# SM2000-A.net
KiCad netlist of a schematic drawn in EAGLE
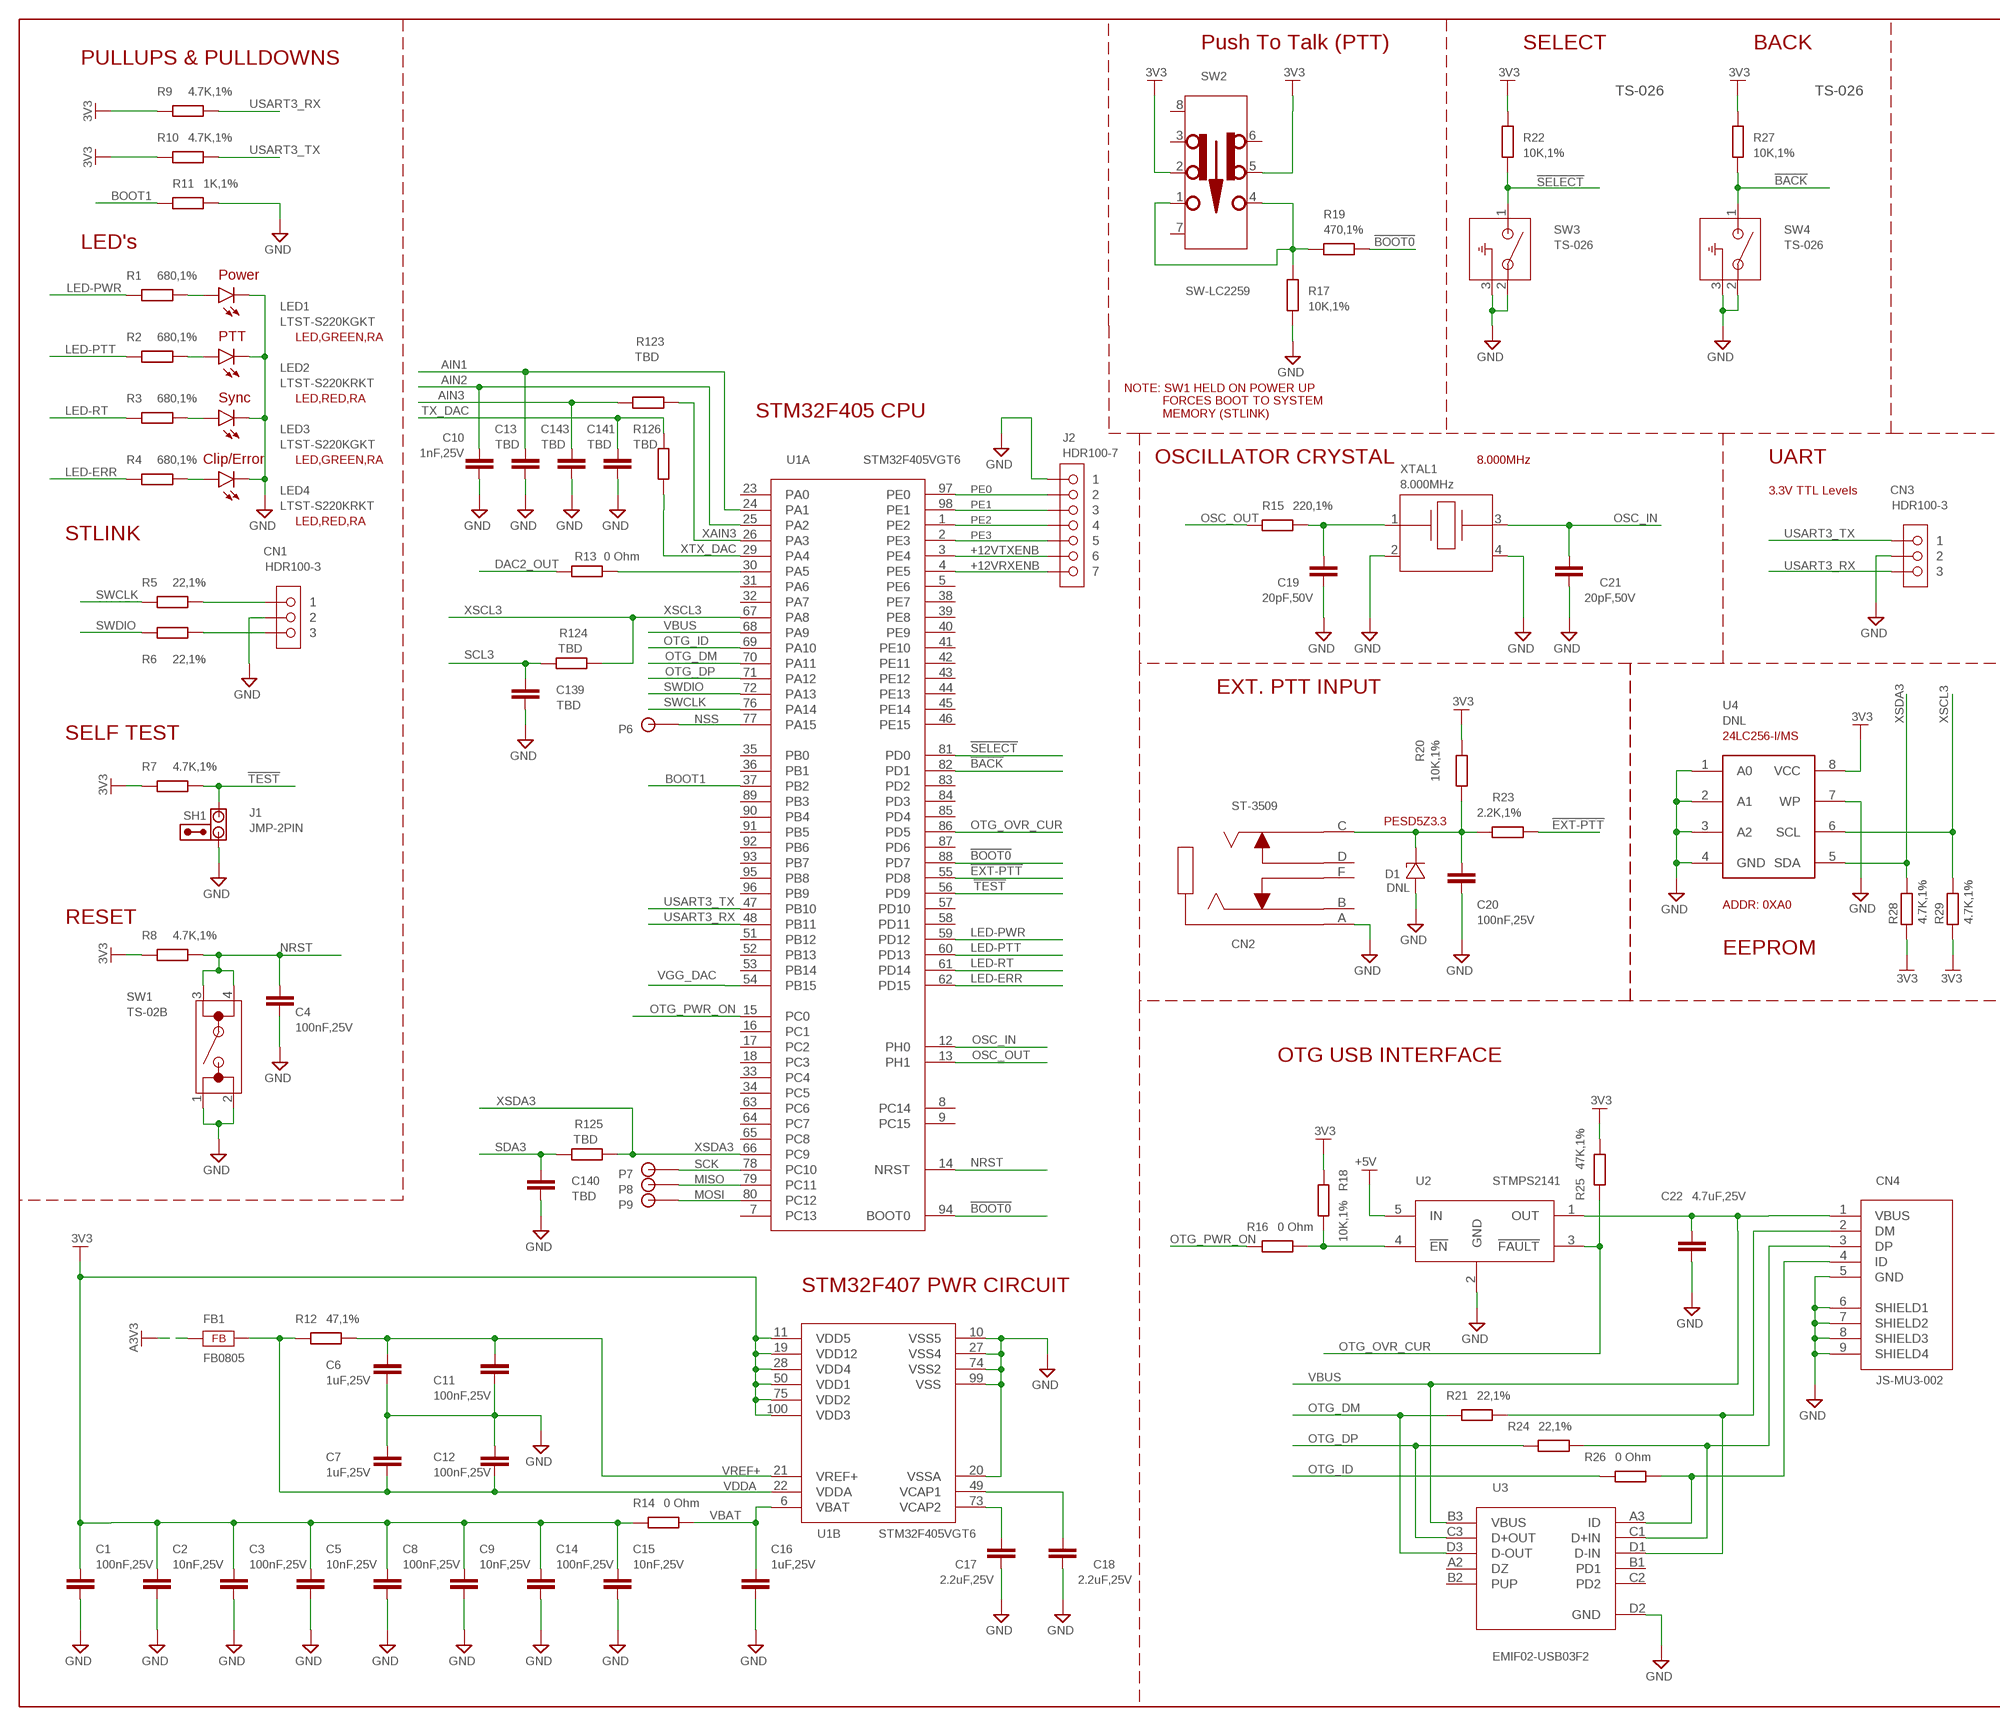
[diagram p0: schematic, sheet 1, part 1 of 2]
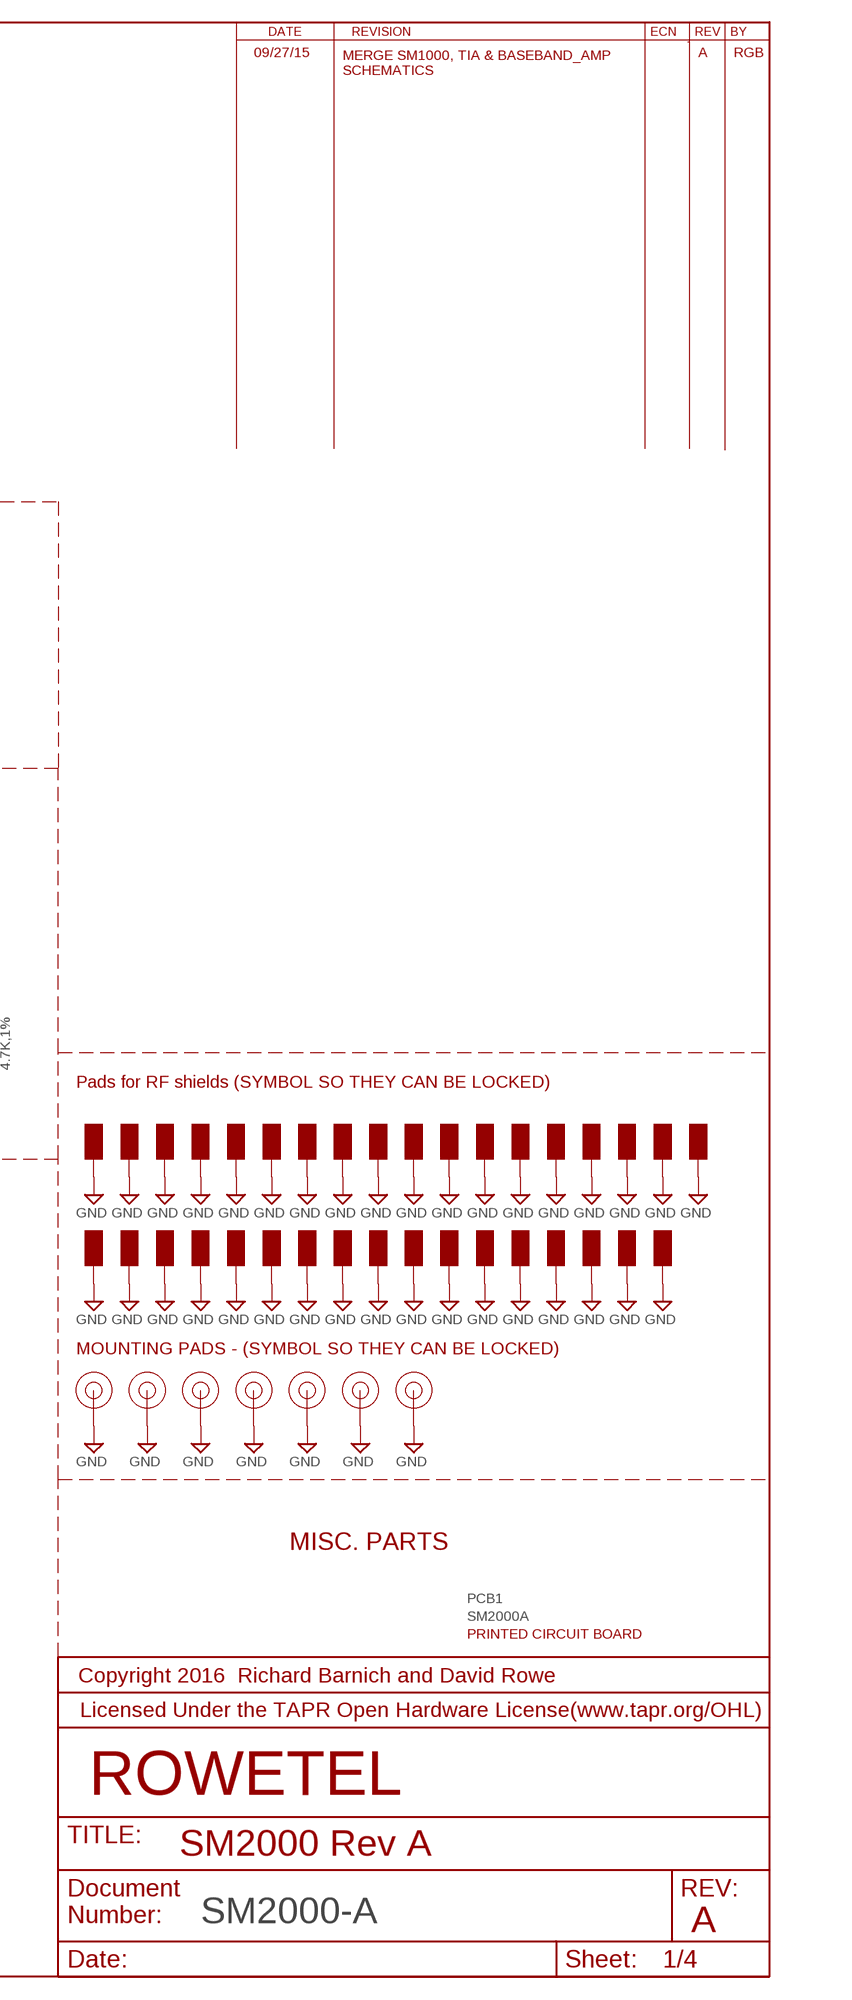
[diagram p1: schematic, sheet 1, part 2 of 2]
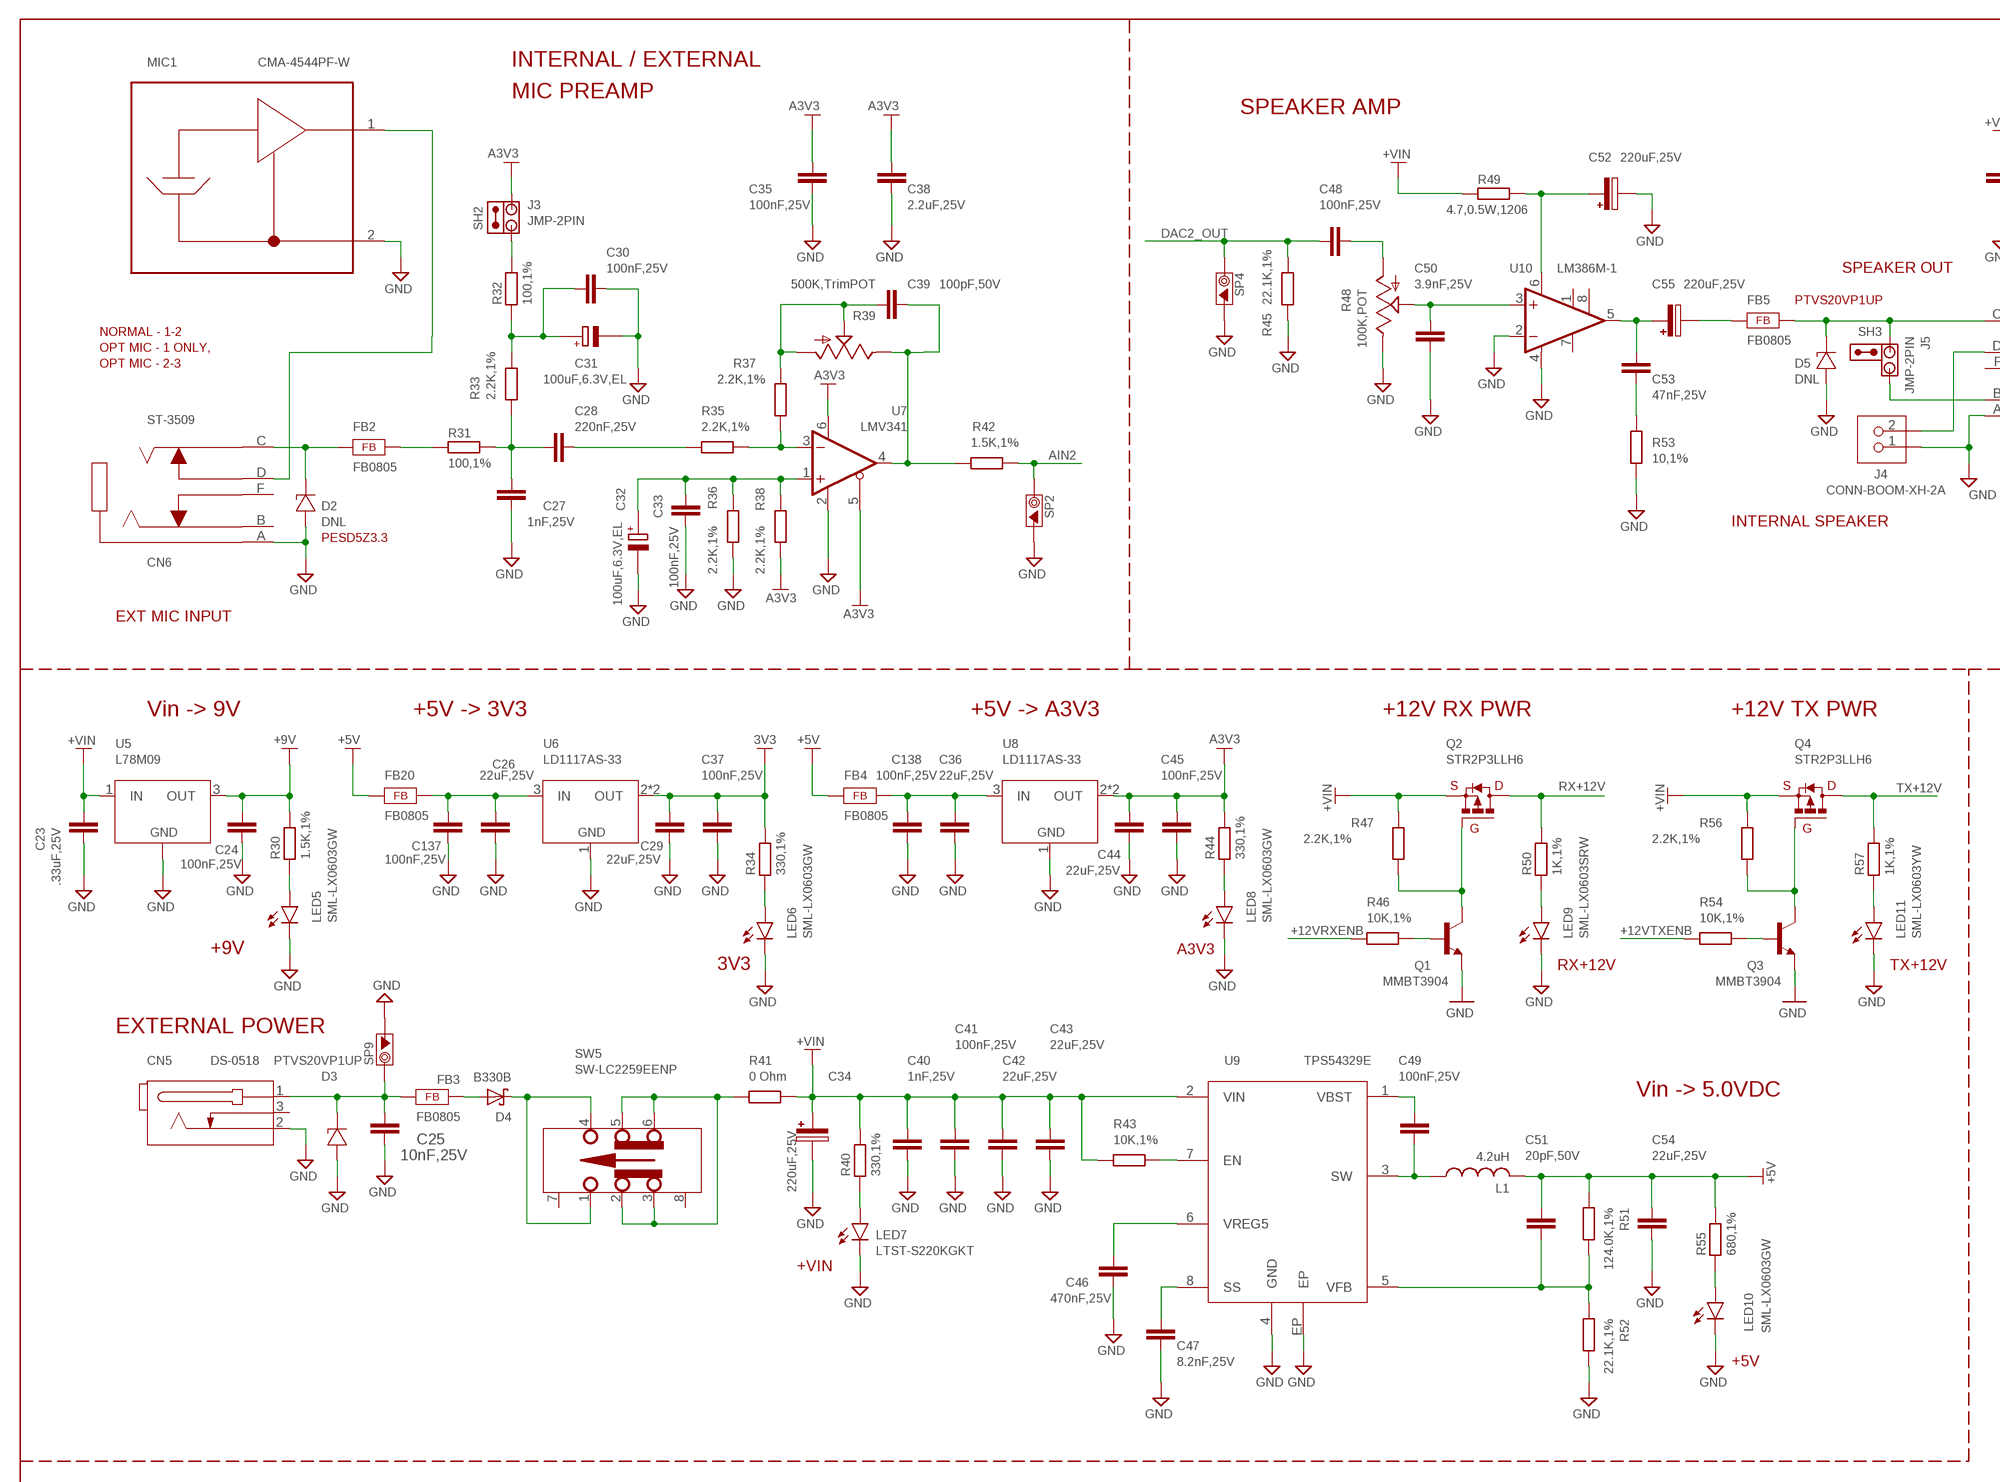
[diagram p2: schematic, sheet 2, part 1 of 2]
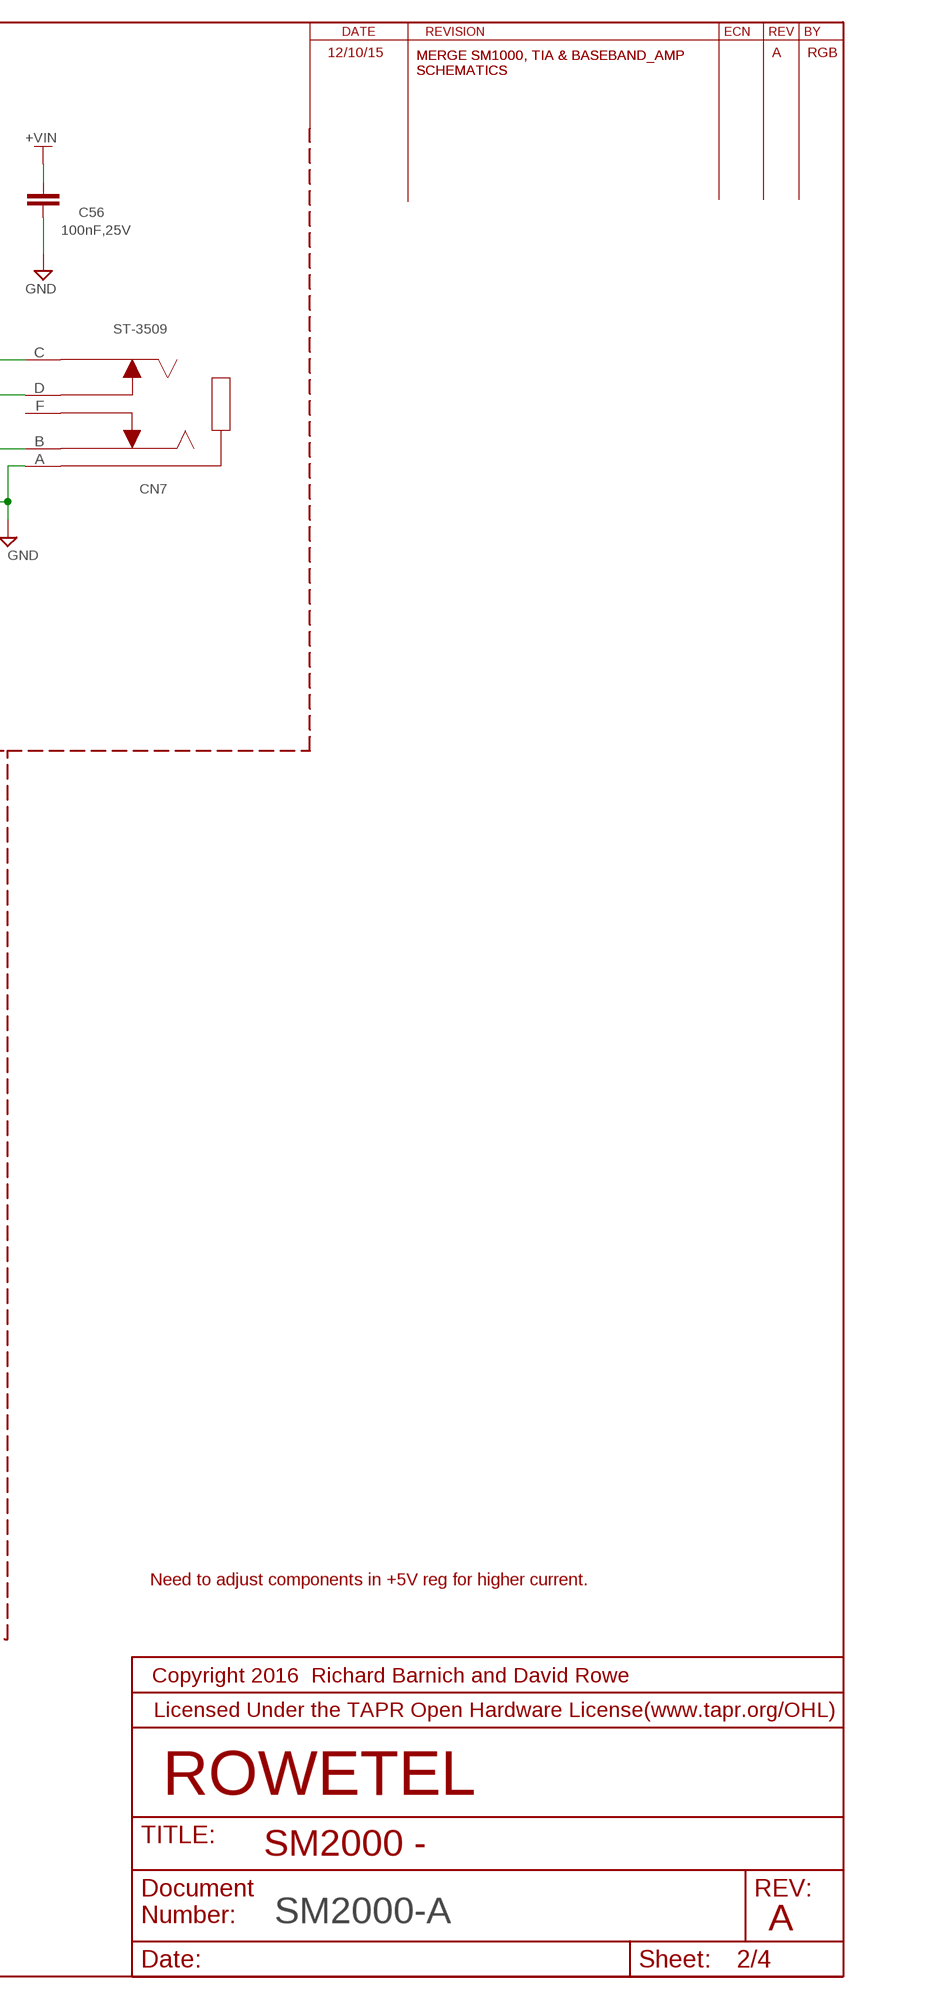
[diagram p3: schematic, sheet 2, part 2 of 2]
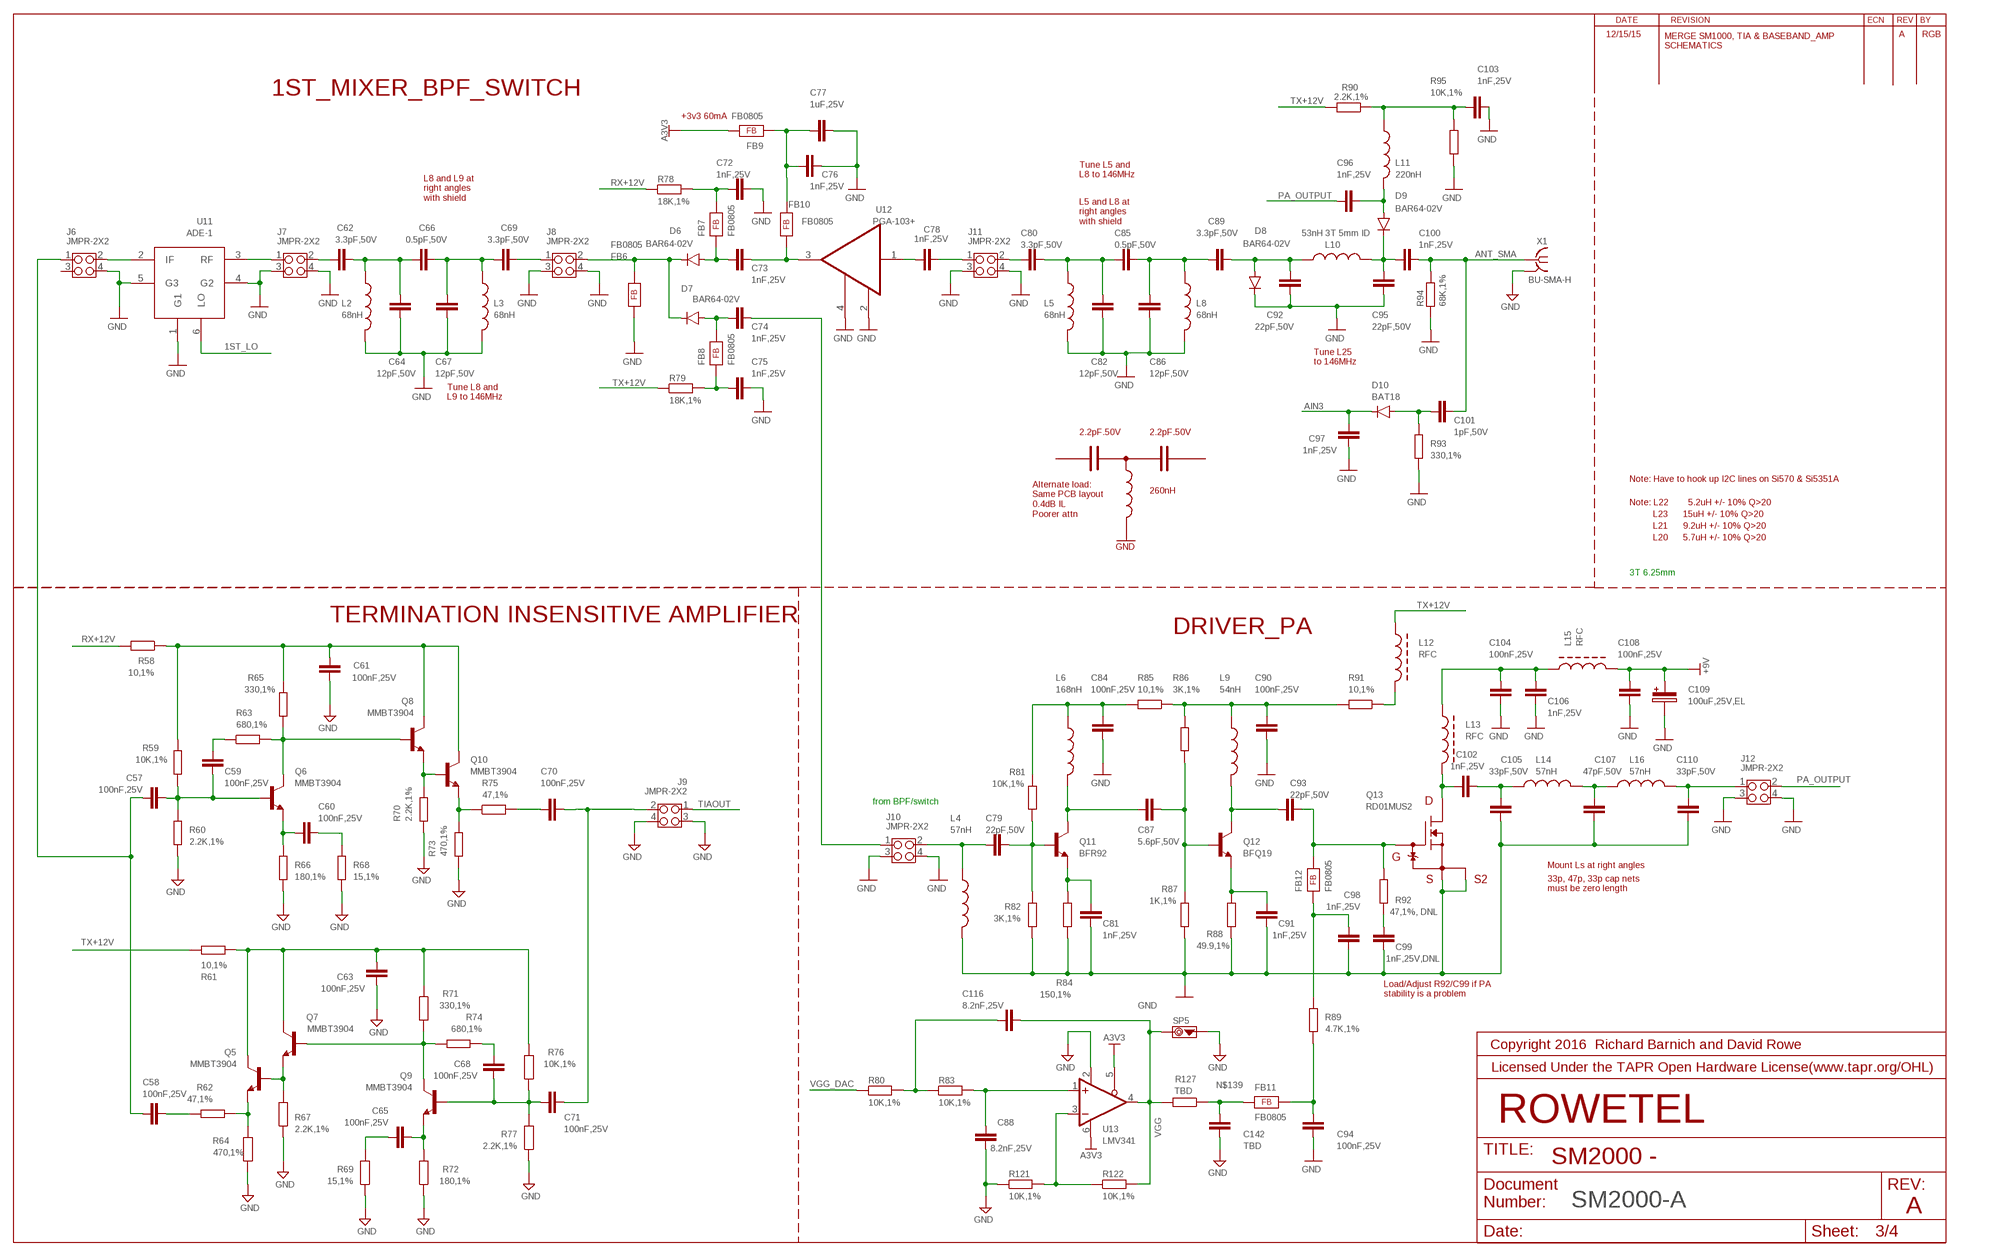
[diagram p4: schematic, sheet 3]
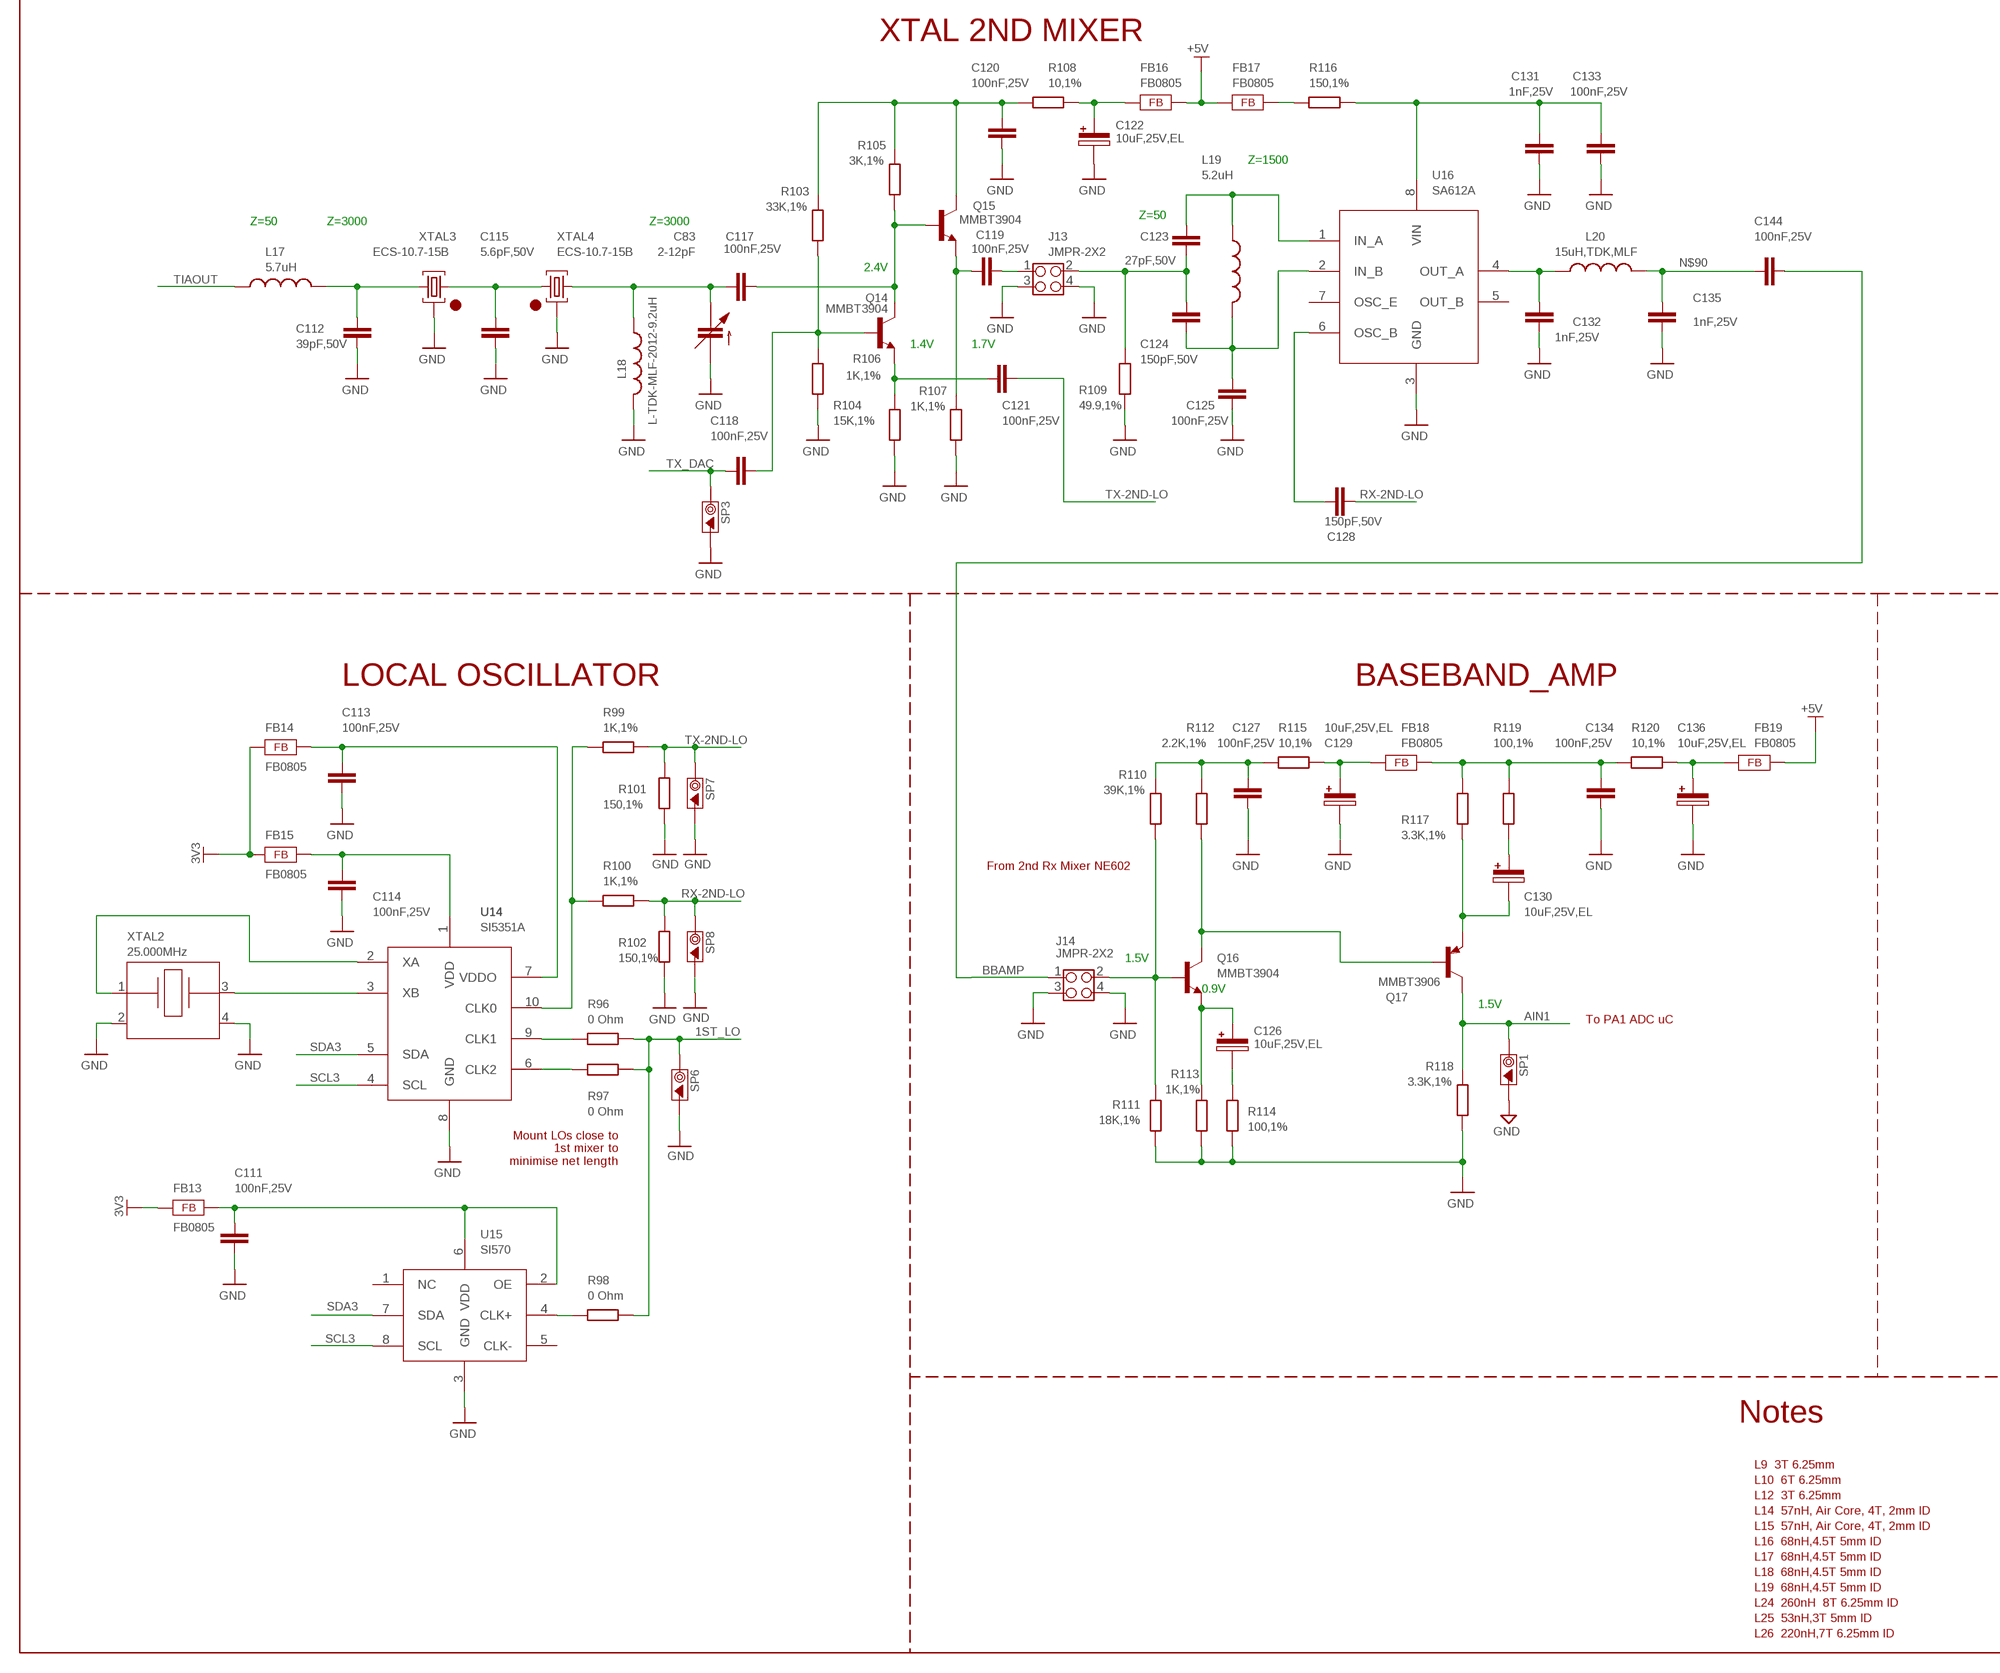
[diagram p5: schematic, sheet 4, part 1 of 2]
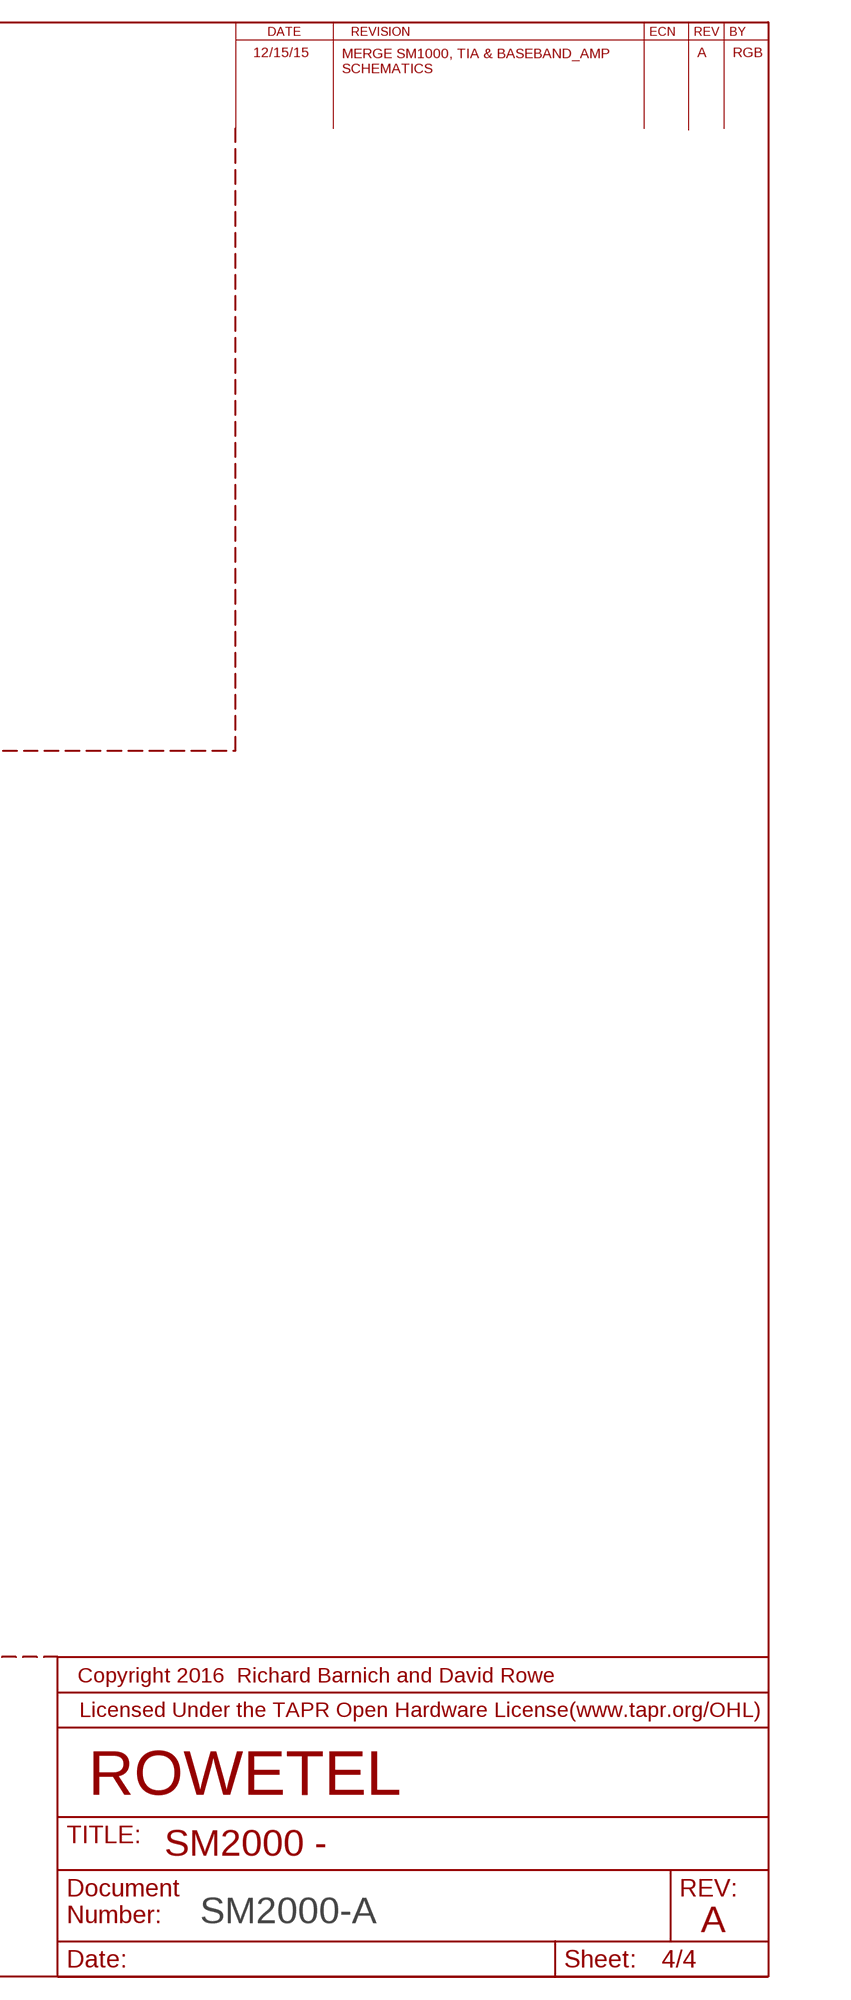
[diagram p6: schematic, sheet 4, part 2 of 2]

(export (version "E")
  (design (tool "Eeschema 10.0.6"))
  (components
    (comp (ref "C57")
      (value "100nF,25V")
      (footprint "eagle-import:C0805")
      (libsource (lib "eagle-import") (part "CAP-0805"))
    )
    (comp (ref "C58")
      (value "100nF,25V")
      (footprint "eagle-import:C0805")
      (libsource (lib "eagle-import") (part "CAP-0805"))
    )
    (comp (ref "C59")
      (value "100nF,25V")
      (footprint "eagle-import:C0805")
      (libsource (lib "eagle-import") (part "CAP-0805"))
    )
    (comp (ref "C60")
      (value "100nF,25V")
      (footprint "eagle-import:C0805")
      (libsource (lib "eagle-import") (part "CAP-0805"))
    )
    (comp (ref "C61")
      (value "100nF,25V")
      (footprint "eagle-import:C0805")
      (libsource (lib "eagle-import") (part "CAP-0805"))
    )
    (comp (ref "C62")
      (value "3.3pF,50V")
      (footprint "eagle-import:C0805")
      (libsource (lib "eagle-import") (part "CAP-0805"))
    )
    (comp (ref "C63")
      (value "100nF,25V")
      (footprint "eagle-import:C0805")
      (libsource (lib "eagle-import") (part "CAP-0805"))
    )
    (comp (ref "C64")
      (value "12pF,50V")
      (footprint "eagle-import:C0805")
      (libsource (lib "eagle-import") (part "CAP-0805"))
    )
    (comp (ref "C65")
      (value "100nF,25V")
      (footprint "eagle-import:C0805")
      (libsource (lib "eagle-import") (part "CAP-0805"))
    )
    (comp (ref "C66")
      (value "0.5pF,50V")
      (footprint "eagle-import:C0805")
      (libsource (lib "eagle-import") (part "CAP-0805"))
    )
    (comp (ref "C67")
      (value "12pF,50V")
      (footprint "eagle-import:C0805")
      (libsource (lib "eagle-import") (part "CAP-0805"))
    )
    (comp (ref "C68")
      (value "100nF,25V")
      (footprint "eagle-import:C0805")
      (libsource (lib "eagle-import") (part "CAP-0805"))
    )
    (comp (ref "C69")
      (value "3.3pF,50V")
      (footprint "eagle-import:C0805")
      (libsource (lib "eagle-import") (part "CAP-0805"))
    )
    (comp (ref "C70")
      (value "100nF,25V")
      (footprint "eagle-import:C0805")
      (libsource (lib "eagle-import") (part "CAP-0805"))
    )
    (comp (ref "C71")
      (value "100nF,25V")
      (footprint "eagle-import:C0805")
      (libsource (lib "eagle-import") (part "CAP-0805"))
    )
    (comp (ref "C72")
      (value "1nF,25V")
      (footprint "eagle-import:C0805")
      (libsource (lib "eagle-import") (part "CAP-0805"))
    )
    (comp (ref "C73")
      (value "1nF,25V")
      (footprint "eagle-import:C0805")
      (libsource (lib "eagle-import") (part "CAP-0805"))
    )
    (comp (ref "C74")
      (value "1nF,25V")
      (footprint "eagle-import:C0805")
      (libsource (lib "eagle-import") (part "CAP-0805"))
    )
    (comp (ref "C75")
      (value "1nF,25V")
      (footprint "eagle-import:C0805")
      (libsource (lib "eagle-import") (part "CAP-0805"))
    )
    (comp (ref "C76")
      (value "1nF,25V")
      (footprint "eagle-import:C0805")
      (libsource (lib "eagle-import") (part "CAP-0805"))
    )
    (comp (ref "C77")
      (value "1uF,25V")
      (footprint "eagle-import:C0805")
      (libsource (lib "eagle-import") (part "CAP-0805"))
    )
    (comp (ref "C78")
      (value "1nF,25V")
      (footprint "eagle-import:C0805")
      (libsource (lib "eagle-import") (part "CAP-0805"))
    )
    (comp (ref "C79")
      (value "22pF,50V")
      (footprint "eagle-import:C0805")
      (libsource (lib "eagle-import") (part "CAP-0805"))
    )
    (comp (ref "C80")
      (value "3.3pF,50V")
      (footprint "eagle-import:C0805")
      (libsource (lib "eagle-import") (part "CAP-0805"))
    )
    (comp (ref "C81")
      (value "1nF,25V")
      (footprint "eagle-import:C0805")
      (libsource (lib "eagle-import") (part "CAP-0805"))
    )
    (comp (ref "C82")
      (value "12pF,50V")
      (footprint "eagle-import:C0805")
      (libsource (lib "eagle-import") (part "CAP-0805"))
    )
    (comp (ref "C84")
      (value "100nF,25V")
      (footprint "eagle-import:C0805")
      (libsource (lib "eagle-import") (part "CAP-0805"))
    )
    (comp (ref "C85")
      (value "0.5pF,50V")
      (footprint "eagle-import:C0805")
      (libsource (lib "eagle-import") (part "CAP-0805"))
    )
    (comp (ref "C86")
      (value "12pF,50V")
      (footprint "eagle-import:C0805")
      (libsource (lib "eagle-import") (part "CAP-0805"))
    )
    (comp (ref "C87")
      (value "5.6pF,50V")
      (footprint "eagle-import:C0805")
      (libsource (lib "eagle-import") (part "CAP-0805"))
    )
    (comp (ref "C88")
      (value "8.2nF,25V")
      (footprint "eagle-import:C0805")
      (libsource (lib "eagle-import") (part "CAP-0805"))
    )
    (comp (ref "C89")
      (value "3.3pF,50V")
      (footprint "eagle-import:C0805")
      (libsource (lib "eagle-import") (part "CAP-0805"))
    )
    (comp (ref "C90")
      (value "100nF,25V")
      (footprint "eagle-import:C0805")
      (libsource (lib "eagle-import") (part "CAP-0805"))
    )
    (comp (ref "C91")
      (value "1nF,25V")
      (footprint "eagle-import:C0805")
      (libsource (lib "eagle-import") (part "CAP-0805"))
    )
    (comp (ref "C92")
      (value "22pF,50V")
      (footprint "eagle-import:C0805")
      (libsource (lib "eagle-import") (part "CAP-0805"))
    )
    (comp (ref "C93")
      (value "22pF,50V")
      (footprint "eagle-import:C0805")
      (libsource (lib "eagle-import") (part "CAP-0805"))
    )
    (comp (ref "C94")
      (value "100nF,25V")
      (footprint "eagle-import:C0805")
      (libsource (lib "eagle-import") (part "CAP-0805"))
    )
    (comp (ref "C95")
      (value "22pF,50V")
      (footprint "eagle-import:C0805")
      (libsource (lib "eagle-import") (part "CAP-0805"))
    )
    (comp (ref "C96")
      (value "1nF,25V")
      (footprint "eagle-import:C0805")
      (libsource (lib "eagle-import") (part "CAP-0805"))
    )
    (comp (ref "C97")
      (value "1nF,25V")
      (footprint "eagle-import:C0805")
      (libsource (lib "eagle-import") (part "CAP-0805"))
    )
    (comp (ref "C98")
      (value "1nF,25V")
      (footprint "eagle-import:C0805")
      (libsource (lib "eagle-import") (part "CAP-0805"))
    )
    (comp (ref "C99")
      (value "1nF,25V,DNL")
      (footprint "eagle-import:C0805")
      (libsource (lib "eagle-import") (part "CAP-0805"))
    )
    (comp (ref "C100")
      (value "1nF,25V")
      (footprint "eagle-import:C0805")
      (libsource (lib "eagle-import") (part "CAP-0805"))
    )
    (comp (ref "C101")
      (value "1pF,50V")
      (footprint "eagle-import:C0805")
      (libsource (lib "eagle-import") (part "CAP-0805"))
    )
    (comp (ref "C102")
      (value "1nF,25V")
      (footprint "eagle-import:C0805")
      (libsource (lib "eagle-import") (part "CAP-0805"))
    )
    (comp (ref "C103")
      (value "1nF,25V")
      (footprint "eagle-import:C0805")
      (libsource (lib "eagle-import") (part "CAP-0805"))
    )
    (comp (ref "C104")
      (value "100nF,25V")
      (footprint "eagle-import:C0805")
      (libsource (lib "eagle-import") (part "CAP-0805"))
    )
    (comp (ref "C105")
      (value "33pF,50V")
      (footprint "eagle-import:C0805")
      (libsource (lib "eagle-import") (part "CAP-0805"))
    )
    (comp (ref "C106")
      (value "1nF,25V")
      (footprint "eagle-import:C0805")
      (libsource (lib "eagle-import") (part "CAP-0805"))
    )
    (comp (ref "C107")
      (value "47pF,50V")
      (footprint "eagle-import:C0805")
      (libsource (lib "eagle-import") (part "CAP-0805"))
    )
    (comp (ref "C108")
      (value "100nF,25V")
      (footprint "eagle-import:C0805")
      (libsource (lib "eagle-import") (part "CAP-0805"))
    )
    (comp (ref "C109")
      (value "100uF,25V,EL")
      (footprint "eagle-import:CAP-CHEMI-F80")
      (libsource (lib "eagle-import") (part "CAP-CHEMI-F80"))
    )
    (comp (ref "C110")
      (value "33pF,50V")
      (footprint "eagle-import:C0805")
      (libsource (lib "eagle-import") (part "CAP-0805"))
    )
    (comp (ref "C116")
      (value "8.2nF,25V")
      (footprint "eagle-import:C0805")
      (libsource (lib "eagle-import") (part "CAP-0805"))
    )
    (comp (ref "C142")
      (value "TBD")
      (footprint "eagle-import:C0805")
      (libsource (lib "eagle-import") (part "CAP-0805"))
    )
    (comp (ref "D6")
      (value "BAR64-02V")
      (footprint "eagle-import:SC79_INFINEON")
      (libsource (lib "eagle-import") (part "BAR64-02V"))
    )
    (comp (ref "D7")
      (value "BAR64-02V")
      (footprint "eagle-import:SC79_INFINEON")
      (libsource (lib "eagle-import") (part "BAR64-02V"))
    )
    (comp (ref "D8")
      (value "BAR64-02V")
      (footprint "eagle-import:SC79_INFINEON")
      (libsource (lib "eagle-import") (part "BAR64-02V"))
    )
    (comp (ref "D9")
      (value "BAR64-02V")
      (footprint "eagle-import:SC79_INFINEON")
      (libsource (lib "eagle-import") (part "BAR64-02V"))
    )
    (comp (ref "D10")
      (value "BAT18")
      (footprint "eagle-import:SOT23")
      (libsource (lib "eagle-import") (part "BAT18"))
    )
    (comp (ref "FB6")
      (value "FB0805")
      (footprint "eagle-import:FE0805")
      (libsource (lib "eagle-import") (part "FB0805"))
    )
    (comp (ref "FB7")
      (value "FB0805")
      (footprint "eagle-import:FE0805")
      (libsource (lib "eagle-import") (part "FB0805"))
    )
    (comp (ref "FB8")
      (value "FB0805")
      (footprint "eagle-import:FE0805")
      (libsource (lib "eagle-import") (part "FB0805"))
    )
    (comp (ref "FB9")
      (value "FB0805")
      (footprint "eagle-import:FE0805")
      (libsource (lib "eagle-import") (part "FB0805"))
    )
    (comp (ref "FB10")
      (value "FB0805")
      (footprint "eagle-import:FE0805")
      (libsource (lib "eagle-import") (part "FB0805"))
    )
    (comp (ref "FB11")
      (value "FB0805")
      (footprint "eagle-import:FE0805")
      (libsource (lib "eagle-import") (part "FB0805"))
    )
    (comp (ref "FB12")
      (value "FB0805")
      (footprint "eagle-import:FE0805")
      (libsource (lib "eagle-import") (part "FB0805"))
    )
    (comp (ref "J6")
      (value "JMPR-2X2")
      (footprint "eagle-import:JMPR-2X2X.1")
      (libsource (lib "eagle-import") (part "JMPR-2X2"))
    )
    (comp (ref "J7")
      (value "JMPR-2X2")
      (footprint "eagle-import:JMPR-2X2X.1")
      (libsource (lib "eagle-import") (part "JMPR-2X2"))
    )
    (comp (ref "J8")
      (value "JMPR-2X2")
      (footprint "eagle-import:JMPR-2X2X.1")
      (libsource (lib "eagle-import") (part "JMPR-2X2"))
    )
    (comp (ref "J9")
      (value "JMPR-2X2")
      (footprint "eagle-import:JMPR-2X2X.1")
      (libsource (lib "eagle-import") (part "JMPR-2X2"))
    )
    (comp (ref "J10")
      (value "JMPR-2X2")
      (footprint "eagle-import:JMPR-2X2X.1")
      (libsource (lib "eagle-import") (part "JMPR-2X2"))
    )
    (comp (ref "J11")
      (value "JMPR-2X2")
      (footprint "eagle-import:JMPR-2X2X.1")
      (libsource (lib "eagle-import") (part "JMPR-2X2"))
    )
    (comp (ref "J12")
      (value "JMPR-2X2")
      (footprint "eagle-import:JMPR-2X2X.1")
      (libsource (lib "eagle-import") (part "JMPR-2X2"))
    )
    (comp (ref "L2")
      (value "68nH")
      (footprint "eagle-import:L10X15")
      (libsource (lib "eagle-import") (part "L-ROWE_15X10"))
    )
    (comp (ref "L3")
      (value "68nH")
      (footprint "eagle-import:L10X15")
      (libsource (lib "eagle-import") (part "L-ROWE_15X10"))
    )
    (comp (ref "L4")
      (value "57nH")
      (footprint "eagle-import:L10X15")
      (libsource (lib "eagle-import") (part "L-ROWE_15X10"))
    )
    (comp (ref "L5")
      (value "68nH")
      (footprint "eagle-import:L10X15")
      (libsource (lib "eagle-import") (part "L-ROWE_15X10"))
    )
    (comp (ref "L6")
      (value "168nH")
      (footprint "eagle-import:L10X15")
      (libsource (lib "eagle-import") (part "L-ROWE_15X10"))
    )
    (comp (ref "L8")
      (value "68nH")
      (footprint "eagle-import:L10X15")
      (libsource (lib "eagle-import") (part "L-ROWE_15X10"))
    )
    (comp (ref "L9")
      (value "54nH")
      (footprint "eagle-import:L10X15")
      (libsource (lib "eagle-import") (part "L-ROWE_15X10"))
    )
    (comp (ref "L10")
      (value "53nH 3T 5mm ID")
      (footprint "eagle-import:L10X15")
      (libsource (lib "eagle-import") (part "L-ROWE_15X10"))
    )
    (comp (ref "L11")
      (value "220nH")
      (footprint "eagle-import:L10X15")
      (libsource (lib "eagle-import") (part "L-ROWE_15X10"))
    )
    (comp (ref "L12")
      (value "RFC")
      (footprint "eagle-import:Z15_4")
      (libsource (lib "eagle-import") (part "RFC"))
    )
    (comp (ref "L13")
      (value "RFC")
      (footprint "eagle-import:Z15_4")
      (libsource (lib "eagle-import") (part "RFC"))
    )
    (comp (ref "L14")
      (value "57nH")
      (footprint "eagle-import:L10X15")
      (libsource (lib "eagle-import") (part "L-ROWE_15X10"))
    )
    (comp (ref "L15")
      (value "RFC")
      (footprint "eagle-import:Z15_4")
      (libsource (lib "eagle-import") (part "RFC"))
    )
    (comp (ref "L16")
      (value "57nH")
      (footprint "eagle-import:L10X15")
      (libsource (lib "eagle-import") (part "L-ROWE_15X10"))
    )
    (comp (ref "Q5")
      (value "MMBT3904")
      (footprint "eagle-import:SOT23")
      (libsource (lib "eagle-import") (part "MMBT3904"))
    )
    (comp (ref "Q6")
      (value "MMBT3904")
      (footprint "eagle-import:SOT23")
      (libsource (lib "eagle-import") (part "MMBT3904"))
    )
    (comp (ref "Q7")
      (value "MMBT3904")
      (footprint "eagle-import:SOT23")
      (libsource (lib "eagle-import") (part "MMBT3904"))
    )
    (comp (ref "Q8")
      (value "MMBT3904")
      (footprint "eagle-import:SOT23")
      (libsource (lib "eagle-import") (part "MMBT3904"))
    )
    (comp (ref "Q9")
      (value "MMBT3904")
      (footprint "eagle-import:SOT23")
      (libsource (lib "eagle-import") (part "MMBT3904"))
    )
    (comp (ref "Q10")
      (value "MMBT3904")
      (footprint "eagle-import:SOT23")
      (libsource (lib "eagle-import") (part "MMBT3904"))
    )
    (comp (ref "Q11")
      (value "BFR92")
      (footprint "eagle-import:SOT23")
      (libsource (lib "eagle-import") (part "BFR92"))
    )
    (comp (ref "Q12")
      (value "BFQ19")
      (footprint "eagle-import:SOT89")
      (libsource (lib "eagle-import") (part "BFQ19"))
    )
    (comp (ref "Q13")
      (value "RD01MUS2")
      (footprint "eagle-import:SOT89")
      (libsource (lib "eagle-import") (part "RD01MUS2"))
    )
    (comp (ref "R58")
      (value "10,1%")
      (footprint "eagle-import:R0805")
      (libsource (lib "eagle-import") (part "RES-0805"))
    )
    (comp (ref "R59")
      (value "10K,1%")
      (footprint "eagle-import:R0805")
      (libsource (lib "eagle-import") (part "RES-0805"))
    )
    (comp (ref "R60")
      (value "2.2K,1%")
      (footprint "eagle-import:R0805")
      (libsource (lib "eagle-import") (part "RES-0805"))
    )
    (comp (ref "R61")
      (value "10,1%")
      (footprint "eagle-import:R0805")
      (libsource (lib "eagle-import") (part "RES-0805"))
    )
    (comp (ref "R62")
      (value "47,1%")
      (footprint "eagle-import:R0805")
      (libsource (lib "eagle-import") (part "RES-0805"))
    )
    (comp (ref "R63")
      (value "680,1%")
      (footprint "eagle-import:R0805")
      (libsource (lib "eagle-import") (part "RES-0805"))
    )
    (comp (ref "R64")
      (value "470,1%")
      (footprint "eagle-import:R0805")
      (libsource (lib "eagle-import") (part "RES-0805"))
    )
    (comp (ref "R65")
      (value "330,1%")
      (footprint "eagle-import:R0805")
      (libsource (lib "eagle-import") (part "RES-0805"))
    )
    (comp (ref "R66")
      (value "180,1%")
      (footprint "eagle-import:R0805")
      (libsource (lib "eagle-import") (part "RES-0805"))
    )
    (comp (ref "R67")
      (value "2.2K,1%")
      (footprint "eagle-import:R0805")
      (libsource (lib "eagle-import") (part "RES-0805"))
    )
    (comp (ref "R68")
      (value "15,1%")
      (footprint "eagle-import:R0805")
      (libsource (lib "eagle-import") (part "RES-0805"))
    )
    (comp (ref "R69")
      (value "15,1%")
      (footprint "eagle-import:R0805")
      (libsource (lib "eagle-import") (part "RES-0805"))
    )
    (comp (ref "R70")
      (value "2.2K,1%")
      (footprint "eagle-import:R0805")
      (libsource (lib "eagle-import") (part "RES-0805"))
    )
    (comp (ref "R71")
      (value "330,1%")
      (footprint "eagle-import:R0805")
      (libsource (lib "eagle-import") (part "RES-0805"))
    )
    (comp (ref "R72")
      (value "180,1%")
      (footprint "eagle-import:R0805")
      (libsource (lib "eagle-import") (part "RES-0805"))
    )
    (comp (ref "R73")
      (value "470,1%")
      (footprint "eagle-import:R0805")
      (libsource (lib "eagle-import") (part "RES-0805"))
    )
    (comp (ref "R74")
      (value "680,1%")
      (footprint "eagle-import:R0805")
      (libsource (lib "eagle-import") (part "RES-0805"))
    )
    (comp (ref "R75")
      (value "47,1%")
      (footprint "eagle-import:R0805")
      (libsource (lib "eagle-import") (part "RES-0805"))
    )
    (comp (ref "R76")
      (value "10K,1%")
      (footprint "eagle-import:R0805")
      (libsource (lib "eagle-import") (part "RES-0805"))
    )
    (comp (ref "R77")
      (value "2.2K,1%")
      (footprint "eagle-import:R0805")
      (libsource (lib "eagle-import") (part "RES-0805"))
    )
    (comp (ref "R78")
      (value "18K,1%")
      (footprint "eagle-import:R0805")
      (libsource (lib "eagle-import") (part "RES-0805"))
    )
    (comp (ref "R79")
      (value "18K,1%")
      (footprint "eagle-import:R0805")
      (libsource (lib "eagle-import") (part "RES-0805"))
    )
    (comp (ref "R80")
      (value "10K,1%")
      (footprint "eagle-import:R0805")
      (libsource (lib "eagle-import") (part "RES-0805"))
    )
    (comp (ref "R81")
      (value "10K,1%")
      (footprint "eagle-import:R0805")
      (libsource (lib "eagle-import") (part "RES-0805"))
    )
    (comp (ref "R82")
      (value "3K,1%")
      (footprint "eagle-import:R0805")
      (libsource (lib "eagle-import") (part "RES-0805"))
    )
    (comp (ref "R83")
      (value "10K,1%")
      (footprint "eagle-import:R0805")
      (libsource (lib "eagle-import") (part "RES-0805"))
    )
    (comp (ref "R84")
      (value "150,1%")
      (footprint "eagle-import:R0805")
      (libsource (lib "eagle-import") (part "RES-0805"))
    )
    (comp (ref "R85")
      (value "10,1%")
      (footprint "eagle-import:R0805")
      (libsource (lib "eagle-import") (part "RES-0805"))
    )
    (comp (ref "R86")
      (value "3K,1%")
      (footprint "eagle-import:R0805")
      (libsource (lib "eagle-import") (part "RES-0805"))
    )
    (comp (ref "R87")
      (value "1K,1%")
      (footprint "eagle-import:R0805")
      (libsource (lib "eagle-import") (part "RES-0805"))
    )
    (comp (ref "R88")
      (value "49.9,1%")
      (footprint "eagle-import:R0805")
      (libsource (lib "eagle-import") (part "RES-0805"))
    )
    (comp (ref "R89")
      (value "4.7K,1%")
      (footprint "eagle-import:R0805")
      (libsource (lib "eagle-import") (part "RES-0805"))
    )
    (comp (ref "R90")
      (value "2.2K,1%")
      (footprint "eagle-import:R0805")
      (libsource (lib "eagle-import") (part "RES-0805"))
    )
    (comp (ref "R91")
      (value "10,1%")
      (footprint "eagle-import:R0805")
      (libsource (lib "eagle-import") (part "RES-0805"))
    )
    (comp (ref "R92")
      (value "47,1%, DNL")
      (footprint "eagle-import:R0805")
      (libsource (lib "eagle-import") (part "RES-0805"))
    )
    (comp (ref "R93")
      (value "330,1%")
      (footprint "eagle-import:R0805")
      (libsource (lib "eagle-import") (part "RES-0805"))
    )
    (comp (ref "R94")
      (value "68K,1%")
      (footprint "eagle-import:R0805")
      (libsource (lib "eagle-import") (part "RES-0805"))
    )
    (comp (ref "R95")
      (value "10K,1%")
      (footprint "eagle-import:R0805")
      (libsource (lib "eagle-import") (part "RES-0805"))
    )
    (comp (ref "R121")
      (value "10K,1%")
      (footprint "eagle-import:R0805")
      (libsource (lib "eagle-import") (part "RES-0805"))
    )
    (comp (ref "R122")
      (value "10K,1%")
      (footprint "eagle-import:R0805")
      (libsource (lib "eagle-import") (part "RES-0805"))
    )
    (comp (ref "R127")
      (value "TBD")
      (footprint "eagle-import:R0805")
      (libsource (lib "eagle-import") (part "RES-0805"))
    )
    (comp (ref "SP5")
      (value "SCOPE_PAD")
      (footprint "eagle-import:SCOPE_PAD")
      (libsource (lib "eagle-import") (part "SCOPE_PAD"))
    )
    (comp (ref "U11")
      (value "ADE-1")
      (footprint "eagle-import:ADE-1")
      (libsource (lib "eagle-import") (part "ADE-1"))
    )
    (comp (ref "U12")
      (value "PGA-103+")
      (footprint "eagle-import:DF782")
      (libsource (lib "eagle-import") (part "PGA-103+"))
    )
    (comp (ref "U13")
      (value "LMV341")
      (footprint "eagle-import:SOT23-6")
      (libsource (lib "eagle-import") (part "LMV341"))
    )
    (comp (ref "X1")
      (value "BU-SMA-H")
      (footprint "eagle-import:BU-SMA-H")
      (libsource (lib "eagle-import") (part "BU-SMA-H"))
    )
    (comp (ref "C1")
      (value "100nF,25V")
      (footprint "eagle-import:C0805")
      (libsource (lib "eagle-import") (part "CAP-0805"))
    )
    (comp (ref "C2")
      (value "10nF,25V")
      (footprint "eagle-import:C0805")
      (libsource (lib "eagle-import") (part "CAP-0805"))
    )
    (comp (ref "C3")
      (value "100nF,25V")
      (footprint "eagle-import:C0805")
      (libsource (lib "eagle-import") (part "CAP-0805"))
    )
    (comp (ref "C4")
      (value "100nF,25V")
      (footprint "eagle-import:C0805")
      (libsource (lib "eagle-import") (part "CAP-0805"))
    )
    (comp (ref "C5")
      (value "10nF,25V")
      (footprint "eagle-import:C0805")
      (libsource (lib "eagle-import") (part "CAP-0805"))
    )
    (comp (ref "C6")
      (value "1uF,25V")
      (footprint "eagle-import:C0805")
      (libsource (lib "eagle-import") (part "CAP-0805"))
    )
    (comp (ref "C7")
      (value "1uF,25V")
      (footprint "eagle-import:C0805")
      (libsource (lib "eagle-import") (part "CAP-0805"))
    )
    (comp (ref "C8")
      (value "100nF,25V")
      (footprint "eagle-import:C0805")
      (libsource (lib "eagle-import") (part "CAP-0805"))
    )
    (comp (ref "C9")
      (value "10nF,25V")
      (footprint "eagle-import:C0805")
      (libsource (lib "eagle-import") (part "CAP-0805"))
    )
    (comp (ref "C10")
      (value "1nF,25V")
      (footprint "eagle-import:C0805")
      (libsource (lib "eagle-import") (part "CAP-0805"))
    )
    (comp (ref "C11")
      (value "100nF,25V")
      (footprint "eagle-import:C0805")
      (libsource (lib "eagle-import") (part "CAP-0805"))
    )
    (comp (ref "C12")
      (value "100nF,25V")
      (footprint "eagle-import:C0805")
      (libsource (lib "eagle-import") (part "CAP-0805"))
    )
    (comp (ref "C13")
      (value "TBD")
      (footprint "eagle-import:C0805")
      (libsource (lib "eagle-import") (part "CAP-0805"))
    )
    (comp (ref "C14")
      (value "100nF,25V")
      (footprint "eagle-import:C0805")
      (libsource (lib "eagle-import") (part "CAP-0805"))
    )
    (comp (ref "C15")
      (value "10nF,25V")
      (footprint "eagle-import:C0805")
      (libsource (lib "eagle-import") (part "CAP-0805"))
    )
    (comp (ref "C16")
      (value "1uF,25V")
      (footprint "eagle-import:C0805")
      (libsource (lib "eagle-import") (part "CAP-0805"))
    )
    (comp (ref "C17")
      (value "2.2uF,25V")
      (footprint "eagle-import:C0805")
      (libsource (lib "eagle-import") (part "CAP-0805"))
    )
    (comp (ref "C18")
      (value "2.2uF,25V")
      (footprint "eagle-import:C0805")
      (libsource (lib "eagle-import") (part "CAP-0805"))
    )
    (comp (ref "C19")
      (value "20pF,50V")
      (footprint "eagle-import:C0805")
      (libsource (lib "eagle-import") (part "CAP-0805"))
    )
    (comp (ref "C20")
      (value "100nF,25V")
      (footprint "eagle-import:C0805")
      (libsource (lib "eagle-import") (part "CAP-0805"))
    )
    (comp (ref "C21")
      (value "20pF,50V")
      (footprint "eagle-import:C0805")
      (libsource (lib "eagle-import") (part "CAP-0805"))
    )
    (comp (ref "C22")
      (value "4.7uF,25V")
      (footprint "eagle-import:C0805")
      (libsource (lib "eagle-import") (part "CAP-0805"))
    )
    (comp (ref "C139")
      (value "TBD")
      (footprint "eagle-import:C0805")
      (libsource (lib "eagle-import") (part "CAP-0805"))
    )
    (comp (ref "C140")
      (value "TBD")
      (footprint "eagle-import:C0805")
      (libsource (lib "eagle-import") (part "CAP-0805"))
    )
    (comp (ref "C141")
      (value "TBD")
      (footprint "eagle-import:C0805")
      (libsource (lib "eagle-import") (part "CAP-0805"))
    )
    (comp (ref "C143")
      (value "TBD")
      (footprint "eagle-import:C0805")
      (libsource (lib "eagle-import") (part "CAP-0805"))
    )
    (comp (ref "CN1")
      (value "HDR100-3")
      (footprint "eagle-import:HDR100-3")
      (libsource (lib "eagle-import") (part "HDR100-3"))
    )
    (comp (ref "CN2")
      (value "ST-3509")
      (footprint "eagle-import:ST-3509")
      (libsource (lib "eagle-import") (part "ST-3509"))
    )
    (comp (ref "CN3")
      (value "HDR100-3")
      (footprint "eagle-import:HDR100-3")
      (libsource (lib "eagle-import") (part "HDR100-3"))
    )
    (comp (ref "CN4")
      (value "JS-MU3-002")
      (footprint "eagle-import:JI-MU3-002")
      (libsource (lib "eagle-import") (part "JS-MU3-002"))
    )
    (comp (ref "D1")
      (value "DNL")
      (footprint "eagle-import:SOD523")
      (libsource (lib "eagle-import") (part "PESD5ZX"))
    )
    (comp (ref "FB1")
      (value "FB0805")
      (footprint "eagle-import:FE0805")
      (libsource (lib "eagle-import") (part "FB0805"))
    )
    (comp (ref "J1")
      (value "JMP-2PIN")
      (footprint "eagle-import:JMPR-2PIN")
      (libsource (lib "eagle-import") (part "JMP-2PIN"))
    )
    (comp (ref "J2")
      (value "HDR100-7")
      (footprint "eagle-import:HDR100-7")
      (libsource (lib "eagle-import") (part "HDR100-7"))
    )
    (comp (ref "LED1")
      (value "LTST-S220KGKT")
      (footprint "eagle-import:LTST-S2200K")
      (libsource (lib "eagle-import") (part "LTST-S220K"))
    )
    (comp (ref "LED2")
      (value "LTST-S220KRKT")
      (footprint "eagle-import:LTST-S2200K")
      (libsource (lib "eagle-import") (part "LTST-S220K"))
    )
    (comp (ref "LED3")
      (value "LTST-S220KGKT")
      (footprint "eagle-import:LTST-S2200K")
      (libsource (lib "eagle-import") (part "LTST-S220K"))
    )
    (comp (ref "LED4")
      (value "LTST-S220KRKT")
      (footprint "eagle-import:LTST-S2200K")
      (libsource (lib "eagle-import") (part "LTST-S220K"))
    )
    (comp (ref "P6")
      (value "TPAD50")
      (footprint "eagle-import:TPAD50")
      (libsource (lib "eagle-import") (part "TPAD50"))
    )
    (comp (ref "P7")
      (value "TPAD50")
      (footprint "eagle-import:TPAD50")
      (libsource (lib "eagle-import") (part "TPAD50"))
    )
    (comp (ref "P8")
      (value "TPAD50")
      (footprint "eagle-import:TPAD50")
      (libsource (lib "eagle-import") (part "TPAD50"))
    )
    (comp (ref "P9")
      (value "TPAD50")
      (footprint "eagle-import:TPAD50")
      (libsource (lib "eagle-import") (part "TPAD50"))
    )
    (comp (ref "PAD1")
      (value "MTG-PAD-3.2")
      (footprint "eagle-import:MTG-PAD-3.2")
      (libsource (lib "eagle-import") (part "MTG-PAD-3.2"))
    )
    (comp (ref "PAD2")
      (value "MTG-PAD-3.2")
      (footprint "eagle-import:MTG-PAD-3.2")
      (libsource (lib "eagle-import") (part "MTG-PAD-3.2"))
    )
    (comp (ref "PAD3")
      (value "MTG-PAD-3.2")
      (footprint "eagle-import:MTG-PAD-3.2")
      (libsource (lib "eagle-import") (part "MTG-PAD-3.2"))
    )
    (comp (ref "PAD4")
      (value "MTG-PAD-3.2")
      (footprint "eagle-import:MTG-PAD-3.2")
      (libsource (lib "eagle-import") (part "MTG-PAD-3.2"))
    )
    (comp (ref "PAD5")
      (value "MTG-PAD-3.2")
      (footprint "eagle-import:MTG-PAD-3.2")
      (libsource (lib "eagle-import") (part "MTG-PAD-3.2"))
    )
    (comp (ref "PAD6")
      (value "MTG-PAD-3.2")
      (footprint "eagle-import:MTG-PAD-3.2")
      (libsource (lib "eagle-import") (part "MTG-PAD-3.2"))
    )
    (comp (ref "PAD7")
      (value "MTG-PAD-3.2")
      (footprint "eagle-import:MTG-PAD-3.2")
      (libsource (lib "eagle-import") (part "MTG-PAD-3.2"))
    )
    (comp (ref "PCB1")
      (value "SM2000A")
      (footprint "eagle-import:NOPACKAGE")
      (libsource (lib "eagle-import") (part "PCB"))
    )
    (comp (ref "R1")
      (value "680,1%")
      (footprint "eagle-import:R0805")
      (libsource (lib "eagle-import") (part "RES-0805"))
    )
    (comp (ref "R2")
      (value "680,1%")
      (footprint "eagle-import:R0805")
      (libsource (lib "eagle-import") (part "RES-0805"))
    )
    (comp (ref "R3")
      (value "680,1%")
      (footprint "eagle-import:R0805")
      (libsource (lib "eagle-import") (part "RES-0805"))
    )
    (comp (ref "R4")
      (value "680,1%")
      (footprint "eagle-import:R0805")
      (libsource (lib "eagle-import") (part "RES-0805"))
    )
    (comp (ref "R5")
      (value "22,1%")
      (footprint "eagle-import:R0805")
      (libsource (lib "eagle-import") (part "RES-0805"))
    )
    (comp (ref "R6")
      (value "22,1%")
      (footprint "eagle-import:R0805")
      (libsource (lib "eagle-import") (part "RES-0805"))
    )
    (comp (ref "R7")
      (value "4.7K,1%")
      (footprint "eagle-import:R0805")
      (libsource (lib "eagle-import") (part "RES-0805"))
    )
    (comp (ref "R8")
      (value "4.7K,1%")
      (footprint "eagle-import:R0805")
      (libsource (lib "eagle-import") (part "RES-0805"))
    )
    (comp (ref "R9")
      (value "4.7K,1%")
      (footprint "eagle-import:R0805")
      (libsource (lib "eagle-import") (part "RES-0805"))
    )
    (comp (ref "R10")
      (value "4.7K,1%")
      (footprint "eagle-import:R0805")
      (libsource (lib "eagle-import") (part "RES-0805"))
    )
    (comp (ref "R11")
      (value "1K,1%")
      (footprint "eagle-import:R0805")
      (libsource (lib "eagle-import") (part "RES-0805"))
    )
    (comp (ref "R12")
      (value "47,1%")
      (footprint "eagle-import:R0805")
      (libsource (lib "eagle-import") (part "RES-0805"))
    )
    (comp (ref "R13")
      (value "0 Ohm")
      (footprint "eagle-import:R0805")
      (libsource (lib "eagle-import") (part "RES-0805"))
    )
    (comp (ref "R14")
      (value "0 Ohm")
      (footprint "eagle-import:R0805")
      (libsource (lib "eagle-import") (part "RES-0805"))
    )
    (comp (ref "R15")
      (value "220,1%")
      (footprint "eagle-import:R0805")
      (libsource (lib "eagle-import") (part "RES-0805"))
    )
    (comp (ref "R16")
      (value "0 Ohm")
      (footprint "eagle-import:R0805")
      (libsource (lib "eagle-import") (part "RES-0805"))
    )
    (comp (ref "R17")
      (value "10K,1%")
      (footprint "eagle-import:R0805")
      (libsource (lib "eagle-import") (part "RES-0805"))
    )
    (comp (ref "R18")
      (value "10K,1%")
      (footprint "eagle-import:R0805")
      (libsource (lib "eagle-import") (part "RES-0805"))
    )
    (comp (ref "R19")
      (value "470,1%")
      (footprint "eagle-import:R0805")
      (libsource (lib "eagle-import") (part "RES-0805"))
    )
    (comp (ref "R20")
      (value "10K,1%")
      (footprint "eagle-import:R0805")
      (libsource (lib "eagle-import") (part "RES-0805"))
    )
    (comp (ref "R21")
      (value "22,1%")
      (footprint "eagle-import:R0805")
      (libsource (lib "eagle-import") (part "RES-0805"))
    )
    (comp (ref "R22")
      (value "10K,1%")
      (footprint "eagle-import:R0805")
      (libsource (lib "eagle-import") (part "RES-0805"))
    )
    (comp (ref "R23")
      (value "2.2K,1%")
      (footprint "eagle-import:R0805")
      (libsource (lib "eagle-import") (part "RES-0805"))
    )
    (comp (ref "R24")
      (value "22,1%")
      (footprint "eagle-import:R0805")
      (libsource (lib "eagle-import") (part "RES-0805"))
    )
    (comp (ref "R25")
      (value "47K,1%")
      (footprint "eagle-import:R0805")
      (libsource (lib "eagle-import") (part "RES-0805"))
    )
    (comp (ref "R26")
      (value "0 Ohm")
      (footprint "eagle-import:R0805")
      (libsource (lib "eagle-import") (part "RES-0805"))
    )
    (comp (ref "R27")
      (value "10K,1%")
      (footprint "eagle-import:R0805")
      (libsource (lib "eagle-import") (part "RES-0805"))
    )
    (comp (ref "R28")
      (value "4.7K,1%")
      (footprint "eagle-import:R0805")
      (libsource (lib "eagle-import") (part "RES-0805"))
    )
    (comp (ref "R29")
      (value "4.7K,1%")
      (footprint "eagle-import:R0805")
      (libsource (lib "eagle-import") (part "RES-0805"))
    )
    (comp (ref "R123")
      (value "TBD")
      (footprint "eagle-import:R0805")
      (libsource (lib "eagle-import") (part "RES-0805"))
    )
    (comp (ref "R124")
      (value "TBD")
      (footprint "eagle-import:R0805")
      (libsource (lib "eagle-import") (part "RES-0805"))
    )
    (comp (ref "R125")
      (value "TBD")
      (footprint "eagle-import:R0805")
      (libsource (lib "eagle-import") (part "RES-0805"))
    )
    (comp (ref "R126")
      (value "TBD")
      (footprint "eagle-import:R0805")
      (libsource (lib "eagle-import") (part "RES-0805"))
    )
    (comp (ref "S1")
      (value "SGND")
      (footprint "eagle-import:SGND")
      (libsource (lib "eagle-import") (part "SGND"))
    )
    (comp (ref "S2")
      (value "SGND")
      (footprint "eagle-import:SGND")
      (libsource (lib "eagle-import") (part "SGND"))
    )
    (comp (ref "S3")
      (value "SGND")
      (footprint "eagle-import:SGND")
      (libsource (lib "eagle-import") (part "SGND"))
    )
    (comp (ref "S4")
      (value "SGND")
      (footprint "eagle-import:SGND")
      (libsource (lib "eagle-import") (part "SGND"))
    )
    (comp (ref "S5")
      (value "SGND")
      (footprint "eagle-import:SGND")
      (libsource (lib "eagle-import") (part "SGND"))
    )
    (comp (ref "S6")
      (value "SGND")
      (footprint "eagle-import:SGND")
      (libsource (lib "eagle-import") (part "SGND"))
    )
    (comp (ref "S8")
      (value "SGND")
      (footprint "eagle-import:SGND")
      (libsource (lib "eagle-import") (part "SGND"))
    )
    (comp (ref "S9")
      (value "SGND")
      (footprint "eagle-import:SGND")
      (libsource (lib "eagle-import") (part "SGND"))
    )
    (comp (ref "S10")
      (value "SGND")
      (footprint "eagle-import:SGND")
      (libsource (lib "eagle-import") (part "SGND"))
    )
    (comp (ref "S11")
      (value "SGND")
      (footprint "eagle-import:SGND")
      (libsource (lib "eagle-import") (part "SGND"))
    )
    (comp (ref "S12")
      (value "SGND")
      (footprint "eagle-import:SGND")
      (libsource (lib "eagle-import") (part "SGND"))
    )
    (comp (ref "S14")
      (value "SGND")
      (footprint "eagle-import:SGND")
      (libsource (lib "eagle-import") (part "SGND"))
    )
    (comp (ref "S15")
      (value "SGND")
      (footprint "eagle-import:SGND")
      (libsource (lib "eagle-import") (part "SGND"))
    )
    (comp (ref "S16")
      (value "SGND")
      (footprint "eagle-import:SGND")
      (libsource (lib "eagle-import") (part "SGND"))
    )
    (comp (ref "S17")
      (value "SGND")
      (footprint "eagle-import:SGND")
      (libsource (lib "eagle-import") (part "SGND"))
    )
    (comp (ref "S18")
      (value "SGND")
      (footprint "eagle-import:SGND")
      (libsource (lib "eagle-import") (part "SGND"))
    )
    (comp (ref "S20")
      (value "SGND")
      (footprint "eagle-import:SGND")
      (libsource (lib "eagle-import") (part "SGND"))
    )
    (comp (ref "S21")
      (value "SGND")
      (footprint "eagle-import:SGND")
      (libsource (lib "eagle-import") (part "SGND"))
    )
    (comp (ref "S22")
      (value "SGND")
      (footprint "eagle-import:SGND")
      (libsource (lib "eagle-import") (part "SGND"))
    )
    (comp (ref "S23")
      (value "SGND")
      (footprint "eagle-import:SGND")
      (libsource (lib "eagle-import") (part "SGND"))
    )
    (comp (ref "S24")
      (value "SGND")
      (footprint "eagle-import:SGND")
      (libsource (lib "eagle-import") (part "SGND"))
    )
    (comp (ref "S25")
      (value "SGND")
      (footprint "eagle-import:SGND")
      (libsource (lib "eagle-import") (part "SGND"))
    )
    (comp (ref "S26")
      (value "SGND")
      (footprint "eagle-import:SGND")
      (libsource (lib "eagle-import") (part "SGND"))
    )
    (comp (ref "S27")
      (value "SGND")
      (footprint "eagle-import:SGND")
      (libsource (lib "eagle-import") (part "SGND"))
    )
    (comp (ref "S28")
      (value "SGND")
      (footprint "eagle-import:SGND")
      (libsource (lib "eagle-import") (part "SGND"))
    )
    (comp (ref "S29")
      (value "SGND")
      (footprint "eagle-import:SGND")
      (libsource (lib "eagle-import") (part "SGND"))
    )
    (comp (ref "S30")
      (value "SGND")
      (footprint "eagle-import:SGND")
      (libsource (lib "eagle-import") (part "SGND"))
    )
    (comp (ref "S31")
      (value "SGND")
      (footprint "eagle-import:SGND")
      (libsource (lib "eagle-import") (part "SGND"))
    )
    (comp (ref "S35")
      (value "SGND")
      (footprint "eagle-import:SGND")
      (libsource (lib "eagle-import") (part "SGND"))
    )
    (comp (ref "S36")
      (value "SGND")
      (footprint "eagle-import:SGND")
      (libsource (lib "eagle-import") (part "SGND"))
    )
    (comp (ref "S37")
      (value "SGND")
      (footprint "eagle-import:SGND")
      (libsource (lib "eagle-import") (part "SGND"))
    )
    (comp (ref "S38")
      (value "SGND")
      (footprint "eagle-import:SGND")
      (libsource (lib "eagle-import") (part "SGND"))
    )
    (comp (ref "S39")
      (value "SGND")
      (footprint "eagle-import:SGND")
      (libsource (lib "eagle-import") (part "SGND"))
    )
    (comp (ref "S40")
      (value "SGND")
      (footprint "eagle-import:SGND")
      (libsource (lib "eagle-import") (part "SGND"))
    )
    (comp (ref "S43")
      (value "SGND")
      (footprint "eagle-import:SGND")
      (libsource (lib "eagle-import") (part "SGND"))
    )
    (comp (ref "SH1")
      (value "SHUNT,0.1IN")
      (footprint "eagle-import:NOPACKAGE")
      (libsource (lib "eagle-import") (part "SHUNT,0.1IN"))
    )
    (comp (ref "SW1")
      (value "TS-02B")
      (footprint "eagle-import:TS-02B")
      (libsource (lib "eagle-import") (part "TS-02B"))
    )
    (comp (ref "SW2")
      (value "SW-LC2259")
      (footprint "eagle-import:SW-LC2259")
      (libsource (lib "eagle-import") (part "SW-LC2259"))
    )
    (comp (ref "SW3")
      (value "TS-026")
      (footprint "eagle-import:TS-026")
      (libsource (lib "eagle-import") (part "TS-026"))
    )
    (comp (ref "SW4")
      (value "TS-026")
      (footprint "eagle-import:TS-026")
      (libsource (lib "eagle-import") (part "TS-026"))
    )
    (comp (ref "U1")
      (value "STM32F405VGT6")
      (footprint "eagle-import:LQFP100-14")
      (libsource (lib "eagle-import") (part "STM32F407"))
    )
    (comp (ref "U2")
      (value "STMPS2141")
      (footprint "eagle-import:SOT23-5L")
      (libsource (lib "eagle-import") (part "STMPS2141"))
    )
    (comp (ref "U3")
      (value "EMIF02-USB03F2")
      (footprint "eagle-import:ECOPACK-11")
      (libsource (lib "eagle-import") (part "EMIF02-USB03F2"))
    )
    (comp (ref "U4")
      (value "DNL")
      (footprint "eagle-import:SOIC8")
      (libsource (lib "eagle-import") (part "I2C-EEPROM-256K"))
    )
    (comp (ref "XTAL1")
      (value "8.000MHz")
      (footprint "eagle-import:CTS-405")
      (libsource (lib "eagle-import") (part "CTS-405"))
    )
    (comp (ref "C83")
      (value "2-12pF")
      (footprint "eagle-import:TRIMCAP_VAR_2222_V")
      (libsource (lib "eagle-import") (part "TRIMCAP_VAR_2222_V"))
    )
    (comp (ref "C111")
      (value "100nF,25V")
      (footprint "eagle-import:C0805")
      (libsource (lib "eagle-import") (part "CAP-0805"))
    )
    (comp (ref "C112")
      (value "39pF,50V")
      (footprint "eagle-import:C0805")
      (libsource (lib "eagle-import") (part "CAP-0805"))
    )
    (comp (ref "C113")
      (value "100nF,25V")
      (footprint "eagle-import:C0805")
      (libsource (lib "eagle-import") (part "CAP-0805"))
    )
    (comp (ref "C114")
      (value "100nF,25V")
      (footprint "eagle-import:C0805")
      (libsource (lib "eagle-import") (part "CAP-0805"))
    )
    (comp (ref "C115")
      (value "5.6pF,50V")
      (footprint "eagle-import:C0805")
      (libsource (lib "eagle-import") (part "CAP-0805"))
    )
    (comp (ref "C117")
      (value "100nF,25V")
      (footprint "eagle-import:C0805")
      (libsource (lib "eagle-import") (part "CAP-0805"))
    )
    (comp (ref "C118")
      (value "100nF,25V")
      (footprint "eagle-import:C0805")
      (libsource (lib "eagle-import") (part "CAP-0805"))
    )
    (comp (ref "C119")
      (value "100nF,25V")
      (footprint "eagle-import:C0805")
      (libsource (lib "eagle-import") (part "CAP-0805"))
    )
    (comp (ref "C120")
      (value "100nF,25V")
      (footprint "eagle-import:C0805")
      (libsource (lib "eagle-import") (part "CAP-0805"))
    )
    (comp (ref "C121")
      (value "100nF,25V")
      (footprint "eagle-import:C0805")
      (libsource (lib "eagle-import") (part "CAP-0805"))
    )
    (comp (ref "C122")
      (value "10uF,25V,EL")
      (footprint "eagle-import:NICHICON-WJ-5")
      (libsource (lib "eagle-import") (part "CAP-10UF-WJ5"))
    )
    (comp (ref "C123")
      (value "27pF,50V")
      (footprint "eagle-import:C0805")
      (libsource (lib "eagle-import") (part "CAP-0805"))
    )
    (comp (ref "C124")
      (value "150pF,50V")
      (footprint "eagle-import:C0805")
      (libsource (lib "eagle-import") (part "CAP-0805"))
    )
    (comp (ref "C125")
      (value "100nF,25V")
      (footprint "eagle-import:C0805")
      (libsource (lib "eagle-import") (part "CAP-0805"))
    )
    (comp (ref "C126")
      (value "10uF,25V,EL")
      (footprint "eagle-import:NICHICON-WJ-5")
      (libsource (lib "eagle-import") (part "CAP-10UF-WJ5"))
    )
    (comp (ref "C127")
      (value "100nF,25V")
      (footprint "eagle-import:C0805")
      (libsource (lib "eagle-import") (part "CAP-0805"))
    )
    (comp (ref "C128")
      (value "150pF,50V")
      (footprint "eagle-import:C0805")
      (libsource (lib "eagle-import") (part "CAP-0805"))
    )
    (comp (ref "C129")
      (value "10uF,25V,EL")
      (footprint "eagle-import:NICHICON-WJ-5")
      (libsource (lib "eagle-import") (part "CAP-10UF-WJ5"))
    )
    (comp (ref "C130")
      (value "10uF,25V,EL")
      (footprint "eagle-import:NICHICON-WJ-5")
      (libsource (lib "eagle-import") (part "CAP-10UF-WJ5"))
    )
    (comp (ref "C131")
      (value "1nF,25V")
      (footprint "eagle-import:C0805")
      (libsource (lib "eagle-import") (part "CAP-0805"))
    )
    (comp (ref "C132")
      (value "1nF,25V")
      (footprint "eagle-import:C0805")
      (libsource (lib "eagle-import") (part "CAP-0805"))
    )
    (comp (ref "C133")
      (value "100nF,25V")
      (footprint "eagle-import:C0805")
      (libsource (lib "eagle-import") (part "CAP-0805"))
    )
    (comp (ref "C134")
      (value "100nF,25V")
      (footprint "eagle-import:C0805")
      (libsource (lib "eagle-import") (part "CAP-0805"))
    )
    (comp (ref "C135")
      (value "1nF,25V")
      (footprint "eagle-import:C0805")
      (libsource (lib "eagle-import") (part "CAP-0805"))
    )
    (comp (ref "C136")
      (value "10uF,25V,EL")
      (footprint "eagle-import:NICHICON-WJ-5")
      (libsource (lib "eagle-import") (part "CAP-10UF-WJ5"))
    )
    (comp (ref "C144")
      (value "100nF,25V")
      (footprint "eagle-import:C0805")
      (libsource (lib "eagle-import") (part "CAP-0805"))
    )
    (comp (ref "FB13")
      (value "FB0805")
      (footprint "eagle-import:FE0805")
      (libsource (lib "eagle-import") (part "FB0805"))
    )
    (comp (ref "FB14")
      (value "FB0805")
      (footprint "eagle-import:FE0805")
      (libsource (lib "eagle-import") (part "FB0805"))
    )
    (comp (ref "FB15")
      (value "FB0805")
      (footprint "eagle-import:FE0805")
      (libsource (lib "eagle-import") (part "FB0805"))
    )
    (comp (ref "FB16")
      (value "FB0805")
      (footprint "eagle-import:FE0805")
      (libsource (lib "eagle-import") (part "FB0805"))
    )
    (comp (ref "FB17")
      (value "FB0805")
      (footprint "eagle-import:FE0805")
      (libsource (lib "eagle-import") (part "FB0805"))
    )
    (comp (ref "FB18")
      (value "FB0805")
      (footprint "eagle-import:FE0805")
      (libsource (lib "eagle-import") (part "FB0805"))
    )
    (comp (ref "FB19")
      (value "FB0805")
      (footprint "eagle-import:FE0805")
      (libsource (lib "eagle-import") (part "FB0805"))
    )
    (comp (ref "J13")
      (value "JMPR-2X2")
      (footprint "eagle-import:JMPR-2X2X.1")
      (libsource (lib "eagle-import") (part "JMPR-2X2"))
    )
    (comp (ref "J14")
      (value "JMPR-2X2")
      (footprint "eagle-import:JMPR-2X2X.1")
      (libsource (lib "eagle-import") (part "JMPR-2X2"))
    )
    (comp (ref "L17")
      (value "5.7uH")
      (footprint "eagle-import:L-TDK-MLF2012")
      (libsource (lib "eagle-import") (part "L-TDK-MLF-2012"))
    )
    (comp (ref "L18")
      (value "L-TDK-MLF-2012-9.2uH")
      (footprint "eagle-import:L-TDK-MLF2012")
      (libsource (lib "eagle-import") (part "L-TDK-MLF-2012"))
    )
    (comp (ref "L19")
      (value "5.2uH")
      (footprint "eagle-import:L-TDK-MLF2012")
      (libsource (lib "eagle-import") (part "L-TDK-MLF-2012"))
    )
    (comp (ref "L20")
      (value "15uH,TDK,MLF")
      (footprint "eagle-import:L-TDK-MLF2012")
      (libsource (lib "eagle-import") (part "L-TDK-MLF-2012"))
    )
    (comp (ref "Q14")
      (value "MMBT3904")
      (footprint "eagle-import:SOT23")
      (libsource (lib "eagle-import") (part "MMBT3904"))
    )
    (comp (ref "Q15")
      (value "MMBT3904")
      (footprint "eagle-import:SOT23")
      (libsource (lib "eagle-import") (part "MMBT3904"))
    )
    (comp (ref "Q16")
      (value "MMBT3904")
      (footprint "eagle-import:SOT23")
      (libsource (lib "eagle-import") (part "MMBT3904"))
    )
    (comp (ref "Q17")
      (value "MMBT3906")
      (footprint "eagle-import:SOT23")
      (libsource (lib "eagle-import") (part "MMBT3906"))
    )
    (comp (ref "R96")
      (value "0 Ohm")
      (footprint "eagle-import:R0805")
      (libsource (lib "eagle-import") (part "RES-0805"))
    )
    (comp (ref "R97")
      (value "0 Ohm")
      (footprint "eagle-import:R0805")
      (libsource (lib "eagle-import") (part "RES-0805"))
    )
    (comp (ref "R98")
      (value "0 Ohm")
      (footprint "eagle-import:R0805")
      (libsource (lib "eagle-import") (part "RES-0805"))
    )
    (comp (ref "R99")
      (value "1K,1%")
      (footprint "eagle-import:R0805")
      (libsource (lib "eagle-import") (part "RES-0805"))
    )
    (comp (ref "R100")
      (value "1K,1%")
      (footprint "eagle-import:R0805")
      (libsource (lib "eagle-import") (part "RES-0805"))
    )
    (comp (ref "R101")
      (value "150,1%")
      (footprint "eagle-import:R0805")
      (libsource (lib "eagle-import") (part "RES-0805"))
    )
    (comp (ref "R102")
      (value "150,1%")
      (footprint "eagle-import:R0805")
      (libsource (lib "eagle-import") (part "RES-0805"))
    )
    (comp (ref "R103")
      (value "33K,1%")
      (footprint "eagle-import:R0805")
      (libsource (lib "eagle-import") (part "RES-0805"))
    )
    (comp (ref "R104")
      (value "15K,1%")
      (footprint "eagle-import:R0805")
      (libsource (lib "eagle-import") (part "RES-0805"))
    )
    (comp (ref "R105")
      (value "3K,1%")
      (footprint "eagle-import:R0805")
      (libsource (lib "eagle-import") (part "RES-0805"))
    )
    (comp (ref "R106")
      (value "1K,1%")
      (footprint "eagle-import:R0805")
      (libsource (lib "eagle-import") (part "RES-0805"))
    )
    (comp (ref "R107")
      (value "1K,1%")
      (footprint "eagle-import:R0805")
      (libsource (lib "eagle-import") (part "RES-0805"))
    )
    (comp (ref "R108")
      (value "10,1%")
      (footprint "eagle-import:R0805")
      (libsource (lib "eagle-import") (part "RES-0805"))
    )
    (comp (ref "R109")
      (value "49.9,1%")
      (footprint "eagle-import:R0805")
      (libsource (lib "eagle-import") (part "RES-0805"))
    )
    (comp (ref "R110")
      (value "39K,1%")
      (footprint "eagle-import:R0805")
      (libsource (lib "eagle-import") (part "RES-0805"))
    )
    (comp (ref "R111")
      (value "18K,1%")
      (footprint "eagle-import:R0805")
      (libsource (lib "eagle-import") (part "RES-0805"))
    )
    (comp (ref "R112")
      (value "2.2K,1%")
      (footprint "eagle-import:R0805")
      (libsource (lib "eagle-import") (part "RES-0805"))
    )
    (comp (ref "R113")
      (value "1K,1%")
      (footprint "eagle-import:R0805")
      (libsource (lib "eagle-import") (part "RES-0805"))
    )
    (comp (ref "R114")
      (value "100,1%")
      (footprint "eagle-import:R0805")
      (libsource (lib "eagle-import") (part "RES-0805"))
    )
    (comp (ref "R115")
      (value "10,1%")
      (footprint "eagle-import:R0805")
      (libsource (lib "eagle-import") (part "RES-0805"))
    )
    (comp (ref "R116")
      (value "150,1%")
      (footprint "eagle-import:R0805")
      (libsource (lib "eagle-import") (part "RES-0805"))
    )
    (comp (ref "R117")
      (value "3.3K,1%")
      (footprint "eagle-import:R0805")
      (libsource (lib "eagle-import") (part "RES-0805"))
    )
    (comp (ref "R118")
      (value "3.3K,1%")
      (footprint "eagle-import:R0805")
      (libsource (lib "eagle-import") (part "RES-0805"))
    )
    (comp (ref "R119")
      (value "100,1%")
      (footprint "eagle-import:R0805")
      (libsource (lib "eagle-import") (part "RES-0805"))
    )
    (comp (ref "R120")
      (value "10,1%")
      (footprint "eagle-import:R0805")
      (libsource (lib "eagle-import") (part "RES-0805"))
    )
    (comp (ref "SP1")
      (value "SCOPE_PAD")
      (footprint "eagle-import:SCOPE_PAD")
      (libsource (lib "eagle-import") (part "SCOPE_PAD"))
    )
    (comp (ref "SP3")
      (value "SCOPE_PAD")
      (footprint "eagle-import:SCOPE_PAD")
      (libsource (lib "eagle-import") (part "SCOPE_PAD"))
    )
    (comp (ref "SP6")
      (value "SCOPE_PAD")
      (footprint "eagle-import:SCOPE_PAD")
      (libsource (lib "eagle-import") (part "SCOPE_PAD"))
    )
    (comp (ref "SP7")
      (value "SCOPE_PAD")
      (footprint "eagle-import:SCOPE_PAD")
      (libsource (lib "eagle-import") (part "SCOPE_PAD"))
    )
    (comp (ref "SP8")
      (value "SCOPE_PAD")
      (footprint "eagle-import:SCOPE_PAD")
      (libsource (lib "eagle-import") (part "SCOPE_PAD"))
    )
    (comp (ref "U14")
      (value "SI5351A")
      (footprint "eagle-import:MSOP10")
      (libsource (lib "eagle-import") (part "SI5351A"))
    )
    (comp (ref "U15")
      (value "SI570")
      (footprint "eagle-import:SI570")
      (libsource (lib "eagle-import") (part "SI570"))
    )
    (comp (ref "U16")
      (value "SA612A")
      (footprint "eagle-import:SO-08")
      (libsource (lib "eagle-import") (part "SA612A"))
    )
    (comp (ref "XTAL2")
      (value "25.000MHz")
      (footprint "eagle-import:CTS-405")
      (libsource (lib "eagle-import") (part "CTS-405"))
    )
    (comp (ref "XTAL3")
      (value "ECS-10.7-15B")
      (footprint "eagle-import:HC49U")
      (libsource (lib "eagle-import") (part "ECS-10.7-15BECS-10.7-12A"))
    )
    (comp (ref "XTAL4")
      (value "ECS-10.7-15B")
      (footprint "eagle-import:HC49U")
      (libsource (lib "eagle-import") (part "ECS-10.7-15BECS-10.7-12A"))
    )
    (comp (ref "C23")
      (value ".33uF,25V")
      (footprint "eagle-import:C0805")
      (libsource (lib "eagle-import") (part "CAP-0805"))
    )
    (comp (ref "C24")
      (value "100nF,25V")
      (footprint "eagle-import:C0805")
      (libsource (lib "eagle-import") (part "CAP-0805"))
    )
    (comp (ref "C25")
      (value "10nF,25V")
      (footprint "eagle-import:C0805")
      (libsource (lib "eagle-import") (part "CAP-0805"))
    )
    (comp (ref "C26")
      (value "22uF,25V")
      (footprint "eagle-import:C1210")
      (libsource (lib "eagle-import") (part "CAP-1210"))
    )
    (comp (ref "C27")
      (value "1nF,25V")
      (footprint "eagle-import:C0805")
      (libsource (lib "eagle-import") (part "CAP-0805"))
    )
    (comp (ref "C28")
      (value "220nF,25V")
      (footprint "eagle-import:C0805")
      (libsource (lib "eagle-import") (part "CAP-0805"))
    )
    (comp (ref "C29")
      (value "22uF,25V")
      (footprint "eagle-import:C1210")
      (libsource (lib "eagle-import") (part "CAP-1210"))
    )
    (comp (ref "C30")
      (value "100nF,25V")
      (footprint "eagle-import:C0805")
      (libsource (lib "eagle-import") (part "CAP-0805"))
    )
    (comp (ref "C31")
      (value "100uF,6.3V,EL")
      (footprint "eagle-import:NICHICON-WX-6.3")
      (libsource (lib "eagle-import") (part "NICHICON-WX-6.3"))
    )
    (comp (ref "C32")
      (value "100uF,6.3V,EL")
      (footprint "eagle-import:NICHICON-WX-6.3")
      (libsource (lib "eagle-import") (part "NICHICON-WX-6.3"))
    )
    (comp (ref "C33")
      (value "100nF,25V")
      (footprint "eagle-import:C0805")
      (libsource (lib "eagle-import") (part "CAP-0805"))
    )
    (comp (ref "C34")
      (value "220uF,25V")
      (footprint "eagle-import:CAP-CHEMI-HA0")
      (libsource (lib "eagle-import") (part "CAP-CHEMI-MVE-HA0"))
    )
    (comp (ref "C35")
      (value "100nF,25V")
      (footprint "eagle-import:C0805")
      (libsource (lib "eagle-import") (part "CAP-0805"))
    )
    (comp (ref "C36")
      (value "22uF,25V")
      (footprint "eagle-import:C1210")
      (libsource (lib "eagle-import") (part "CAP-1210"))
    )
    (comp (ref "C37")
      (value "100nF,25V")
      (footprint "eagle-import:C0805")
      (libsource (lib "eagle-import") (part "CAP-0805"))
    )
    (comp (ref "C38")
      (value "2.2uF,25V")
      (footprint "eagle-import:C0805")
      (libsource (lib "eagle-import") (part "CAP-0805"))
    )
    (comp (ref "C39")
      (value "100pF,50V")
      (footprint "eagle-import:C0805")
      (libsource (lib "eagle-import") (part "CAP-0805"))
    )
    (comp (ref "C40")
      (value "1nF,25V")
      (footprint "eagle-import:C0805")
      (libsource (lib "eagle-import") (part "CAP-0805"))
    )
    (comp (ref "C41")
      (value "100nF,25V")
      (footprint "eagle-import:C0805")
      (libsource (lib "eagle-import") (part "CAP-0805"))
    )
    (comp (ref "C42")
      (value "22uF,25V")
      (footprint "eagle-import:C1210")
      (libsource (lib "eagle-import") (part "CAP-1210"))
    )
    (comp (ref "C43")
      (value "22uF,25V")
      (footprint "eagle-import:C1210")
      (libsource (lib "eagle-import") (part "CAP-1210"))
    )
    (comp (ref "C44")
      (value "22uF,25V")
      (footprint "eagle-import:C1210")
      (libsource (lib "eagle-import") (part "CAP-1210"))
    )
    (comp (ref "C45")
      (value "100nF,25V")
      (footprint "eagle-import:C0805")
      (libsource (lib "eagle-import") (part "CAP-0805"))
    )
    (comp (ref "C46")
      (value "470nF,25V")
      (footprint "eagle-import:C0805")
      (libsource (lib "eagle-import") (part "CAP-0805"))
    )
    (comp (ref "C47")
      (value "8.2nF,25V")
      (footprint "eagle-import:C0805")
      (libsource (lib "eagle-import") (part "CAP-0805"))
    )
    (comp (ref "C48")
      (value "100nF,25V")
      (footprint "eagle-import:C0805")
      (libsource (lib "eagle-import") (part "CAP-0805"))
    )
    (comp (ref "C49")
      (value "100nF,25V")
      (footprint "eagle-import:C0805")
      (libsource (lib "eagle-import") (part "CAP-0805"))
    )
    (comp (ref "C50")
      (value "3.9nF,25V")
      (footprint "eagle-import:C0805")
      (libsource (lib "eagle-import") (part "CAP-0805"))
    )
    (comp (ref "C51")
      (value "20pF,50V")
      (footprint "eagle-import:C0805")
      (libsource (lib "eagle-import") (part "CAP-0805"))
    )
    (comp (ref "C52")
      (value "220uF,25V")
      (footprint "eagle-import:CAP-CHEMI-HA0")
      (libsource (lib "eagle-import") (part "CAP-CHEMI-MVE-HA0"))
    )
    (comp (ref "C53")
      (value "47nF,25V")
      (footprint "eagle-import:C0805")
      (libsource (lib "eagle-import") (part "CAP-0805"))
    )
    (comp (ref "C54")
      (value "22uF,25V")
      (footprint "eagle-import:C1210")
      (libsource (lib "eagle-import") (part "CAP-1210"))
    )
    (comp (ref "C55")
      (value "220uF,25V")
      (footprint "eagle-import:CAP-CHEMI-HA0")
      (libsource (lib "eagle-import") (part "CAP-CHEMI-MVE-HA0"))
    )
    (comp (ref "C56")
      (value "100nF,25V")
      (footprint "eagle-import:C0805")
      (libsource (lib "eagle-import") (part "CAP-0805"))
    )
    (comp (ref "C137")
      (value "100nF,25V")
      (footprint "eagle-import:C0805")
      (libsource (lib "eagle-import") (part "CAP-0805"))
    )
    (comp (ref "C138")
      (value "100nF,25V")
      (footprint "eagle-import:C0805")
      (libsource (lib "eagle-import") (part "CAP-0805"))
    )
    (comp (ref "CN5")
      (value "DS-0518")
      (footprint "eagle-import:DS-0518")
      (libsource (lib "eagle-import") (part "DS-0518"))
    )
    (comp (ref "CN6")
      (value "ST-3509")
      (footprint "eagle-import:ST-3509")
      (libsource (lib "eagle-import") (part "ST-3509"))
    )
    (comp (ref "CN7")
      (value "ST-3509")
      (footprint "eagle-import:ST-3509")
      (libsource (lib "eagle-import") (part "ST-3509"))
    )
    (comp (ref "D2")
      (value "DNL")
      (footprint "eagle-import:SOD523")
      (libsource (lib "eagle-import") (part "PESD5ZX"))
    )
    (comp (ref "D3")
      (value "PTVS20VP1UP")
      (footprint "eagle-import:SOD128")
      (libsource (lib "eagle-import") (part "PTVS20VP1UP"))
    )
    (comp (ref "D4")
      (value "B330B")
      (footprint "eagle-import:SMB")
      (libsource (lib "eagle-import") (part "B330B"))
    )
    (comp (ref "D5")
      (value "DNL")
      (footprint "eagle-import:SOD128")
      (libsource (lib "eagle-import") (part "PTVS20VP1UP"))
    )
    (comp (ref "FB2")
      (value "FB0805")
      (footprint "eagle-import:FE0805")
      (libsource (lib "eagle-import") (part "FB0805"))
    )
    (comp (ref "FB3")
      (value "FB0805")
      (footprint "eagle-import:FE0805")
      (libsource (lib "eagle-import") (part "FB0805"))
    )
    (comp (ref "FB4")
      (value "FB0805")
      (footprint "eagle-import:FE0805")
      (libsource (lib "eagle-import") (part "FB0805"))
    )
    (comp (ref "FB5")
      (value "FB0805")
      (footprint "eagle-import:FE0805")
      (libsource (lib "eagle-import") (part "FB0805"))
    )
    (comp (ref "FB20")
      (value "FB0805")
      (footprint "eagle-import:FE0805")
      (libsource (lib "eagle-import") (part "FB0805"))
    )
    (comp (ref "J3")
      (value "JMP-2PIN")
      (footprint "eagle-import:JMPR-2PIN")
      (libsource (lib "eagle-import") (part "JMP-2PIN"))
    )
    (comp (ref "J4")
      (value "CONN-BOOM-XH-2A")
      (footprint "eagle-import:CONN-BOOM-XH-2A")
      (libsource (lib "eagle-import") (part "CONN-BOOM-XH-2A"))
    )
    (comp (ref "J5")
      (value "JMP-2PIN")
      (footprint "eagle-import:JMPR-2PIN")
      (libsource (lib "eagle-import") (part "JMP-2PIN"))
    )
    (comp (ref "L1")
      (value "4.2uH")
      (footprint "eagle-import:SRR5028")
      (libsource (lib "eagle-import") (part "SRR5028"))
    )
    (comp (ref "LED5")
      (value "SML-LX0603GW")
      (footprint "eagle-import:SML-LX0603SRW")
      (libsource (lib "eagle-import") (part "SML-LX0603SRW"))
    )
    (comp (ref "LED6")
      (value "SML-LX0603GW")
      (footprint "eagle-import:SML-LX0603SRW")
      (libsource (lib "eagle-import") (part "SML-LX0603SRW"))
    )
    (comp (ref "LED7")
      (value "LTST-S220KGKT")
      (footprint "eagle-import:LTST-S2200K")
      (libsource (lib "eagle-import") (part "LTST-S220K"))
    )
    (comp (ref "LED8")
      (value "SML-LX0603GW")
      (footprint "eagle-import:SML-LX0603SRW")
      (libsource (lib "eagle-import") (part "SML-LX0603SRW"))
    )
    (comp (ref "LED9")
      (value "SML-LX0603SRW")
      (footprint "eagle-import:SML-LX0603SRW")
      (libsource (lib "eagle-import") (part "SML-LX0603SRW"))
    )
    (comp (ref "LED10")
      (value "SML-LX0603GW")
      (footprint "eagle-import:SML-LX0603SRW")
      (libsource (lib "eagle-import") (part "SML-LX0603SRW"))
    )
    (comp (ref "LED11")
      (value "SML-LX0603YW")
      (footprint "eagle-import:SML-LX0603SRW")
      (libsource (lib "eagle-import") (part "SML-LX0603SRW"))
    )
    (comp (ref "MIC1")
      (value "CMA-4544PF-W")
      (footprint "eagle-import:CMA-4544PF-W")
      (libsource (lib "eagle-import") (part "CMA-4544PF-W"))
    )
    (comp (ref "Q1")
      (value "MMBT3904")
      (footprint "eagle-import:SOT23")
      (libsource (lib "eagle-import") (part "MMBT3904"))
    )
    (comp (ref "Q2")
      (value "STR2P3LLH6")
      (footprint "eagle-import:SOT23")
      (libsource (lib "eagle-import") (part "STR2P3LLH6"))
    )
    (comp (ref "Q3")
      (value "MMBT3904")
      (footprint "eagle-import:SOT23")
      (libsource (lib "eagle-import") (part "MMBT3904"))
    )
    (comp (ref "Q4")
      (value "STR2P3LLH6")
      (footprint "eagle-import:SOT23")
      (libsource (lib "eagle-import") (part "STR2P3LLH6"))
    )
    (comp (ref "R30")
      (value "1.5K,1%")
      (footprint "eagle-import:R0805")
      (libsource (lib "eagle-import") (part "RES-0805"))
    )
    (comp (ref "R31")
      (value "100,1%")
      (footprint "eagle-import:R0805")
      (libsource (lib "eagle-import") (part "RES-0805"))
    )
    (comp (ref "R32")
      (value "100,1%")
      (footprint "eagle-import:R0805")
      (libsource (lib "eagle-import") (part "RES-0805"))
    )
    (comp (ref "R33")
      (value "2.2K,1%")
      (footprint "eagle-import:R0805")
      (libsource (lib "eagle-import") (part "RES-0805"))
    )
    (comp (ref "R34")
      (value "330,1%")
      (footprint "eagle-import:R0805")
      (libsource (lib "eagle-import") (part "RES-0805"))
    )
    (comp (ref "R35")
      (value "2.2K,1%")
      (footprint "eagle-import:R0805")
      (libsource (lib "eagle-import") (part "RES-0805"))
    )
    (comp (ref "R36")
      (value "2.2K,1%")
      (footprint "eagle-import:R0805")
      (libsource (lib "eagle-import") (part "RES-0805"))
    )
    (comp (ref "R37")
      (value "2.2K,1%")
      (footprint "eagle-import:R0805")
      (libsource (lib "eagle-import") (part "RES-0805"))
    )
    (comp (ref "R38")
      (value "2.2K,1%")
      (footprint "eagle-import:R0805")
      (libsource (lib "eagle-import") (part "RES-0805"))
    )
    (comp (ref "R39")
      (value "500K,TrimPOT")
      (footprint "eagle-import:POT3361")
      (libsource (lib "eagle-import") (part "POT3361"))
    )
    (comp (ref "R40")
      (value "330,1%")
      (footprint "eagle-import:R0805")
      (libsource (lib "eagle-import") (part "RES-0805"))
    )
    (comp (ref "R41")
      (value "0 Ohm")
      (footprint "eagle-import:R0805")
      (libsource (lib "eagle-import") (part "RES-0805"))
    )
    (comp (ref "R42")
      (value "1.5K,1%")
      (footprint "eagle-import:R0805")
      (libsource (lib "eagle-import") (part "RES-0805"))
    )
    (comp (ref "R43")
      (value "10K,1%")
      (footprint "eagle-import:R0805")
      (libsource (lib "eagle-import") (part "RES-0805"))
    )
    (comp (ref "R44")
      (value "330,1%")
      (footprint "eagle-import:R0805")
      (libsource (lib "eagle-import") (part "RES-0805"))
    )
    (comp (ref "R45")
      (value "22.1K,1%")
      (footprint "eagle-import:R0805")
      (libsource (lib "eagle-import") (part "RES-0805"))
    )
    (comp (ref "R46")
      (value "10K,1%")
      (footprint "eagle-import:R0805")
      (libsource (lib "eagle-import") (part "RES-0805"))
    )
    (comp (ref "R47")
      (value "2.2K,1%")
      (footprint "eagle-import:R0805")
      (libsource (lib "eagle-import") (part "RES-0805"))
    )
    (comp (ref "R48")
      (value "100K,POT")
      (footprint "eagle-import:POT-3310C")
      (libsource (lib "eagle-import") (part "POT-3310C"))
    )
    (comp (ref "R49")
      (value "4.7,0.5W,1206")
      (footprint "eagle-import:R1206")
      (libsource (lib "eagle-import") (part "RES-1206"))
    )
    (comp (ref "R50")
      (value "1K,1%")
      (footprint "eagle-import:R0805")
      (libsource (lib "eagle-import") (part "RES-0805"))
    )
    (comp (ref "R51")
      (value "124.0K,1%")
      (footprint "eagle-import:R0805")
      (libsource (lib "eagle-import") (part "RES-0805"))
    )
    (comp (ref "R52")
      (value "22.1K,1%")
      (footprint "eagle-import:R0805")
      (libsource (lib "eagle-import") (part "RES-0805"))
    )
    (comp (ref "R53")
      (value "10,1%")
      (footprint "eagle-import:R0805")
      (libsource (lib "eagle-import") (part "RES-0805"))
    )
    (comp (ref "R54")
      (value "10K,1%")
      (footprint "eagle-import:R0805")
      (libsource (lib "eagle-import") (part "RES-0805"))
    )
    (comp (ref "R55")
      (value "680,1%")
      (footprint "eagle-import:R0805")
      (libsource (lib "eagle-import") (part "RES-0805"))
    )
    (comp (ref "R56")
      (value "2.2K,1%")
      (footprint "eagle-import:R0805")
      (libsource (lib "eagle-import") (part "RES-0805"))
    )
    (comp (ref "R57")
      (value "1K,1%")
      (footprint "eagle-import:R0805")
      (libsource (lib "eagle-import") (part "RES-0805"))
    )
    (comp (ref "SH2")
      (value "SHUNT,0.1IN")
      (footprint "eagle-import:NOPACKAGE")
      (libsource (lib "eagle-import") (part "SHUNT,0.1IN"))
    )
    (comp (ref "SH3")
      (value "SHUNT,0.1IN")
      (footprint "eagle-import:NOPACKAGE")
      (libsource (lib "eagle-import") (part "SHUNT,0.1IN"))
    )
    (comp (ref "SP2")
      (value "SCOPE_PAD")
      (footprint "eagle-import:SCOPE_PAD")
      (libsource (lib "eagle-import") (part "SCOPE_PAD"))
    )
    (comp (ref "SP4")
      (value "SCOPE_PAD")
      (footprint "eagle-import:SCOPE_PAD")
      (libsource (lib "eagle-import") (part "SCOPE_PAD"))
    )
    (comp (ref "SP9")
      (value "SCOPE_PAD")
      (footprint "eagle-import:SCOPE_PAD")
      (libsource (lib "eagle-import") (part "SCOPE_PAD"))
    )
    (comp (ref "SW5")
      (value "SW-LC2259EENP")
      (footprint "eagle-import:SW-LC2259")
      (libsource (lib "eagle-import") (part "SW-LC2259"))
    )
    (comp (ref "U5")
      (value "L78M09")
      (footprint "eagle-import:DPAK")
      (libsource (lib "eagle-import") (part "L78MXX"))
    )
    (comp (ref "U6")
      (value "LD1117AS-33")
      (footprint "eagle-import:SOT223")
      (libsource (lib "eagle-import") (part "LD1117AS33"))
    )
    (comp (ref "U7")
      (value "LMV341")
      (footprint "eagle-import:SOT23-6")
      (libsource (lib "eagle-import") (part "LMV341"))
    )
    (comp (ref "U8")
      (value "LD1117AS-33")
      (footprint "eagle-import:SOT223")
      (libsource (lib "eagle-import") (part "LD1117AS33"))
    )
    (comp (ref "U9")
      (value "TPS54329E")
      (footprint "eagle-import:PSO-DDA")
      (libsource (lib "eagle-import") (part "TPS54329E"))
    )
    (comp (ref "U10")
      (value "LM386M-1")
      (footprint "eagle-import:SO08")
      (libsource (lib "eagle-import") (part "LM386?-M1"))
    )
  )
  (nets
    (net (code "1") (name "+5V") (class "Default")
      (node (ref "C51") (pin "1") (pinfunction "1_1") (pintype "passive"))
      (node (ref "C54") (pin "1") (pinfunction "1_1") (pintype "passive"))
      (node (ref "FB16") (pin "2") (pinfunction "2_2") (pintype "passive"))
      (node (ref "FB17") (pin "1") (pinfunction "1_1") (pintype "passive"))
      (node (ref "FB19") (pin "2") (pinfunction "2_2") (pintype "passive"))
      (node (ref "FB20") (pin "1") (pinfunction "1_1") (pintype "passive"))
      (node (ref "FB4") (pin "1") (pinfunction "1_1") (pintype "passive"))
      (node (ref "L1") (pin "2") (pinfunction "2_2") (pintype "passive"))
      (node (ref "R51") (pin "1") (pinfunction "1_1") (pintype "passive"))
      (node (ref "R55") (pin "2") (pinfunction "2_2") (pintype "passive"))
      (node (ref "U2") (pin "5") (pinfunction "IN_5") (pintype "bidirectional"))
    )
    (net (code "2") (name "+9V") (class "Default")
      (node (ref "C108") (pin "1") (pinfunction "1_1") (pintype "passive"))
      (node (ref "C109") (pin "1") (pinfunction "1_1") (pintype "passive"))
      (node (ref "C24") (pin "1") (pinfunction "1_1") (pintype "passive"))
      (node (ref "L15") (pin "2") (pinfunction "2_2") (pintype "passive"))
      (node (ref "R30") (pin "2") (pinfunction "2_2") (pintype "passive"))
      (node (ref "U5") (pin "3") (pinfunction "OUT_3") (pintype "bidirectional"))
    )
    (net (code "3") (name "+12VRXENB") (class "Default")
      (node (ref "J2") (pin "7") (pinfunction "7_7") (pintype "bidirectional"))
      (node (ref "R46") (pin "1") (pinfunction "1_1") (pintype "passive"))
      (node (ref "U1") (pin "4") (pinfunction "PE5_4") (pintype "bidirectional"))
    )
    (net (code "4") (name "+12VTXENB") (class "Default")
      (node (ref "J2") (pin "6") (pinfunction "6_6") (pintype "bidirectional"))
      (node (ref "R54") (pin "1") (pinfunction "1_1") (pintype "passive"))
      (node (ref "U1") (pin "3") (pinfunction "PE4_3") (pintype "bidirectional"))
    )
    (net (code "5") (name "+VIN") (class "Default")
      (node (ref "C23") (pin "1") (pinfunction "1_1") (pintype "passive"))
      (node (ref "C34") (pin "1") (pinfunction "1_1") (pintype "passive"))
      (node (ref "C40") (pin "1") (pinfunction "1_1") (pintype "passive"))
      (node (ref "C41") (pin "1") (pinfunction "1_1") (pintype "passive"))
      (node (ref "C42") (pin "1") (pinfunction "1_1") (pintype "passive"))
      (node (ref "C43") (pin "1") (pinfunction "1_1") (pintype "passive"))
      (node (ref "C56") (pin "1") (pinfunction "1_1") (pintype "passive"))
      (node (ref "Q2") (pin "2") (pinfunction "S_2") (pintype "bidirectional"))
      (node (ref "Q4") (pin "2") (pinfunction "S_2") (pintype "bidirectional"))
      (node (ref "R40") (pin "2") (pinfunction "2_2") (pintype "passive"))
      (node (ref "R41") (pin "2") (pinfunction "2_2") (pintype "passive"))
      (node (ref "R43") (pin "1") (pinfunction "1_1") (pintype "passive"))
      (node (ref "R47") (pin "2") (pinfunction "2_2") (pintype "passive"))
      (node (ref "R49") (pin "1") (pinfunction "1_1") (pintype "passive"))
      (node (ref "R56") (pin "2") (pinfunction "2_2") (pintype "passive"))
      (node (ref "U5") (pin "1") (pinfunction "IN_1") (pintype "bidirectional"))
      (node (ref "U9") (pin "2") (pinfunction "VIN_2") (pintype "bidirectional"))
    )
    (net (code "6") (name "1ST_LO") (class "Default")
      (node (ref "R96") (pin "1") (pinfunction "1_1") (pintype "passive"))
      (node (ref "R97") (pin "1") (pinfunction "1_1") (pintype "passive"))
      (node (ref "R98") (pin "1") (pinfunction "1_1") (pintype "passive"))
      (node (ref "SP6") (pin "1") (pinfunction "1_1") (pintype "bidirectional"))
      (node (ref "U11") (pin "6") (pinfunction "LO_6") (pintype "bidirectional"))
    )
    (net (code "7") (name "3V3") (class "Default")
      (node (ref "C1") (pin "1") (pinfunction "1_1") (pintype "passive"))
      (node (ref "C14") (pin "1") (pinfunction "1_1") (pintype "passive"))
      (node (ref "C15") (pin "1") (pinfunction "1_1") (pintype "passive"))
      (node (ref "C2") (pin "1") (pinfunction "1_1") (pintype "passive"))
      (node (ref "C29") (pin "1") (pinfunction "1_1") (pintype "passive"))
      (node (ref "C3") (pin "1") (pinfunction "1_1") (pintype "passive"))
      (node (ref "C37") (pin "1") (pinfunction "1_1") (pintype "passive"))
      (node (ref "C5") (pin "1") (pinfunction "1_1") (pintype "passive"))
      (node (ref "C8") (pin "1") (pinfunction "1_1") (pintype "passive"))
      (node (ref "C9") (pin "1") (pinfunction "1_1") (pintype "passive"))
      (node (ref "FB13") (pin "1") (pinfunction "1_1") (pintype "passive"))
      (node (ref "FB14") (pin "1") (pinfunction "1_1") (pintype "passive"))
      (node (ref "FB15") (pin "1") (pinfunction "1_1") (pintype "passive"))
      (node (ref "R10") (pin "1") (pinfunction "1_1") (pintype "passive"))
      (node (ref "R14") (pin "1") (pinfunction "1_1") (pintype "passive"))
      (node (ref "R18") (pin "2") (pinfunction "2_2") (pintype "passive"))
      (node (ref "R20") (pin "1") (pinfunction "1_1") (pintype "passive"))
      (node (ref "R22") (pin "2") (pinfunction "2_2") (pintype "passive"))
      (node (ref "R25") (pin "1") (pinfunction "1_1") (pintype "passive"))
      (node (ref "R27") (pin "2") (pinfunction "2_2") (pintype "passive"))
      (node (ref "R28") (pin "1") (pinfunction "1_1") (pintype "passive"))
      (node (ref "R29") (pin "1") (pinfunction "1_1") (pintype "passive"))
      (node (ref "R34") (pin "2") (pinfunction "2_2") (pintype "passive"))
      (node (ref "R7") (pin "1") (pinfunction "1_1") (pintype "passive"))
      (node (ref "R8") (pin "1") (pinfunction "1_1") (pintype "passive"))
      (node (ref "R9") (pin "1") (pinfunction "1_1") (pintype "passive"))
      (node (ref "SW2") (pin "2") (pinfunction "2_2") (pintype "passive"))
      (node (ref "SW2") (pin "5") (pinfunction "5_5") (pintype "passive"))
      (node (ref "U1") (pin "100") (pinfunction "VDD3_100") (pintype "bidirectional"))
      (node (ref "U1") (pin "11") (pinfunction "VDD5_11") (pintype "bidirectional"))
      (node (ref "U1") (pin "19") (pinfunction "VDD12_19") (pintype "bidirectional"))
      (node (ref "U1") (pin "28") (pinfunction "VDD4_28") (pintype "bidirectional"))
      (node (ref "U1") (pin "50") (pinfunction "VDD1_50") (pintype "bidirectional"))
      (node (ref "U1") (pin "75") (pinfunction "VDD2_75") (pintype "bidirectional"))
      (node (ref "U4") (pin "8") (pinfunction "VCC_8") (pintype "bidirectional"))
      (node (ref "U6") (pin "2") (pinfunction "OUT_2") (pintype "bidirectional"))
      (node (ref "U6") (pin "4") (pinfunction "OUT_4") (pintype "bidirectional"))
    )
    (net (code "8") (name "A3V3") (class "Default")
      (node (ref "C35") (pin "1") (pinfunction "1_1") (pintype "passive"))
      (node (ref "C38") (pin "1") (pinfunction "1_1") (pintype "passive"))
      (node (ref "C44") (pin "1") (pinfunction "1_1") (pintype "passive"))
      (node (ref "C45") (pin "1") (pinfunction "1_1") (pintype "passive"))
      (node (ref "FB1") (pin "1") (pinfunction "1_1") (pintype "passive"))
      (node (ref "FB9") (pin "2") (pinfunction "2_2") (pintype "passive"))
      (node (ref "J3") (pin "2") (pinfunction "2_2") (pintype "bidirectional"))
      (node (ref "R38") (pin "2") (pinfunction "2_2") (pintype "passive"))
      (node (ref "R44") (pin "2") (pinfunction "2_2") (pintype "passive"))
      (node (ref "U13") (pin "5") (pinfunction "~{SHDN}_5") (pintype "bidirectional"))
      (node (ref "U13") (pin "6") (pinfunction "V+_6") (pintype "bidirectional"))
      (node (ref "U7") (pin "5") (pinfunction "~{SHDN}_5") (pintype "bidirectional"))
      (node (ref "U7") (pin "6") (pinfunction "V+_6") (pintype "bidirectional"))
      (node (ref "U8") (pin "2") (pinfunction "OUT_2") (pintype "bidirectional"))
      (node (ref "U8") (pin "4") (pinfunction "OUT_4") (pintype "bidirectional"))
    )
    (net (code "9") (name "AIN1") (class "Default")
      (node (ref "C13") (pin "1") (pinfunction "1_1") (pintype "passive"))
      (node (ref "Q17") (pin "3") (pinfunction "C_3") (pintype "passive"))
      (node (ref "R118") (pin "2") (pinfunction "2_2") (pintype "passive"))
      (node (ref "SP1") (pin "1") (pinfunction "1_1") (pintype "bidirectional"))
      (node (ref "U1") (pin "24") (pinfunction "PA1_24") (pintype "bidirectional"))
    )
    (net (code "10") (name "AIN2") (class "Default")
      (node (ref "C10") (pin "1") (pinfunction "1_1") (pintype "passive"))
      (node (ref "R42") (pin "1") (pinfunction "1_1") (pintype "passive"))
      (node (ref "SP2") (pin "1") (pinfunction "1_1") (pintype "bidirectional"))
      (node (ref "U1") (pin "25") (pinfunction "PA2_25") (pintype "bidirectional"))
    )
    (net (code "11") (name "AIN3") (class "Default")
      (node (ref "C143") (pin "1") (pinfunction "1_1") (pintype "passive"))
      (node (ref "C97") (pin "2") (pinfunction "2_2") (pintype "passive"))
      (node (ref "D10") (pin "1") (pinfunction "K_1") (pintype "passive"))
      (node (ref "R123") (pin "2") (pinfunction "2_2") (pintype "passive"))
    )
    (net (code "12") (name "ANT_SMA") (class "Default")
      (node (ref "C100") (pin "1") (pinfunction "1_1") (pintype "passive"))
      (node (ref "C101") (pin "2") (pinfunction "2_2") (pintype "passive"))
      (node (ref "R94") (pin "2") (pinfunction "2_2") (pintype "passive"))
      (node (ref "X1") (pin "1") (pinfunction "1_1") (pintype "passive"))
    )
    (net (code "13") (name "BBAMP") (class "Default")
      (node (ref "C144") (pin "1") (pinfunction "1_1") (pintype "passive"))
      (node (ref "J14") (pin "1") (pinfunction "1_1") (pintype "bidirectional"))
    )
    (net (code "14") (name "BOOT1") (class "Default")
      (node (ref "R11") (pin "2") (pinfunction "2_2") (pintype "passive"))
      (node (ref "U1") (pin "37") (pinfunction "PB2_37") (pintype "bidirectional"))
    )
    (net (code "15") (name "DAC2_OUT") (class "Default")
      (node (ref "C48") (pin "1") (pinfunction "1_1") (pintype "passive"))
      (node (ref "R13") (pin "2") (pinfunction "2_2") (pintype "passive"))
      (node (ref "R45") (pin "1") (pinfunction "1_1") (pintype "passive"))
      (node (ref "SP4") (pin "1") (pinfunction "1_1") (pintype "bidirectional"))
    )
    (net (code "16") (name "GND") (class "Default")
      (node (ref "C1") (pin "2") (pinfunction "2_2") (pintype "passive"))
      (node (ref "C10") (pin "2") (pinfunction "2_2") (pintype "passive"))
      (node (ref "C103") (pin "2") (pinfunction "2_2") (pintype "passive"))
      (node (ref "C104") (pin "2") (pinfunction "2_2") (pintype "passive"))
      (node (ref "C105") (pin "2") (pinfunction "2_2") (pintype "passive"))
      (node (ref "C106") (pin "2") (pinfunction "2_2") (pintype "passive"))
      (node (ref "C107") (pin "2") (pinfunction "2_2") (pintype "passive"))
      (node (ref "C108") (pin "2") (pinfunction "2_2") (pintype "passive"))
      (node (ref "C109") (pin "2") (pinfunction "2_2") (pintype "passive"))
      (node (ref "C11") (pin "2") (pinfunction "2_2") (pintype "passive"))
      (node (ref "C110") (pin "2") (pinfunction "2_2") (pintype "passive"))
      (node (ref "C111") (pin "2") (pinfunction "2_2") (pintype "passive"))
      (node (ref "C112") (pin "2") (pinfunction "2_2") (pintype "passive"))
      (node (ref "C113") (pin "2") (pinfunction "2_2") (pintype "passive"))
      (node (ref "C114") (pin "2") (pinfunction "2_2") (pintype "passive"))
      (node (ref "C115") (pin "2") (pinfunction "2_2") (pintype "passive"))
      (node (ref "C12") (pin "2") (pinfunction "2_2") (pintype "passive"))
      (node (ref "C120") (pin "2") (pinfunction "2_2") (pintype "passive"))
      (node (ref "C122") (pin "2") (pinfunction "2_2") (pintype "passive"))
      (node (ref "C125") (pin "1") (pinfunction "1_1") (pintype "passive"))
      (node (ref "C127") (pin "2") (pinfunction "2_2") (pintype "passive"))
      (node (ref "C129") (pin "2") (pinfunction "2_2") (pintype "passive"))
      (node (ref "C13") (pin "2") (pinfunction "2_2") (pintype "passive"))
      (node (ref "C131") (pin "1") (pinfunction "1_1") (pintype "passive"))
      (node (ref "C132") (pin "1") (pinfunction "1_1") (pintype "passive"))
      (node (ref "C133") (pin "1") (pinfunction "1_1") (pintype "passive"))
      (node (ref "C134") (pin "2") (pinfunction "2_2") (pintype "passive"))
      (node (ref "C135") (pin "1") (pinfunction "1_1") (pintype "passive"))
      (node (ref "C136") (pin "2") (pinfunction "2_2") (pintype "passive"))
      (node (ref "C137") (pin "2") (pinfunction "2_2") (pintype "passive"))
      (node (ref "C138") (pin "2") (pinfunction "2_2") (pintype "passive"))
      (node (ref "C139") (pin "2") (pinfunction "2_2") (pintype "passive"))
      (node (ref "C14") (pin "2") (pinfunction "2_2") (pintype "passive"))
      (node (ref "C140") (pin "2") (pinfunction "2_2") (pintype "passive"))
      (node (ref "C141") (pin "2") (pinfunction "2_2") (pintype "passive"))
      (node (ref "C142") (pin "2") (pinfunction "2_2") (pintype "passive"))
      (node (ref "C143") (pin "2") (pinfunction "2_2") (pintype "passive"))
      (node (ref "C15") (pin "2") (pinfunction "2_2") (pintype "passive"))
      (node (ref "C16") (pin "2") (pinfunction "2_2") (pintype "passive"))
      (node (ref "C17") (pin "2") (pinfunction "2_2") (pintype "passive"))
      (node (ref "C18") (pin "2") (pinfunction "2_2") (pintype "passive"))
      (node (ref "C19") (pin "2") (pinfunction "2_2") (pintype "passive"))
      (node (ref "C2") (pin "2") (pinfunction "2_2") (pintype "passive"))
      (node (ref "C20") (pin "2") (pinfunction "2_2") (pintype "passive"))
      (node (ref "C21") (pin "2") (pinfunction "2_2") (pintype "passive"))
      (node (ref "C22") (pin "2") (pinfunction "2_2") (pintype "passive"))
      (node (ref "C23") (pin "2") (pinfunction "2_2") (pintype "passive"))
      (node (ref "C24") (pin "2") (pinfunction "2_2") (pintype "passive"))
      (node (ref "C25") (pin "2") (pinfunction "2_2") (pintype "passive"))
      (node (ref "C26") (pin "2") (pinfunction "2_2") (pintype "passive"))
      (node (ref "C27") (pin "2") (pinfunction "2_2") (pintype "passive"))
      (node (ref "C29") (pin "2") (pinfunction "2_2") (pintype "passive"))
      (node (ref "C3") (pin "2") (pinfunction "2_2") (pintype "passive"))
      (node (ref "C30") (pin "2") (pinfunction "2_2") (pintype "passive"))
      (node (ref "C31") (pin "2") (pinfunction "-_2") (pintype "passive"))
      (node (ref "C32") (pin "2") (pinfunction "-_2") (pintype "passive"))
      (node (ref "C33") (pin "1") (pinfunction "1_1") (pintype "passive"))
      (node (ref "C34") (pin "2") (pinfunction "2_2") (pintype "passive"))
      (node (ref "C35") (pin "2") (pinfunction "2_2") (pintype "passive"))
      (node (ref "C36") (pin "2") (pinfunction "2_2") (pintype "passive"))
      (node (ref "C37") (pin "2") (pinfunction "2_2") (pintype "passive"))
      (node (ref "C38") (pin "2") (pinfunction "2_2") (pintype "passive"))
      (node (ref "C4") (pin "2") (pinfunction "2_2") (pintype "passive"))
      (node (ref "C40") (pin "2") (pinfunction "2_2") (pintype "passive"))
      (node (ref "C41") (pin "2") (pinfunction "2_2") (pintype "passive"))
      (node (ref "C42") (pin "2") (pinfunction "2_2") (pintype "passive"))
      (node (ref "C43") (pin "2") (pinfunction "2_2") (pintype "passive"))
      (node (ref "C44") (pin "2") (pinfunction "2_2") (pintype "passive"))
      (node (ref "C45") (pin "2") (pinfunction "2_2") (pintype "passive"))
      (node (ref "C46") (pin "2") (pinfunction "2_2") (pintype "passive"))
      (node (ref "C47") (pin "2") (pinfunction "2_2") (pintype "passive"))
      (node (ref "C5") (pin "2") (pinfunction "2_2") (pintype "passive"))
      (node (ref "C50") (pin "2") (pinfunction "2_2") (pintype "passive"))
      (node (ref "C52") (pin "2") (pinfunction "2_2") (pintype "passive"))
      (node (ref "C54") (pin "2") (pinfunction "2_2") (pintype "passive"))
      (node (ref "C56") (pin "2") (pinfunction "2_2") (pintype "passive"))
      (node (ref "C6") (pin "2") (pinfunction "2_2") (pintype "passive"))
      (node (ref "C61") (pin "2") (pinfunction "2_2") (pintype "passive"))
      (node (ref "C63") (pin "2") (pinfunction "2_2") (pintype "passive"))
      (node (ref "C64") (pin "2") (pinfunction "2_2") (pintype "passive"))
      (node (ref "C67") (pin "1") (pinfunction "1_1") (pintype "passive"))
      (node (ref "C7") (pin "2") (pinfunction "2_2") (pintype "passive"))
      (node (ref "C72") (pin "2") (pinfunction "2_2") (pintype "passive"))
      (node (ref "C75") (pin "2") (pinfunction "2_2") (pintype "passive"))
      (node (ref "C76") (pin "2") (pinfunction "2_2") (pintype "passive"))
      (node (ref "C77") (pin "2") (pinfunction "2_2") (pintype "passive"))
      (node (ref "C8") (pin "2") (pinfunction "2_2") (pintype "passive"))
      (node (ref "C81") (pin "2") (pinfunction "2_2") (pintype "passive"))
      (node (ref "C82") (pin "2") (pinfunction "2_2") (pintype "passive"))
      (node (ref "C83") (pin "R1") (pinfunction "R_R1") (pintype "passive"))
      (node (ref "C83") (pin "R2") (pinfunction "R_R2") (pintype "passive"))
      (node (ref "C84") (pin "2") (pinfunction "2_2") (pintype "passive"))
      (node (ref "C86") (pin "1") (pinfunction "1_1") (pintype "passive"))
      (node (ref "C88") (pin "2") (pinfunction "2_2") (pintype "passive"))
      (node (ref "C9") (pin "2") (pinfunction "2_2") (pintype "passive"))
      (node (ref "C90") (pin "2") (pinfunction "2_2") (pintype "passive"))
      (node (ref "C91") (pin "2") (pinfunction "2_2") (pintype "passive"))
      (node (ref "C92") (pin "2") (pinfunction "2_2") (pintype "passive"))
      (node (ref "C94") (pin "2") (pinfunction "2_2") (pintype "passive"))
      (node (ref "C95") (pin "2") (pinfunction "2_2") (pintype "passive"))
      (node (ref "C97") (pin "1") (pinfunction "1_1") (pintype "passive"))
      (node (ref "C98") (pin "2") (pinfunction "2_2") (pintype "passive"))
      (node (ref "C99") (pin "2") (pinfunction "2_2") (pintype "passive"))
      (node (ref "CN1") (pin "2") (pinfunction "2_2") (pintype "bidirectional"))
      (node (ref "CN2") (pin "A") (pinfunction "A_A") (pintype "bidirectional"))
      (node (ref "CN3") (pin "2") (pinfunction "2_2") (pintype "bidirectional"))
      (node (ref "CN4") (pin "5") (pinfunction "GND_5") (pintype "bidirectional"))
      (node (ref "CN4") (pin "6") (pinfunction "SHIELD1_6") (pintype "bidirectional"))
      (node (ref "CN4") (pin "7") (pinfunction "SHIELD2_7") (pintype "bidirectional"))
      (node (ref "CN4") (pin "8") (pinfunction "SHIELD3_8") (pintype "bidirectional"))
      (node (ref "CN4") (pin "9") (pinfunction "SHIELD4_9") (pintype "bidirectional"))
      (node (ref "CN5") (pin "2") (pinfunction "2_2") (pintype "bidirectional"))
      (node (ref "CN6") (pin "A") (pinfunction "A_A") (pintype "bidirectional"))
      (node (ref "CN7") (pin "A") (pinfunction "A_A") (pintype "bidirectional"))
      (node (ref "D1") (pin "A") (pinfunction "A_A") (pintype "passive"))
      (node (ref "D2") (pin "A") (pinfunction "A_A") (pintype "passive"))
      (node (ref "D3") (pin "A") (pinfunction "A_A") (pintype "passive"))
      (node (ref "D5") (pin "A") (pinfunction "A_A") (pintype "passive"))
      (node (ref "D8") (pin "C") (pinfunction "C_C") (pintype "passive"))
      (node (ref "FB6") (pin "1") (pinfunction "1_1") (pintype "passive"))
      (node (ref "J1") (pin "2") (pinfunction "2_2") (pintype "bidirectional"))
      (node (ref "J10") (pin "3") (pinfunction "3_3") (pintype "bidirectional"))
      (node (ref "J10") (pin "4") (pinfunction "4_4") (pintype "bidirectional"))
      (node (ref "J11") (pin "3") (pinfunction "3_3") (pintype "bidirectional"))
      (node (ref "J11") (pin "4") (pinfunction "4_4") (pintype "bidirectional"))
      (node (ref "J12") (pin "3") (pinfunction "3_3") (pintype "bidirectional"))
      (node (ref "J12") (pin "4") (pinfunction "4_4") (pintype "bidirectional"))
      (node (ref "J13") (pin "3") (pinfunction "3_3") (pintype "bidirectional"))
      (node (ref "J13") (pin "4") (pinfunction "4_4") (pintype "bidirectional"))
      (node (ref "J14") (pin "3") (pinfunction "3_3") (pintype "bidirectional"))
      (node (ref "J14") (pin "4") (pinfunction "4_4") (pintype "bidirectional"))
      (node (ref "J2") (pin "1") (pinfunction "1_1") (pintype "bidirectional"))
      (node (ref "J4") (pin "1") (pinfunction "1_1") (pintype "passive"))
      (node (ref "J6") (pin "4") (pinfunction "4_4") (pintype "bidirectional"))
      (node (ref "J7") (pin "3") (pinfunction "3_3") (pintype "bidirectional"))
      (node (ref "J7") (pin "4") (pinfunction "4_4") (pintype "bidirectional"))
      (node (ref "J8") (pin "3") (pinfunction "3_3") (pintype "bidirectional"))
      (node (ref "J8") (pin "4") (pinfunction "4_4") (pintype "bidirectional"))
      (node (ref "J9") (pin "3") (pinfunction "3_3") (pintype "bidirectional"))
      (node (ref "J9") (pin "4") (pinfunction "4_4") (pintype "bidirectional"))
      (node (ref "L18") (pin "P$2") (pinfunction "2_P$2") (pintype "passive"))
      (node (ref "L2") (pin "2") (pinfunction "2_2") (pintype "passive"))
      (node (ref "L3") (pin "2") (pinfunction "2_2") (pintype "passive"))
      (node (ref "L4") (pin "2") (pinfunction "2_2") (pintype "passive"))
      (node (ref "L5") (pin "2") (pinfunction "2_2") (pintype "passive"))
      (node (ref "L8") (pin "2") (pinfunction "2_2") (pintype "passive"))
      (node (ref "LED1") (pin "C") (pinfunction "C_C") (pintype "passive"))
      (node (ref "LED10") (pin "C") (pinfunction "C_C") (pintype "passive"))
      (node (ref "LED11") (pin "C") (pinfunction "C_C") (pintype "passive"))
      (node (ref "LED2") (pin "C") (pinfunction "C_C") (pintype "passive"))
      (node (ref "LED3") (pin "C") (pinfunction "C_C") (pintype "passive"))
      (node (ref "LED4") (pin "C") (pinfunction "C_C") (pintype "passive"))
      (node (ref "LED5") (pin "C") (pinfunction "C_C") (pintype "passive"))
      (node (ref "LED6") (pin "C") (pinfunction "C_C") (pintype "passive"))
      (node (ref "LED7") (pin "C") (pinfunction "C_C") (pintype "passive"))
      (node (ref "LED8") (pin "C") (pinfunction "C_C") (pintype "passive"))
      (node (ref "LED9") (pin "C") (pinfunction "C_C") (pintype "passive"))
      (node (ref "MIC1") (pin "2") (pinfunction "2_2") (pintype "bidirectional"))
      (node (ref "PAD1") (pin "P$1") (pinfunction "P$1_P$1") (pintype "bidirectional"))
      (node (ref "PAD2") (pin "P$1") (pinfunction "P$1_P$1") (pintype "bidirectional"))
      (node (ref "PAD3") (pin "P$1") (pinfunction "P$1_P$1") (pintype "bidirectional"))
      (node (ref "PAD4") (pin "P$1") (pinfunction "P$1_P$1") (pintype "bidirectional"))
      (node (ref "PAD5") (pin "P$1") (pinfunction "P$1_P$1") (pintype "bidirectional"))
      (node (ref "PAD6") (pin "P$1") (pinfunction "P$1_P$1") (pintype "bidirectional"))
      (node (ref "PAD7") (pin "P$1") (pinfunction "P$1_P$1") (pintype "bidirectional"))
      (node (ref "Q1") (pin "2") (pinfunction "E_2") (pintype "passive"))
      (node (ref "Q13") (pin "2") (pinfunction "S_2") (pintype "passive"))
      (node (ref "Q13") (pin "4") (pinfunction "S2_4") (pintype "bidirectional"))
      (node (ref "Q3") (pin "2") (pinfunction "E_2") (pintype "passive"))
      (node (ref "R101") (pin "2") (pinfunction "2_2") (pintype "passive"))
      (node (ref "R102") (pin "2") (pinfunction "2_2") (pintype "passive"))
      (node (ref "R104") (pin "1") (pinfunction "1_1") (pintype "passive"))
      (node (ref "R106") (pin "1") (pinfunction "1_1") (pintype "passive"))
      (node (ref "R107") (pin "1") (pinfunction "1_1") (pintype "passive"))
      (node (ref "R109") (pin "1") (pinfunction "1_1") (pintype "passive"))
      (node (ref "R11") (pin "1") (pinfunction "1_1") (pintype "passive"))
      (node (ref "R111") (pin "1") (pinfunction "1_1") (pintype "passive"))
      (node (ref "R113") (pin "1") (pinfunction "1_1") (pintype "passive"))
      (node (ref "R114") (pin "1") (pinfunction "1_1") (pintype "passive"))
      (node (ref "R118") (pin "1") (pinfunction "1_1") (pintype "passive"))
      (node (ref "R121") (pin "1") (pinfunction "1_1") (pintype "passive"))
      (node (ref "R17") (pin "1") (pinfunction "1_1") (pintype "passive"))
      (node (ref "R36") (pin "2") (pinfunction "2_2") (pintype "passive"))
      (node (ref "R45") (pin "2") (pinfunction "2_2") (pintype "passive"))
      (node (ref "R48") (pin "1") (pinfunction "1_1") (pintype "passive"))
      (node (ref "R52") (pin "2") (pinfunction "2_2") (pintype "passive"))
      (node (ref "R53") (pin "2") (pinfunction "2_2") (pintype "passive"))
      (node (ref "R60") (pin "1") (pinfunction "1_1") (pintype "passive"))
      (node (ref "R64") (pin "1") (pinfunction "1_1") (pintype "passive"))
      (node (ref "R66") (pin "1") (pinfunction "1_1") (pintype "passive"))
      (node (ref "R67") (pin "1") (pinfunction "1_1") (pintype "passive"))
      (node (ref "R68") (pin "1") (pinfunction "1_1") (pintype "passive"))
      (node (ref "R69") (pin "1") (pinfunction "1_1") (pintype "passive"))
      (node (ref "R70") (pin "1") (pinfunction "1_1") (pintype "passive"))
      (node (ref "R72") (pin "1") (pinfunction "1_1") (pintype "passive"))
      (node (ref "R73") (pin "1") (pinfunction "1_1") (pintype "passive"))
      (node (ref "R77") (pin "1") (pinfunction "1_1") (pintype "passive"))
      (node (ref "R82") (pin "1") (pinfunction "1_1") (pintype "passive"))
      (node (ref "R84") (pin "1") (pinfunction "1_1") (pintype "passive"))
      (node (ref "R87") (pin "1") (pinfunction "1_1") (pintype "passive"))
      (node (ref "R88") (pin "1") (pinfunction "1_1") (pintype "passive"))
      (node (ref "R93") (pin "1") (pinfunction "1_1") (pintype "passive"))
      (node (ref "R94") (pin "1") (pinfunction "1_1") (pintype "passive"))
      (node (ref "R95") (pin "1") (pinfunction "1_1") (pintype "passive"))
      (node (ref "S1") (pin "1") (pinfunction "1_1") (pintype "bidirectional"))
      (node (ref "S10") (pin "1") (pinfunction "1_1") (pintype "bidirectional"))
      (node (ref "S11") (pin "1") (pinfunction "1_1") (pintype "bidirectional"))
      (node (ref "S12") (pin "1") (pinfunction "1_1") (pintype "bidirectional"))
      (node (ref "S14") (pin "1") (pinfunction "1_1") (pintype "bidirectional"))
      (node (ref "S15") (pin "1") (pinfunction "1_1") (pintype "bidirectional"))
      (node (ref "S16") (pin "1") (pinfunction "1_1") (pintype "bidirectional"))
      (node (ref "S17") (pin "1") (pinfunction "1_1") (pintype "bidirectional"))
      (node (ref "S18") (pin "1") (pinfunction "1_1") (pintype "bidirectional"))
      (node (ref "S2") (pin "1") (pinfunction "1_1") (pintype "bidirectional"))
      (node (ref "S20") (pin "1") (pinfunction "1_1") (pintype "bidirectional"))
      (node (ref "S21") (pin "1") (pinfunction "1_1") (pintype "bidirectional"))
      (node (ref "S22") (pin "1") (pinfunction "1_1") (pintype "bidirectional"))
      (node (ref "S23") (pin "1") (pinfunction "1_1") (pintype "bidirectional"))
      (node (ref "S24") (pin "1") (pinfunction "1_1") (pintype "bidirectional"))
      (node (ref "S25") (pin "1") (pinfunction "1_1") (pintype "bidirectional"))
      (node (ref "S26") (pin "1") (pinfunction "1_1") (pintype "bidirectional"))
      (node (ref "S27") (pin "1") (pinfunction "1_1") (pintype "bidirectional"))
      (node (ref "S28") (pin "1") (pinfunction "1_1") (pintype "bidirectional"))
      (node (ref "S29") (pin "1") (pinfunction "1_1") (pintype "bidirectional"))
      (node (ref "S3") (pin "1") (pinfunction "1_1") (pintype "bidirectional"))
      (node (ref "S30") (pin "1") (pinfunction "1_1") (pintype "bidirectional"))
      (node (ref "S31") (pin "1") (pinfunction "1_1") (pintype "bidirectional"))
      (node (ref "S35") (pin "1") (pinfunction "1_1") (pintype "bidirectional"))
      (node (ref "S36") (pin "1") (pinfunction "1_1") (pintype "bidirectional"))
      (node (ref "S37") (pin "1") (pinfunction "1_1") (pintype "bidirectional"))
      (node (ref "S38") (pin "1") (pinfunction "1_1") (pintype "bidirectional"))
      (node (ref "S39") (pin "1") (pinfunction "1_1") (pintype "bidirectional"))
      (node (ref "S4") (pin "1") (pinfunction "1_1") (pintype "bidirectional"))
      (node (ref "S40") (pin "1") (pinfunction "1_1") (pintype "bidirectional"))
      (node (ref "S43") (pin "1") (pinfunction "1_1") (pintype "bidirectional"))
      (node (ref "S5") (pin "1") (pinfunction "1_1") (pintype "bidirectional"))
      (node (ref "S6") (pin "1") (pinfunction "1_1") (pintype "bidirectional"))
      (node (ref "S8") (pin "1") (pinfunction "1_1") (pintype "bidirectional"))
      (node (ref "S9") (pin "1") (pinfunction "1_1") (pintype "bidirectional"))
      (node (ref "SP1") (pin "2") (pinfunction "2_2") (pintype "bidirectional"))
      (node (ref "SP2") (pin "2") (pinfunction "2_2") (pintype "bidirectional"))
      (node (ref "SP3") (pin "2") (pinfunction "2_2") (pintype "bidirectional"))
      (node (ref "SP4") (pin "2") (pinfunction "2_2") (pintype "bidirectional"))
      (node (ref "SP5") (pin "2") (pinfunction "2_2") (pintype "bidirectional"))
      (node (ref "SP6") (pin "2") (pinfunction "2_2") (pintype "bidirectional"))
      (node (ref "SP7") (pin "2") (pinfunction "2_2") (pintype "bidirectional"))
      (node (ref "SP8") (pin "2") (pinfunction "2_2") (pintype "bidirectional"))
      (node (ref "SP9") (pin "2") (pinfunction "2_2") (pintype "bidirectional"))
      (node (ref "SW1") (pin "1") (pinfunction "1_1") (pintype "bidirectional"))
      (node (ref "SW1") (pin "2") (pinfunction "2_2") (pintype "bidirectional"))
      (node (ref "SW3") (pin "2") (pinfunction "2_2") (pintype "bidirectional"))
      (node (ref "SW3") (pin "3") (pinfunction "3_3") (pintype "bidirectional"))
      (node (ref "SW4") (pin "2") (pinfunction "2_2") (pintype "bidirectional"))
      (node (ref "SW4") (pin "3") (pinfunction "3_3") (pintype "bidirectional"))
      (node (ref "U1") (pin "10") (pinfunction "VSS5_10") (pintype "bidirectional"))
      (node (ref "U1") (pin "20") (pinfunction "VSSA_20") (pintype "bidirectional"))
      (node (ref "U1") (pin "27") (pinfunction "VSS4_27") (pintype "bidirectional"))
      (node (ref "U1") (pin "74") (pinfunction "VSS2_74") (pintype "bidirectional"))
      (node (ref "U1") (pin "99") (pinfunction "VSS_99") (pintype "bidirectional"))
      (node (ref "U10") (pin "2") (pinfunction "-IN_2") (pintype "input"))
      (node (ref "U10") (pin "4") (pinfunction "GND_4") (pintype "power_in"))
      (node (ref "U11") (pin "1") (pinfunction "G1_1") (pintype "bidirectional"))
      (node (ref "U11") (pin "4") (pinfunction "G2_4") (pintype "bidirectional"))
      (node (ref "U11") (pin "5") (pinfunction "G3_5") (pintype "bidirectional"))
      (node (ref "U12") (pin "2") (pinfunction "GND_2") (pintype "bidirectional"))
      (node (ref "U12") (pin "4") (pinfunction "GND1_4") (pintype "bidirectional"))
      (node (ref "U13") (pin "2") (pinfunction "GND_2") (pintype "bidirectional"))
      (node (ref "U14") (pin "8") (pinfunction "GND_8") (pintype "power_in"))
      (node (ref "U15") (pin "3") (pinfunction "GND_3") (pintype "power_in"))
      (node (ref "U16") (pin "3") (pinfunction "GND_3") (pintype "bidirectional"))
      (node (ref "U2") (pin "2") (pinfunction "GND_2") (pintype "bidirectional"))
      (node (ref "U3") (pin "D2") (pinfunction "GND_D2") (pintype "bidirectional"))
      (node (ref "U4") (pin "1") (pinfunction "A0_1") (pintype "bidirectional"))
      (node (ref "U4") (pin "2") (pinfunction "A1_2") (pintype "bidirectional"))
      (node (ref "U4") (pin "3") (pinfunction "A2_3") (pintype "bidirectional"))
      (node (ref "U4") (pin "4") (pinfunction "GND_4") (pintype "bidirectional"))
      (node (ref "U4") (pin "7") (pinfunction "WP_7") (pintype "bidirectional"))
      (node (ref "U5") (pin "4") (pinfunction "GND_4") (pintype "bidirectional"))
      (node (ref "U6") (pin "1") (pinfunction "GND_1") (pintype "bidirectional"))
      (node (ref "U7") (pin "2") (pinfunction "GND_2") (pintype "bidirectional"))
      (node (ref "U8") (pin "1") (pinfunction "GND_1") (pintype "bidirectional"))
      (node (ref "U9") (pin "4") (pinfunction "GND_4") (pintype "bidirectional"))
      (node (ref "U9") (pin "EP") (pinfunction "EP_EP") (pintype "bidirectional"))
      (node (ref "X1") (pin "2") (pinfunction "2_2") (pintype "passive"))
      (node (ref "X1") (pin "3") (pinfunction "2_3") (pintype "passive"))
      (node (ref "X1") (pin "4") (pinfunction "2_4") (pintype "passive"))
      (node (ref "X1") (pin "5") (pinfunction "2_5") (pintype "passive"))
      (node (ref "XTAL1") (pin "2") (pinfunction "2_2") (pintype "passive"))
      (node (ref "XTAL1") (pin "4") (pinfunction "4_4") (pintype "passive"))
      (node (ref "XTAL2") (pin "2") (pinfunction "2_2") (pintype "passive"))
      (node (ref "XTAL2") (pin "4") (pinfunction "4_4") (pintype "passive"))
      (node (ref "XTAL3") (pin "2") (pinfunction "2_2") (pintype "passive"))
      (node (ref "XTAL4") (pin "2") (pinfunction "2_2") (pintype "passive"))
    )
    (net (code "17") (name "LED-ERR") (class "Default")
      (node (ref "R4") (pin "1") (pinfunction "1_1") (pintype "passive"))
      (node (ref "U1") (pin "62") (pinfunction "PD15_62") (pintype "bidirectional"))
    )
    (net (code "18") (name "LED-PTT") (class "Default")
      (node (ref "R2") (pin "1") (pinfunction "1_1") (pintype "passive"))
      (node (ref "U1") (pin "60") (pinfunction "PD13_60") (pintype "bidirectional"))
    )
    (net (code "19") (name "LED-PWR") (class "Default")
      (node (ref "R1") (pin "1") (pinfunction "1_1") (pintype "passive"))
      (node (ref "U1") (pin "59") (pinfunction "PD12_59") (pintype "bidirectional"))
    )
    (net (code "20") (name "LED-RT") (class "Default")
      (node (ref "R3") (pin "1") (pinfunction "1_1") (pintype "passive"))
      (node (ref "U1") (pin "61") (pinfunction "PD14_61") (pintype "bidirectional"))
    )
    (net (code "21") (name "MISO") (class "Default")
      (node (ref "P8") (pin "1") (pinfunction "1_1") (pintype "bidirectional"))
      (node (ref "U1") (pin "79") (pinfunction "PC11_79") (pintype "bidirectional"))
    )
    (net (code "22") (name "MOSI") (class "Default")
      (node (ref "P9") (pin "1") (pinfunction "1_1") (pintype "bidirectional"))
      (node (ref "U1") (pin "80") (pinfunction "PC12_80") (pintype "bidirectional"))
    )
    (net (code "23") (name "N$90") (class "Default")
      (node (ref "C135") (pin "2") (pinfunction "2_2") (pintype "passive"))
      (node (ref "C144") (pin "2") (pinfunction "2_2") (pintype "passive"))
      (node (ref "L20") (pin "P$2") (pinfunction "2_P$2") (pintype "passive"))
    )
    (net (code "24") (name "N$139") (class "Default")
      (node (ref "C142") (pin "1") (pinfunction "1_1") (pintype "passive"))
      (node (ref "FB11") (pin "1") (pinfunction "1_1") (pintype "passive"))
      (node (ref "R127") (pin "1") (pinfunction "1_1") (pintype "passive"))
    )
    (net (code "25") (name "NRST") (class "Default")
      (node (ref "C4") (pin "1") (pinfunction "1_1") (pintype "passive"))
      (node (ref "R8") (pin "2") (pinfunction "2_2") (pintype "passive"))
      (node (ref "SW1") (pin "3") (pinfunction "3_3") (pintype "bidirectional"))
      (node (ref "SW1") (pin "4") (pinfunction "4_4") (pintype "bidirectional"))
      (node (ref "U1") (pin "14") (pinfunction "NRST_14") (pintype "bidirectional"))
    )
    (net (code "26") (name "NSS") (class "Default")
      (node (ref "P6") (pin "1") (pinfunction "1_1") (pintype "bidirectional"))
      (node (ref "U1") (pin "77") (pinfunction "PA15_77") (pintype "bidirectional"))
    )
    (net (code "27") (name "Net-(C19-Pad1)") (class "Default")
      (node (ref "C19") (pin "1") (pinfunction "1_1") (pintype "passive"))
      (node (ref "R15") (pin "2") (pinfunction "2_2") (pintype "passive"))
      (node (ref "XTAL1") (pin "1") (pinfunction "1_1") (pintype "passive"))
    )
    (net (code "28") (name "Net-(C20-Pad1)") (class "Default")
      (node (ref "C20") (pin "1") (pinfunction "1_1") (pintype "passive"))
      (node (ref "CN2") (pin "C") (pinfunction "C_C") (pintype "bidirectional"))
      (node (ref "D1") (pin "C") (pinfunction "C_C") (pintype "passive"))
      (node (ref "R20") (pin "2") (pinfunction "2_2") (pintype "passive"))
      (node (ref "R23") (pin "1") (pinfunction "1_1") (pintype "passive"))
    )
    (net (code "29") (name "Net-(C25-Pad1)") (class "Default")
      (node (ref "C25") (pin "1") (pinfunction "1_1") (pintype "passive"))
      (node (ref "CN5") (pin "1") (pinfunction "1_1") (pintype "bidirectional"))
      (node (ref "D3") (pin "C") (pinfunction "C_C") (pintype "passive"))
      (node (ref "FB3") (pin "1") (pinfunction "1_1") (pintype "passive"))
      (node (ref "SP9") (pin "1") (pinfunction "1_1") (pintype "bidirectional"))
    )
    (net (code "30") (name "Net-(C27-Pad1)") (class "Default")
      (node (ref "C27") (pin "1") (pinfunction "1_1") (pintype "passive"))
      (node (ref "C28") (pin "1") (pinfunction "1_1") (pintype "passive"))
      (node (ref "R31") (pin "2") (pinfunction "2_2") (pintype "passive"))
      (node (ref "R33") (pin "1") (pinfunction "1_1") (pintype "passive"))
    )
    (net (code "31") (name "Net-(C28-Pad2)") (class "Default")
      (node (ref "C28") (pin "2") (pinfunction "2_2") (pintype "passive"))
      (node (ref "R35") (pin "1") (pinfunction "1_1") (pintype "passive"))
    )
    (net (code "32") (name "Net-(C31-+)") (class "Default")
      (node (ref "C30") (pin "1") (pinfunction "1_1") (pintype "passive"))
      (node (ref "C31") (pin "1") (pinfunction "+_1") (pintype "passive"))
      (node (ref "R32") (pin "1") (pinfunction "1_1") (pintype "passive"))
      (node (ref "R33") (pin "2") (pinfunction "2_2") (pintype "passive"))
    )
    (net (code "33") (name "Net-(C32-+)") (class "Default")
      (node (ref "C32") (pin "1") (pinfunction "+_1") (pintype "passive"))
      (node (ref "C33") (pin "2") (pinfunction "2_2") (pintype "passive"))
      (node (ref "R36") (pin "1") (pinfunction "1_1") (pintype "passive"))
      (node (ref "R38") (pin "1") (pinfunction "1_1") (pintype "passive"))
      (node (ref "U7") (pin "1") (pinfunction "+IN_1") (pintype "input"))
    )
    (net (code "34") (name "Net-(C39-Pad1)") (class "Default")
      (node (ref "C39") (pin "1") (pinfunction "1_1") (pintype "passive"))
      (node (ref "R37") (pin "2") (pinfunction "2_2") (pintype "passive"))
      (node (ref "R39") (pin "2") (pinfunction "2_2") (pintype "passive"))
      (node (ref "R39") (pin "3") (pinfunction "3_3") (pintype "passive"))
    )
    (net (code "35") (name "Net-(C48-Pad2)") (class "Default")
      (node (ref "C48") (pin "2") (pinfunction "2_2") (pintype "passive"))
      (node (ref "R48") (pin "3") (pinfunction "3_3") (pintype "passive"))
    )
    (net (code "36") (name "Net-(C53-Pad2)") (class "Default")
      (node (ref "C53") (pin "2") (pinfunction "2_2") (pintype "passive"))
      (node (ref "R53") (pin "1") (pinfunction "1_1") (pintype "passive"))
    )
    (net (code "37") (name "Net-(C55-Pad2)") (class "Default")
      (node (ref "C55") (pin "2") (pinfunction "2_2") (pintype "passive"))
      (node (ref "FB5") (pin "1") (pinfunction "1_1") (pintype "passive"))
    )
    (net (code "38") (name "Net-(C57-Pad2)") (class "Default")
      (node (ref "C57") (pin "2") (pinfunction "2_2") (pintype "passive"))
      (node (ref "C58") (pin "1") (pinfunction "1_1") (pintype "passive"))
      (node (ref "J6") (pin "1") (pinfunction "1_1") (pintype "bidirectional"))
    )
    (net (code "39") (name "Net-(C58-Pad2)") (class "Default")
      (node (ref "C58") (pin "2") (pinfunction "2_2") (pintype "passive"))
      (node (ref "R62") (pin "2") (pinfunction "2_2") (pintype "passive"))
    )
    (net (code "40") (name "Net-(C59-Pad1)") (class "Default")
      (node (ref "C59") (pin "1") (pinfunction "1_1") (pintype "passive"))
      (node (ref "R63") (pin "1") (pinfunction "1_1") (pintype "passive"))
    )
    (net (code "41") (name "Net-(C60-Pad2)") (class "Default")
      (node (ref "C60") (pin "2") (pinfunction "2_2") (pintype "passive"))
      (node (ref "R68") (pin "2") (pinfunction "2_2") (pintype "passive"))
    )
    (net (code "42") (name "Net-(C62-Pad1)") (class "Default")
      (node (ref "C62") (pin "1") (pinfunction "1_1") (pintype "passive"))
      (node (ref "C64") (pin "1") (pinfunction "1_1") (pintype "passive"))
      (node (ref "C66") (pin "2") (pinfunction "2_2") (pintype "passive"))
      (node (ref "L2") (pin "1") (pinfunction "1_1") (pintype "passive"))
    )
    (net (code "43") (name "Net-(C62-Pad2)") (class "Default")
      (node (ref "C62") (pin "2") (pinfunction "2_2") (pintype "passive"))
      (node (ref "J7") (pin "2") (pinfunction "2_2") (pintype "bidirectional"))
    )
    (net (code "44") (name "Net-(C65-Pad2)") (class "Default")
      (node (ref "C65") (pin "2") (pinfunction "2_2") (pintype "passive"))
      (node (ref "R69") (pin "2") (pinfunction "2_2") (pintype "passive"))
    )
    (net (code "45") (name "Net-(C66-Pad1)") (class "Default")
      (node (ref "C66") (pin "1") (pinfunction "1_1") (pintype "passive"))
      (node (ref "C67") (pin "2") (pinfunction "2_2") (pintype "passive"))
      (node (ref "C69") (pin "2") (pinfunction "2_2") (pintype "passive"))
      (node (ref "L3") (pin "1") (pinfunction "1_1") (pintype "passive"))
    )
    (net (code "46") (name "Net-(C68-Pad1)") (class "Default")
      (node (ref "C68") (pin "1") (pinfunction "1_1") (pintype "passive"))
      (node (ref "R74") (pin "1") (pinfunction "1_1") (pintype "passive"))
    )
    (net (code "47") (name "Net-(C69-Pad1)") (class "Default")
      (node (ref "C69") (pin "1") (pinfunction "1_1") (pintype "passive"))
      (node (ref "J8") (pin "1") (pinfunction "1_1") (pintype "bidirectional"))
    )
    (net (code "48") (name "Net-(C70-Pad1)") (class "Default")
      (node (ref "C70") (pin "1") (pinfunction "1_1") (pintype "passive"))
      (node (ref "C71") (pin "2") (pinfunction "2_2") (pintype "passive"))
      (node (ref "J9") (pin "2") (pinfunction "2_2") (pintype "bidirectional"))
    )
    (net (code "49") (name "Net-(C70-Pad2)") (class "Default")
      (node (ref "C70") (pin "2") (pinfunction "2_2") (pintype "passive"))
      (node (ref "R75") (pin "2") (pinfunction "2_2") (pintype "passive"))
    )
    (net (code "50") (name "Net-(C72-Pad1)") (class "Default")
      (node (ref "C72") (pin "1") (pinfunction "1_1") (pintype "passive"))
      (node (ref "FB7") (pin "2") (pinfunction "2_2") (pintype "passive"))
      (node (ref "R78") (pin "2") (pinfunction "2_2") (pintype "passive"))
    )
    (net (code "51") (name "Net-(C73-Pad1)") (class "Default")
      (node (ref "C73") (pin "1") (pinfunction "1_1") (pintype "passive"))
      (node (ref "D6") (pin "A") (pinfunction "A_A") (pintype "passive"))
      (node (ref "FB7") (pin "1") (pinfunction "1_1") (pintype "passive"))
    )
    (net (code "52") (name "Net-(C74-Pad1)") (class "Default")
      (node (ref "C74") (pin "1") (pinfunction "1_1") (pintype "passive"))
      (node (ref "D7") (pin "A") (pinfunction "A_A") (pintype "passive"))
      (node (ref "FB8") (pin "2") (pinfunction "2_2") (pintype "passive"))
    )
    (net (code "53") (name "Net-(C74-Pad2)") (class "Default")
      (node (ref "C74") (pin "2") (pinfunction "2_2") (pintype "passive"))
      (node (ref "J10") (pin "1") (pinfunction "1_1") (pintype "bidirectional"))
    )
    (net (code "54") (name "Net-(C75-Pad1)") (class "Default")
      (node (ref "C75") (pin "1") (pinfunction "1_1") (pintype "passive"))
      (node (ref "FB8") (pin "1") (pinfunction "1_1") (pintype "passive"))
      (node (ref "R79") (pin "2") (pinfunction "2_2") (pintype "passive"))
    )
    (net (code "55") (name "Net-(C76-Pad1)") (class "Default")
      (node (ref "C76") (pin "1") (pinfunction "1_1") (pintype "passive"))
      (node (ref "C77") (pin "1") (pinfunction "1_1") (pintype "passive"))
      (node (ref "FB10") (pin "2") (pinfunction "2_2") (pintype "passive"))
      (node (ref "FB9") (pin "1") (pinfunction "1_1") (pintype "passive"))
    )
    (net (code "56") (name "Net-(C78-Pad2)") (class "Default")
      (node (ref "C78") (pin "2") (pinfunction "2_2") (pintype "passive"))
      (node (ref "J11") (pin "1") (pinfunction "1_1") (pintype "bidirectional"))
    )
    (net (code "57") (name "Net-(C79-Pad2)") (class "Default")
      (node (ref "C79") (pin "2") (pinfunction "2_2") (pintype "passive"))
      (node (ref "J10") (pin "2") (pinfunction "2_2") (pintype "bidirectional"))
      (node (ref "L4") (pin "1") (pinfunction "1_1") (pintype "passive"))
    )
    (net (code "58") (name "Net-(C80-Pad1)") (class "Default")
      (node (ref "C80") (pin "1") (pinfunction "1_1") (pintype "passive"))
      (node (ref "C82") (pin "1") (pinfunction "1_1") (pintype "passive"))
      (node (ref "C85") (pin "2") (pinfunction "2_2") (pintype "passive"))
      (node (ref "L5") (pin "1") (pinfunction "1_1") (pintype "passive"))
    )
    (net (code "59") (name "Net-(C80-Pad2)") (class "Default")
      (node (ref "C80") (pin "2") (pinfunction "2_2") (pintype "passive"))
      (node (ref "J11") (pin "2") (pinfunction "2_2") (pintype "bidirectional"))
    )
    (net (code "60") (name "Net-(C84-Pad1)") (class "Default")
      (node (ref "C84") (pin "1") (pinfunction "1_1") (pintype "passive"))
      (node (ref "L6") (pin "1") (pinfunction "1_1") (pintype "passive"))
      (node (ref "R81") (pin "2") (pinfunction "2_2") (pintype "passive"))
      (node (ref "R85") (pin "2") (pinfunction "2_2") (pintype "passive"))
    )
    (net (code "61") (name "Net-(C85-Pad1)") (class "Default")
      (node (ref "C85") (pin "1") (pinfunction "1_1") (pintype "passive"))
      (node (ref "C86") (pin "2") (pinfunction "2_2") (pintype "passive"))
      (node (ref "C89") (pin "2") (pinfunction "2_2") (pintype "passive"))
      (node (ref "L8") (pin "1") (pinfunction "1_1") (pintype "passive"))
    )
    (net (code "62") (name "Net-(C89-Pad1)") (class "Default")
      (node (ref "C89") (pin "1") (pinfunction "1_1") (pintype "passive"))
      (node (ref "C92") (pin "1") (pinfunction "1_1") (pintype "passive"))
      (node (ref "D8") (pin "A") (pinfunction "A_A") (pintype "passive"))
      (node (ref "L10") (pin "1") (pinfunction "1_1") (pintype "passive"))
    )
    (net (code "63") (name "Net-(C90-Pad1)") (class "Default")
      (node (ref "C90") (pin "1") (pinfunction "1_1") (pintype "passive"))
      (node (ref "L9") (pin "1") (pinfunction "1_1") (pintype "passive"))
      (node (ref "R85") (pin "1") (pinfunction "1_1") (pintype "passive"))
      (node (ref "R86") (pin "2") (pinfunction "2_2") (pintype "passive"))
      (node (ref "R91") (pin "2") (pinfunction "2_2") (pintype "passive"))
    )
    (net (code "64") (name "Net-(C93-Pad2)") (class "Default")
      (node (ref "C93") (pin "2") (pinfunction "2_2") (pintype "passive"))
      (node (ref "L9") (pin "2") (pinfunction "2_2") (pintype "passive"))
      (node (ref "Q12") (pin "2") (pinfunction "C_2") (pintype "passive"))
      (node (ref "Q12") (pin "4") (pinfunction "C_4") (pintype "passive"))
    )
    (net (code "65") (name "Net-(C94-Pad1)") (class "Default")
      (node (ref "C94") (pin "1") (pinfunction "1_1") (pintype "passive"))
      (node (ref "FB11") (pin "2") (pinfunction "2_2") (pintype "passive"))
      (node (ref "R89") (pin "1") (pinfunction "1_1") (pintype "passive"))
    )
    (net (code "66") (name "Net-(C96-Pad1)") (class "Default")
      (node (ref "C96") (pin "1") (pinfunction "1_1") (pintype "passive"))
      (node (ref "D9") (pin "A") (pinfunction "A_A") (pintype "passive"))
      (node (ref "L11") (pin "2") (pinfunction "2_2") (pintype "passive"))
    )
    (net (code "67") (name "Net-(C98-Pad1)") (class "Default")
      (node (ref "C98") (pin "1") (pinfunction "1_1") (pintype "passive"))
      (node (ref "FB12") (pin "1") (pinfunction "1_1") (pintype "passive"))
      (node (ref "R89") (pin "2") (pinfunction "2_2") (pintype "passive"))
    )
    (net (code "68") (name "Net-(C99-Pad1)") (class "Default")
      (node (ref "C99") (pin "1") (pinfunction "1_1") (pintype "passive"))
      (node (ref "R92") (pin "1") (pinfunction "1_1") (pintype "passive"))
    )
    (net (code "69") (name "Net-(C100-Pad2)") (class "Default")
      (node (ref "C100") (pin "2") (pinfunction "2_2") (pintype "passive"))
      (node (ref "C95") (pin "1") (pinfunction "1_1") (pintype "passive"))
      (node (ref "D9") (pin "C") (pinfunction "C_C") (pintype "passive"))
      (node (ref "L10") (pin "2") (pinfunction "2_2") (pintype "passive"))
    )
    (net (code "70") (name "Net-(C102-Pad2)") (class "Default")
      (node (ref "C102") (pin "2") (pinfunction "2_2") (pintype "passive"))
      (node (ref "C105") (pin "1") (pinfunction "1_1") (pintype "passive"))
      (node (ref "L14") (pin "1") (pinfunction "1_1") (pintype "passive"))
    )
    (net (code "71") (name "Net-(C103-Pad1)") (class "Default")
      (node (ref "C103") (pin "1") (pinfunction "1_1") (pintype "passive"))
      (node (ref "L11") (pin "1") (pinfunction "1_1") (pintype "passive"))
      (node (ref "R90") (pin "1") (pinfunction "1_1") (pintype "passive"))
      (node (ref "R95") (pin "2") (pinfunction "2_2") (pintype "passive"))
    )
    (net (code "72") (name "Net-(C104-Pad1)") (class "Default")
      (node (ref "C104") (pin "1") (pinfunction "1_1") (pintype "passive"))
      (node (ref "C106") (pin "1") (pinfunction "1_1") (pintype "passive"))
      (node (ref "L13") (pin "1") (pinfunction "1_1") (pintype "passive"))
      (node (ref "L15") (pin "1") (pinfunction "1_1") (pintype "passive"))
    )
    (net (code "73") (name "Net-(C107-Pad1)") (class "Default")
      (node (ref "C107") (pin "1") (pinfunction "1_1") (pintype "passive"))
      (node (ref "L14") (pin "2") (pinfunction "2_2") (pintype "passive"))
      (node (ref "L16") (pin "1") (pinfunction "1_1") (pintype "passive"))
    )
    (net (code "74") (name "Net-(C110-Pad1)") (class "Default")
      (node (ref "C110") (pin "1") (pinfunction "1_1") (pintype "passive"))
      (node (ref "J12") (pin "1") (pinfunction "1_1") (pintype "bidirectional"))
      (node (ref "L16") (pin "2") (pinfunction "2_2") (pintype "passive"))
    )
    (net (code "75") (name "Net-(C115-Pad1)") (class "Default")
      (node (ref "C115") (pin "1") (pinfunction "1_1") (pintype "passive"))
      (node (ref "XTAL3") (pin "1") (pinfunction "1_1") (pintype "passive"))
      (node (ref "XTAL4") (pin "1") (pinfunction "1_1") (pintype "passive"))
    )
    (net (code "76") (name "Net-(C116-Pad1)") (class "Default")
      (node (ref "C116") (pin "1") (pinfunction "1_1") (pintype "passive"))
      (node (ref "R80") (pin "2") (pinfunction "2_2") (pintype "passive"))
      (node (ref "R83") (pin "1") (pinfunction "1_1") (pintype "passive"))
    )
    (net (code "77") (name "Net-(C119-Pad2)") (class "Default")
      (node (ref "C119") (pin "2") (pinfunction "2_2") (pintype "passive"))
      (node (ref "J13") (pin "1") (pinfunction "1_1") (pintype "bidirectional"))
    )
    (net (code "78") (name "Net-(C122-Pad1)") (class "Default")
      (node (ref "C122") (pin "1") (pinfunction "1_1") (pintype "passive"))
      (node (ref "FB16") (pin "1") (pinfunction "1_1") (pintype "passive"))
      (node (ref "R108") (pin "1") (pinfunction "1_1") (pintype "passive"))
    )
    (net (code "79") (name "Net-(C123-Pad1)") (class "Default")
      (node (ref "C123") (pin "1") (pinfunction "1_1") (pintype "passive"))
      (node (ref "C124") (pin "2") (pinfunction "2_2") (pintype "passive"))
      (node (ref "J13") (pin "2") (pinfunction "2_2") (pintype "bidirectional"))
      (node (ref "R109") (pin "2") (pinfunction "2_2") (pintype "passive"))
    )
    (net (code "80") (name "Net-(C126-Pad2)") (class "Default")
      (node (ref "C126") (pin "2") (pinfunction "2_2") (pintype "passive"))
      (node (ref "R114") (pin "2") (pinfunction "2_2") (pintype "passive"))
    )
    (net (code "81") (name "Net-(C127-Pad1)") (class "Default")
      (node (ref "C127") (pin "1") (pinfunction "1_1") (pintype "passive"))
      (node (ref "R110") (pin "2") (pinfunction "2_2") (pintype "passive"))
      (node (ref "R112") (pin "2") (pinfunction "2_2") (pintype "passive"))
      (node (ref "R115") (pin "2") (pinfunction "2_2") (pintype "passive"))
    )
    (net (code "82") (name "Net-(C129-Pad1)") (class "Default")
      (node (ref "C129") (pin "1") (pinfunction "1_1") (pintype "passive"))
      (node (ref "FB18") (pin "1") (pinfunction "1_1") (pintype "passive"))
      (node (ref "R115") (pin "1") (pinfunction "1_1") (pintype "passive"))
    )
    (net (code "83") (name "Net-(C130-Pad1)") (class "Default")
      (node (ref "C130") (pin "1") (pinfunction "1_1") (pintype "passive"))
      (node (ref "R119") (pin "1") (pinfunction "1_1") (pintype "passive"))
    )
    (net (code "84") (name "Net-(C134-Pad1)") (class "Default")
      (node (ref "C134") (pin "1") (pinfunction "1_1") (pintype "passive"))
      (node (ref "FB18") (pin "2") (pinfunction "2_2") (pintype "passive"))
      (node (ref "R117") (pin "2") (pinfunction "2_2") (pintype "passive"))
      (node (ref "R119") (pin "2") (pinfunction "2_2") (pintype "passive"))
      (node (ref "R120") (pin "2") (pinfunction "2_2") (pintype "passive"))
    )
    (net (code "85") (name "Net-(C136-Pad1)") (class "Default")
      (node (ref "C136") (pin "1") (pinfunction "1_1") (pintype "passive"))
      (node (ref "FB19") (pin "1") (pinfunction "1_1") (pintype "passive"))
      (node (ref "R120") (pin "1") (pinfunction "1_1") (pintype "passive"))
    )
    (net (code "86") (name "Net-(CN1-Pad1)") (class "Default")
      (node (ref "CN1") (pin "1") (pinfunction "1_1") (pintype "bidirectional"))
      (node (ref "R5") (pin "2") (pinfunction "2_2") (pintype "passive"))
    )
    (net (code "87") (name "Net-(CN1-Pad3)") (class "Default")
      (node (ref "CN1") (pin "3") (pinfunction "3_3") (pintype "bidirectional"))
      (node (ref "R6") (pin "2") (pinfunction "2_2") (pintype "passive"))
    )
    (net (code "88") (name "Net-(CN4-DM)") (class "Default")
      (node (ref "CN4") (pin "2") (pinfunction "DM_2") (pintype "bidirectional"))
      (node (ref "R21") (pin "1") (pinfunction "1_1") (pintype "passive"))
      (node (ref "U3") (pin "D1") (pinfunction "D-IN_D1") (pintype "bidirectional"))
    )
    (net (code "89") (name "Net-(CN4-DP)") (class "Default")
      (node (ref "CN4") (pin "3") (pinfunction "DP_3") (pintype "bidirectional"))
      (node (ref "R24") (pin "1") (pinfunction "1_1") (pintype "passive"))
      (node (ref "U3") (pin "C1") (pinfunction "D+IN_C1") (pintype "bidirectional"))
    )
    (net (code "90") (name "Net-(CN4-ID)") (class "Default")
      (node (ref "CN4") (pin "4") (pinfunction "ID_4") (pintype "bidirectional"))
      (node (ref "R26") (pin "1") (pinfunction "1_1") (pintype "passive"))
      (node (ref "U3") (pin "A3") (pinfunction "ID_A3") (pintype "bidirectional"))
    )
    (net (code "91") (name "Net-(CN6-PadC)") (class "Default")
      (node (ref "CN6") (pin "C") (pinfunction "C_C") (pintype "bidirectional"))
      (node (ref "D2") (pin "C") (pinfunction "C_C") (pintype "passive"))
      (node (ref "FB2") (pin "1") (pinfunction "1_1") (pintype "passive"))
    )
    (net (code "92") (name "Net-(CN6-PadD)") (class "Default")
      (node (ref "CN6") (pin "D") (pinfunction "D_D") (pintype "bidirectional"))
      (node (ref "MIC1") (pin "1") (pinfunction "1_1") (pintype "bidirectional"))
    )
    (net (code "93") (name "Net-(CN7-PadB)") (class "Default")
      (node (ref "CN7") (pin "B") (pinfunction "B_B") (pintype "bidirectional"))
      (node (ref "J5") (pin "1") (pinfunction "1_1") (pintype "bidirectional"))
    )
    (net (code "94") (name "Net-(CN7-PadC)") (class "Default")
      (node (ref "CN7") (pin "C") (pinfunction "C_C") (pintype "bidirectional"))
      (node (ref "D5") (pin "C") (pinfunction "C_C") (pintype "passive"))
      (node (ref "FB5") (pin "2") (pinfunction "2_2") (pintype "passive"))
      (node (ref "J5") (pin "2") (pinfunction "2_2") (pintype "bidirectional"))
    )
    (net (code "95") (name "Net-(CN7-PadD)") (class "Default")
      (node (ref "CN7") (pin "D") (pinfunction "D_D") (pintype "bidirectional"))
      (node (ref "J4") (pin "2") (pinfunction "2_2") (pintype "passive"))
    )
    (net (code "96") (name "Net-(D4-K)") (class "Default")
      (node (ref "D4") (pin "C") (pinfunction "K_C") (pintype "passive"))
      (node (ref "SW5") (pin "1") (pinfunction "1_1") (pintype "passive"))
      (node (ref "SW5") (pin "4") (pinfunction "4_4") (pintype "passive"))
    )
    (net (code "97") (name "Net-(D4-PadA)") (class "Default")
      (node (ref "D4") (pin "A") (pinfunction "A_A") (pintype "passive"))
      (node (ref "FB3") (pin "2") (pinfunction "2_2") (pintype "passive"))
    )
    (net (code "98") (name "Net-(D6-PadC)") (class "Default")
      (node (ref "D6") (pin "C") (pinfunction "C_C") (pintype "passive"))
      (node (ref "D7") (pin "C") (pinfunction "C_C") (pintype "passive"))
      (node (ref "FB6") (pin "2") (pinfunction "2_2") (pintype "passive"))
      (node (ref "J8") (pin "2") (pinfunction "2_2") (pintype "bidirectional"))
    )
    (net (code "99") (name "Net-(D10-A)") (class "Default")
      (node (ref "C101") (pin "1") (pinfunction "1_1") (pintype "passive"))
      (node (ref "D10") (pin "3") (pinfunction "A_3") (pintype "passive"))
      (node (ref "R93") (pin "2") (pinfunction "2_2") (pintype "passive"))
    )
    (net (code "100") (name "Net-(FB2-Pad2)") (class "Default")
      (node (ref "FB2") (pin "2") (pinfunction "2_2") (pintype "passive"))
      (node (ref "R31") (pin "1") (pinfunction "1_1") (pintype "passive"))
    )
    (net (code "101") (name "Net-(FB17-Pad2)") (class "Default")
      (node (ref "FB17") (pin "2") (pinfunction "2_2") (pintype "passive"))
      (node (ref "R116") (pin "2") (pinfunction "2_2") (pintype "passive"))
    )
    (net (code "102") (name "Net-(J3-Pad1)") (class "Default")
      (node (ref "J3") (pin "1") (pinfunction "1_1") (pintype "bidirectional"))
      (node (ref "R32") (pin "2") (pinfunction "2_2") (pintype "passive"))
    )
    (net (code "103") (name "Net-(L12-Pad2)") (class "Default")
      (node (ref "L12") (pin "2") (pinfunction "2_2") (pintype "passive"))
      (node (ref "R91") (pin "1") (pinfunction "1_1") (pintype "passive"))
    )
    (net (code "104") (name "Net-(L17-2)") (class "Default")
      (node (ref "C112") (pin "1") (pinfunction "1_1") (pintype "passive"))
      (node (ref "L17") (pin "P$2") (pinfunction "2_P$2") (pintype "passive"))
      (node (ref "XTAL3") (pin "3") (pinfunction "3_3") (pintype "passive"))
    )
    (net (code "105") (name "Net-(L18-1)") (class "Default")
      (node (ref "C117") (pin "1") (pinfunction "1_1") (pintype "passive"))
      (node (ref "C83") (pin "S") (pinfunction "S_S") (pintype "passive"))
      (node (ref "L18") (pin "P$1") (pinfunction "1_P$1") (pintype "passive"))
      (node (ref "XTAL4") (pin "3") (pinfunction "3_3") (pintype "passive"))
    )
    (net (code "106") (name "Net-(L19-1)") (class "Default")
      (node (ref "C123") (pin "2") (pinfunction "2_2") (pintype "passive"))
      (node (ref "L19") (pin "P$1") (pinfunction "1_P$1") (pintype "passive"))
      (node (ref "U16") (pin "1") (pinfunction "IN_A_1") (pintype "bidirectional"))
    )
    (net (code "107") (name "Net-(L19-2)") (class "Default")
      (node (ref "C124") (pin "1") (pinfunction "1_1") (pintype "passive"))
      (node (ref "C125") (pin "2") (pinfunction "2_2") (pintype "passive"))
      (node (ref "L19") (pin "P$2") (pinfunction "2_P$2") (pintype "passive"))
      (node (ref "U16") (pin "2") (pinfunction "IN_B_2") (pintype "bidirectional"))
    )
    (net (code "108") (name "Net-(L20-1)") (class "Default")
      (node (ref "C132") (pin "2") (pinfunction "2_2") (pintype "passive"))
      (node (ref "L20") (pin "P$1") (pinfunction "1_P$1") (pintype "passive"))
      (node (ref "U16") (pin "4") (pinfunction "OUT_A_4") (pintype "bidirectional"))
    )
    (net (code "109") (name "Net-(LED1-PadA)") (class "Default")
      (node (ref "LED1") (pin "A") (pinfunction "A_A") (pintype "passive"))
      (node (ref "R1") (pin "2") (pinfunction "2_2") (pintype "passive"))
    )
    (net (code "110") (name "Net-(LED2-PadA)") (class "Default")
      (node (ref "LED2") (pin "A") (pinfunction "A_A") (pintype "passive"))
      (node (ref "R2") (pin "2") (pinfunction "2_2") (pintype "passive"))
    )
    (net (code "111") (name "Net-(LED3-PadA)") (class "Default")
      (node (ref "LED3") (pin "A") (pinfunction "A_A") (pintype "passive"))
      (node (ref "R3") (pin "2") (pinfunction "2_2") (pintype "passive"))
    )
    (net (code "112") (name "Net-(LED4-PadA)") (class "Default")
      (node (ref "LED4") (pin "A") (pinfunction "A_A") (pintype "passive"))
      (node (ref "R4") (pin "2") (pinfunction "2_2") (pintype "passive"))
    )
    (net (code "113") (name "Net-(LED5-PadA)") (class "Default")
      (node (ref "LED5") (pin "A") (pinfunction "A_A") (pintype "passive"))
      (node (ref "R30") (pin "1") (pinfunction "1_1") (pintype "passive"))
    )
    (net (code "114") (name "Net-(LED6-PadA)") (class "Default")
      (node (ref "LED6") (pin "A") (pinfunction "A_A") (pintype "passive"))
      (node (ref "R34") (pin "1") (pinfunction "1_1") (pintype "passive"))
    )
    (net (code "115") (name "Net-(LED7-PadA)") (class "Default")
      (node (ref "LED7") (pin "A") (pinfunction "A_A") (pintype "passive"))
      (node (ref "R40") (pin "1") (pinfunction "1_1") (pintype "passive"))
    )
    (net (code "116") (name "Net-(LED8-PadA)") (class "Default")
      (node (ref "LED8") (pin "A") (pinfunction "A_A") (pintype "passive"))
      (node (ref "R44") (pin "1") (pinfunction "1_1") (pintype "passive"))
    )
    (net (code "117") (name "Net-(LED9-PadA)") (class "Default")
      (node (ref "LED9") (pin "A") (pinfunction "A_A") (pintype "passive"))
      (node (ref "R50") (pin "1") (pinfunction "1_1") (pintype "passive"))
    )
    (net (code "118") (name "Net-(LED10-PadA)") (class "Default")
      (node (ref "LED10") (pin "A") (pinfunction "A_A") (pintype "passive"))
      (node (ref "R55") (pin "1") (pinfunction "1_1") (pintype "passive"))
    )
    (net (code "119") (name "Net-(LED11-PadA)") (class "Default")
      (node (ref "LED11") (pin "A") (pinfunction "A_A") (pintype "passive"))
      (node (ref "R57") (pin "1") (pinfunction "1_1") (pintype "passive"))
    )
    (net (code "120") (name "Net-(Q1-B)") (class "Default")
      (node (ref "Q1") (pin "1") (pinfunction "B_1") (pintype "passive"))
      (node (ref "R46") (pin "2") (pinfunction "2_2") (pintype "passive"))
    )
    (net (code "121") (name "Net-(Q1-C)") (class "Default")
      (node (ref "Q1") (pin "3") (pinfunction "C_3") (pintype "passive"))
      (node (ref "Q2") (pin "1") (pinfunction "G_1") (pintype "bidirectional"))
      (node (ref "R47") (pin "1") (pinfunction "1_1") (pintype "passive"))
    )
    (net (code "122") (name "Net-(Q3-B)") (class "Default")
      (node (ref "Q3") (pin "1") (pinfunction "B_1") (pintype "passive"))
      (node (ref "R54") (pin "2") (pinfunction "2_2") (pintype "passive"))
    )
    (net (code "123") (name "Net-(Q3-C)") (class "Default")
      (node (ref "Q3") (pin "3") (pinfunction "C_3") (pintype "passive"))
      (node (ref "Q4") (pin "1") (pinfunction "G_1") (pintype "bidirectional"))
      (node (ref "R56") (pin "1") (pinfunction "1_1") (pintype "passive"))
    )
    (net (code "124") (name "Net-(Q5-B)") (class "Default")
      (node (ref "Q5") (pin "1") (pinfunction "B_1") (pintype "passive"))
      (node (ref "Q7") (pin "2") (pinfunction "E_2") (pintype "passive"))
      (node (ref "R67") (pin "2") (pinfunction "2_2") (pintype "passive"))
    )
    (net (code "125") (name "Net-(Q5-C)") (class "Default")
      (node (ref "C63") (pin "1") (pinfunction "1_1") (pintype "passive"))
      (node (ref "Q5") (pin "3") (pinfunction "C_3") (pintype "passive"))
      (node (ref "Q7") (pin "3") (pinfunction "C_3") (pintype "passive"))
      (node (ref "R61") (pin "2") (pinfunction "2_2") (pintype "passive"))
      (node (ref "R71") (pin "1") (pinfunction "1_1") (pintype "passive"))
      (node (ref "R76") (pin "2") (pinfunction "2_2") (pintype "passive"))
    )
    (net (code "126") (name "Net-(Q5-E)") (class "Default")
      (node (ref "Q5") (pin "2") (pinfunction "E_2") (pintype "passive"))
      (node (ref "R62") (pin "1") (pinfunction "1_1") (pintype "passive"))
      (node (ref "R64") (pin "2") (pinfunction "2_2") (pintype "passive"))
    )
    (net (code "127") (name "Net-(Q6-B)") (class "Default")
      (node (ref "C57") (pin "1") (pinfunction "1_1") (pintype "passive"))
      (node (ref "C59") (pin "2") (pinfunction "2_2") (pintype "passive"))
      (node (ref "Q6") (pin "1") (pinfunction "B_1") (pintype "passive"))
      (node (ref "R59") (pin "1") (pinfunction "1_1") (pintype "passive"))
      (node (ref "R60") (pin "2") (pinfunction "2_2") (pintype "passive"))
    )
    (net (code "128") (name "Net-(Q6-C)") (class "Default")
      (node (ref "Q6") (pin "3") (pinfunction "C_3") (pintype "passive"))
      (node (ref "Q8") (pin "1") (pinfunction "B_1") (pintype "passive"))
      (node (ref "R63") (pin "2") (pinfunction "2_2") (pintype "passive"))
      (node (ref "R65") (pin "2") (pinfunction "2_2") (pintype "passive"))
    )
    (net (code "129") (name "Net-(Q6-E)") (class "Default")
      (node (ref "C60") (pin "1") (pinfunction "1_1") (pintype "passive"))
      (node (ref "Q6") (pin "2") (pinfunction "E_2") (pintype "passive"))
      (node (ref "R66") (pin "2") (pinfunction "2_2") (pintype "passive"))
    )
    (net (code "130") (name "Net-(Q7-B)") (class "Default")
      (node (ref "Q7") (pin "1") (pinfunction "B_1") (pintype "passive"))
      (node (ref "Q9") (pin "3") (pinfunction "C_3") (pintype "passive"))
      (node (ref "R71") (pin "2") (pinfunction "2_2") (pintype "passive"))
      (node (ref "R74") (pin "2") (pinfunction "2_2") (pintype "passive"))
    )
    (net (code "131") (name "Net-(Q9-B)") (class "Default")
      (node (ref "C68") (pin "2") (pinfunction "2_2") (pintype "passive"))
      (node (ref "C71") (pin "1") (pinfunction "1_1") (pintype "passive"))
      (node (ref "Q9") (pin "1") (pinfunction "B_1") (pintype "passive"))
      (node (ref "R76") (pin "1") (pinfunction "1_1") (pintype "passive"))
      (node (ref "R77") (pin "2") (pinfunction "2_2") (pintype "passive"))
    )
    (net (code "132") (name "Net-(Q9-E)") (class "Default")
      (node (ref "C65") (pin "1") (pinfunction "1_1") (pintype "passive"))
      (node (ref "Q9") (pin "2") (pinfunction "E_2") (pintype "passive"))
      (node (ref "R72") (pin "2") (pinfunction "2_2") (pintype "passive"))
    )
    (net (code "133") (name "Net-(Q10-B)") (class "Default")
      (node (ref "Q10") (pin "1") (pinfunction "B_1") (pintype "passive"))
      (node (ref "Q8") (pin "2") (pinfunction "E_2") (pintype "passive"))
      (node (ref "R70") (pin "2") (pinfunction "2_2") (pintype "passive"))
    )
    (net (code "134") (name "Net-(Q10-C)") (class "Default")
      (node (ref "C61") (pin "1") (pinfunction "1_1") (pintype "passive"))
      (node (ref "Q10") (pin "3") (pinfunction "C_3") (pintype "passive"))
      (node (ref "Q8") (pin "3") (pinfunction "C_3") (pintype "passive"))
      (node (ref "R58") (pin "1") (pinfunction "1_1") (pintype "passive"))
      (node (ref "R59") (pin "2") (pinfunction "2_2") (pintype "passive"))
      (node (ref "R65") (pin "1") (pinfunction "1_1") (pintype "passive"))
    )
    (net (code "135") (name "Net-(Q10-E)") (class "Default")
      (node (ref "Q10") (pin "2") (pinfunction "E_2") (pintype "passive"))
      (node (ref "R73") (pin "2") (pinfunction "2_2") (pintype "passive"))
      (node (ref "R75") (pin "1") (pinfunction "1_1") (pintype "passive"))
    )
    (net (code "136") (name "Net-(Q11-B)") (class "Default")
      (node (ref "C79") (pin "1") (pinfunction "1_1") (pintype "passive"))
      (node (ref "Q11") (pin "1") (pinfunction "B_1") (pintype "passive"))
      (node (ref "R81") (pin "1") (pinfunction "1_1") (pintype "passive"))
      (node (ref "R82") (pin "2") (pinfunction "2_2") (pintype "passive"))
    )
    (net (code "137") (name "Net-(Q11-C)") (class "Default")
      (node (ref "C87") (pin "2") (pinfunction "2_2") (pintype "passive"))
      (node (ref "L6") (pin "2") (pinfunction "2_2") (pintype "passive"))
      (node (ref "Q11") (pin "3") (pinfunction "C_3") (pintype "passive"))
    )
    (net (code "138") (name "Net-(Q11-E)") (class "Default")
      (node (ref "C81") (pin "1") (pinfunction "1_1") (pintype "passive"))
      (node (ref "Q11") (pin "2") (pinfunction "E_2") (pintype "passive"))
      (node (ref "R84") (pin "2") (pinfunction "2_2") (pintype "passive"))
    )
    (net (code "139") (name "Net-(Q12-B)") (class "Default")
      (node (ref "C87") (pin "1") (pinfunction "1_1") (pintype "passive"))
      (node (ref "Q12") (pin "1") (pinfunction "B_1") (pintype "passive"))
      (node (ref "R86") (pin "1") (pinfunction "1_1") (pintype "passive"))
      (node (ref "R87") (pin "2") (pinfunction "2_2") (pintype "passive"))
    )
    (net (code "140") (name "Net-(Q12-E)") (class "Default")
      (node (ref "C91") (pin "1") (pinfunction "1_1") (pintype "passive"))
      (node (ref "Q12") (pin "3") (pinfunction "E_3") (pintype "passive"))
      (node (ref "R88") (pin "2") (pinfunction "2_2") (pintype "passive"))
    )
    (net (code "141") (name "Net-(Q13-D)") (class "Default")
      (node (ref "C102") (pin "1") (pinfunction "1_1") (pintype "passive"))
      (node (ref "L13") (pin "2") (pinfunction "2_2") (pintype "passive"))
      (node (ref "Q13") (pin "3") (pinfunction "D_3") (pintype "passive"))
    )
    (net (code "142") (name "Net-(Q13-G)") (class "Default")
      (node (ref "C93") (pin "1") (pinfunction "1_1") (pintype "passive"))
      (node (ref "FB12") (pin "2") (pinfunction "2_2") (pintype "passive"))
      (node (ref "Q13") (pin "1") (pinfunction "G_1") (pintype "passive"))
      (node (ref "R92") (pin "2") (pinfunction "2_2") (pintype "passive"))
    )
    (net (code "143") (name "Net-(Q14-B)") (class "Default")
      (node (ref "C118") (pin "1") (pinfunction "1_1") (pintype "passive"))
      (node (ref "Q14") (pin "1") (pinfunction "B_1") (pintype "passive"))
      (node (ref "R103") (pin "1") (pinfunction "1_1") (pintype "passive"))
      (node (ref "R104") (pin "2") (pinfunction "2_2") (pintype "passive"))
    )
    (net (code "144") (name "Net-(Q14-C)") (class "Default")
      (node (ref "C117") (pin "2") (pinfunction "2_2") (pintype "passive"))
      (node (ref "Q14") (pin "3") (pinfunction "C_3") (pintype "passive"))
      (node (ref "Q15") (pin "1") (pinfunction "B_1") (pintype "passive"))
      (node (ref "R105") (pin "1") (pinfunction "1_1") (pintype "passive"))
    )
    (net (code "145") (name "Net-(Q14-E)") (class "Default")
      (node (ref "C121") (pin "1") (pinfunction "1_1") (pintype "passive"))
      (node (ref "Q14") (pin "2") (pinfunction "E_2") (pintype "passive"))
      (node (ref "R106") (pin "2") (pinfunction "2_2") (pintype "passive"))
    )
    (net (code "146") (name "Net-(Q15-C)") (class "Default")
      (node (ref "C120") (pin "1") (pinfunction "1_1") (pintype "passive"))
      (node (ref "Q15") (pin "3") (pinfunction "C_3") (pintype "passive"))
      (node (ref "R103") (pin "2") (pinfunction "2_2") (pintype "passive"))
      (node (ref "R105") (pin "2") (pinfunction "2_2") (pintype "passive"))
      (node (ref "R108") (pin "2") (pinfunction "2_2") (pintype "passive"))
    )
    (net (code "147") (name "Net-(Q15-E)") (class "Default")
      (node (ref "C119") (pin "1") (pinfunction "1_1") (pintype "passive"))
      (node (ref "Q15") (pin "2") (pinfunction "E_2") (pintype "passive"))
      (node (ref "R107") (pin "2") (pinfunction "2_2") (pintype "passive"))
    )
    (net (code "148") (name "Net-(Q16-B)") (class "Default")
      (node (ref "J14") (pin "2") (pinfunction "2_2") (pintype "bidirectional"))
      (node (ref "Q16") (pin "1") (pinfunction "B_1") (pintype "passive"))
      (node (ref "R110") (pin "1") (pinfunction "1_1") (pintype "passive"))
      (node (ref "R111") (pin "2") (pinfunction "2_2") (pintype "passive"))
    )
    (net (code "149") (name "Net-(Q16-C)") (class "Default")
      (node (ref "Q16") (pin "3") (pinfunction "C_3") (pintype "passive"))
      (node (ref "Q17") (pin "1") (pinfunction "B_1") (pintype "passive"))
      (node (ref "R112") (pin "1") (pinfunction "1_1") (pintype "passive"))
    )
    (net (code "150") (name "Net-(Q16-E)") (class "Default")
      (node (ref "C126") (pin "1") (pinfunction "1_1") (pintype "passive"))
      (node (ref "Q16") (pin "2") (pinfunction "E_2") (pintype "passive"))
      (node (ref "R113") (pin "2") (pinfunction "2_2") (pintype "passive"))
    )
    (net (code "151") (name "Net-(Q17-E)") (class "Default")
      (node (ref "C130") (pin "2") (pinfunction "2_2") (pintype "passive"))
      (node (ref "Q17") (pin "2") (pinfunction "E_2") (pintype "passive"))
      (node (ref "R117") (pin "1") (pinfunction "1_1") (pintype "passive"))
    )
    (net (code "152") (name "Net-(R17-Pad2)") (class "Default")
      (node (ref "R17") (pin "2") (pinfunction "2_2") (pintype "passive"))
      (node (ref "R19") (pin "2") (pinfunction "2_2") (pintype "passive"))
      (node (ref "SW2") (pin "1") (pinfunction "1_1") (pintype "passive"))
      (node (ref "SW2") (pin "4") (pinfunction "4_4") (pintype "passive"))
    )
    (net (code "153") (name "Net-(R41-Pad1)") (class "Default")
      (node (ref "R41") (pin "1") (pinfunction "1_1") (pintype "passive"))
      (node (ref "SW5") (pin "2") (pinfunction "2_2") (pintype "passive"))
      (node (ref "SW5") (pin "3") (pinfunction "3_3") (pintype "passive"))
      (node (ref "SW5") (pin "5") (pinfunction "5_5") (pintype "passive"))
      (node (ref "SW5") (pin "6") (pinfunction "6_6") (pintype "passive"))
    )
    (net (code "154") (name "Net-(U1A-PA5)") (class "Default")
      (node (ref "R13") (pin "1") (pinfunction "1_1") (pintype "passive"))
      (node (ref "U1") (pin "30") (pinfunction "PA5_30") (pintype "bidirectional"))
    )
    (net (code "155") (name "Net-(U1B-VCAP1)") (class "Default")
      (node (ref "C18") (pin "1") (pinfunction "1_1") (pintype "passive"))
      (node (ref "U1") (pin "49") (pinfunction "VCAP1_49") (pintype "bidirectional"))
    )
    (net (code "156") (name "Net-(U1B-VCAP2)") (class "Default")
      (node (ref "C17") (pin "1") (pinfunction "1_1") (pintype "passive"))
      (node (ref "U1") (pin "73") (pinfunction "VCAP2_73") (pintype "bidirectional"))
    )
    (net (code "157") (name "Net-(U2-~{EN})") (class "Default")
      (node (ref "R16") (pin "2") (pinfunction "2_2") (pintype "passive"))
      (node (ref "R18") (pin "1") (pinfunction "1_1") (pintype "passive"))
      (node (ref "U2") (pin "4") (pinfunction "~{EN}_4") (pintype "bidirectional"))
    )
    (net (code "158") (name "Net-(U6-IN)") (class "Default")
      (node (ref "C137") (pin "1") (pinfunction "1_1") (pintype "passive"))
      (node (ref "C26") (pin "1") (pinfunction "1_1") (pintype "passive"))
      (node (ref "FB20") (pin "2") (pinfunction "2_2") (pintype "passive"))
      (node (ref "U6") (pin "3") (pinfunction "IN_3") (pintype "bidirectional"))
    )
    (net (code "159") (name "Net-(U7--IN)") (class "Default")
      (node (ref "R35") (pin "2") (pinfunction "2_2") (pintype "passive"))
      (node (ref "R37") (pin "1") (pinfunction "1_1") (pintype "passive"))
      (node (ref "U7") (pin "3") (pinfunction "-IN_3") (pintype "input"))
    )
    (net (code "160") (name "Net-(U7-OUT)") (class "Default")
      (node (ref "C39") (pin "2") (pinfunction "2_2") (pintype "passive"))
      (node (ref "R39") (pin "1") (pinfunction "1_1") (pintype "passive"))
      (node (ref "R42") (pin "2") (pinfunction "2_2") (pintype "passive"))
      (node (ref "U7") (pin "4") (pinfunction "OUT_4") (pintype "output"))
    )
    (net (code "161") (name "Net-(U8-IN)") (class "Default")
      (node (ref "C138") (pin "1") (pinfunction "1_1") (pintype "passive"))
      (node (ref "C36") (pin "1") (pinfunction "1_1") (pintype "passive"))
      (node (ref "FB4") (pin "2") (pinfunction "2_2") (pintype "passive"))
      (node (ref "U8") (pin "3") (pinfunction "IN_3") (pintype "bidirectional"))
    )
    (net (code "162") (name "Net-(U9-EN)") (class "Default")
      (node (ref "R43") (pin "2") (pinfunction "2_2") (pintype "passive"))
      (node (ref "U9") (pin "7") (pinfunction "EN_7") (pintype "bidirectional"))
    )
    (net (code "163") (name "Net-(U9-SS)") (class "Default")
      (node (ref "C47") (pin "1") (pinfunction "1_1") (pintype "passive"))
      (node (ref "U9") (pin "8") (pinfunction "SS_8") (pintype "bidirectional"))
    )
    (net (code "164") (name "Net-(U9-SW)") (class "Default")
      (node (ref "C49") (pin "2") (pinfunction "2_2") (pintype "passive"))
      (node (ref "L1") (pin "1") (pinfunction "1_1") (pintype "passive"))
      (node (ref "U9") (pin "3") (pinfunction "SW_3") (pintype "bidirectional"))
    )
    (net (code "165") (name "Net-(U9-VBST)") (class "Default")
      (node (ref "C49") (pin "1") (pinfunction "1_1") (pintype "passive"))
      (node (ref "U9") (pin "1") (pinfunction "VBST_1") (pintype "bidirectional"))
    )
    (net (code "166") (name "Net-(U9-VFB)") (class "Default")
      (node (ref "C51") (pin "2") (pinfunction "2_2") (pintype "passive"))
      (node (ref "R51") (pin "2") (pinfunction "2_2") (pintype "passive"))
      (node (ref "R52") (pin "1") (pinfunction "1_1") (pintype "passive"))
      (node (ref "U9") (pin "5") (pinfunction "VFB_5") (pintype "bidirectional"))
    )
    (net (code "167") (name "Net-(U9-VREG5)") (class "Default")
      (node (ref "C46") (pin "1") (pinfunction "1_1") (pintype "passive"))
      (node (ref "U9") (pin "6") (pinfunction "VREG5_6") (pintype "bidirectional"))
    )
    (net (code "168") (name "Net-(U10-+IN)") (class "Default")
      (node (ref "C50") (pin "1") (pinfunction "1_1") (pintype "passive"))
      (node (ref "R48") (pin "2") (pinfunction "2_2") (pintype "passive"))
      (node (ref "U10") (pin "3") (pinfunction "+IN_3") (pintype "input"))
    )
    (net (code "169") (name "Net-(U10-OUT)") (class "Default")
      (node (ref "C53") (pin "1") (pinfunction "1_1") (pintype "passive"))
      (node (ref "C55") (pin "1") (pinfunction "1_1") (pintype "passive"))
      (node (ref "U10") (pin "5") (pinfunction "OUT_5") (pintype "output"))
    )
    (net (code "170") (name "Net-(U10-VS)") (class "Default")
      (node (ref "C52") (pin "1") (pinfunction "1_1") (pintype "passive"))
      (node (ref "R49") (pin "2") (pinfunction "2_2") (pintype "passive"))
      (node (ref "U10") (pin "6") (pinfunction "VS_6") (pintype "passive"))
    )
    (net (code "171") (name "Net-(U11-IF)") (class "Default")
      (node (ref "J6") (pin "2") (pinfunction "2_2") (pintype "bidirectional"))
      (node (ref "U11") (pin "2") (pinfunction "IF_2") (pintype "bidirectional"))
    )
    (net (code "172") (name "Net-(U11-RF)") (class "Default")
      (node (ref "J7") (pin "1") (pinfunction "1_1") (pintype "bidirectional"))
      (node (ref "U11") (pin "3") (pinfunction "RF_3") (pintype "bidirectional"))
    )
    (net (code "173") (name "Net-(U12-1N)") (class "Default")
      (node (ref "C78") (pin "1") (pinfunction "1_1") (pintype "passive"))
      (node (ref "U12") (pin "1") (pinfunction "1N_1") (pintype "bidirectional"))
    )
    (net (code "174") (name "Net-(U12-OUT)") (class "Default")
      (node (ref "C73") (pin "2") (pinfunction "2_2") (pintype "passive"))
      (node (ref "FB10") (pin "1") (pinfunction "1_1") (pintype "passive"))
      (node (ref "U12") (pin "3") (pinfunction "OUT_3") (pintype "bidirectional"))
    )
    (net (code "175") (name "Net-(U13-+IN)") (class "Default")
      (node (ref "C88") (pin "1") (pinfunction "1_1") (pintype "passive"))
      (node (ref "R83") (pin "2") (pinfunction "2_2") (pintype "passive"))
      (node (ref "U13") (pin "1") (pinfunction "+IN_1") (pintype "input"))
    )
    (net (code "176") (name "Net-(U13--IN)") (class "Default")
      (node (ref "R121") (pin "2") (pinfunction "2_2") (pintype "passive"))
      (node (ref "R122") (pin "1") (pinfunction "1_1") (pintype "passive"))
      (node (ref "U13") (pin "3") (pinfunction "-IN_3") (pintype "input"))
    )
    (net (code "177") (name "Net-(U14-CLK0)") (class "Default")
      (node (ref "R100") (pin "2") (pinfunction "2_2") (pintype "passive"))
      (node (ref "R99") (pin "2") (pinfunction "2_2") (pintype "passive"))
      (node (ref "U14") (pin "10") (pinfunction "CLK0_10") (pintype "output"))
    )
    (net (code "178") (name "Net-(U14-CLK1)") (class "Default")
      (node (ref "R96") (pin "2") (pinfunction "2_2") (pintype "passive"))
      (node (ref "U14") (pin "9") (pinfunction "CLK1_9") (pintype "output"))
    )
    (net (code "179") (name "Net-(U14-CLK2)") (class "Default")
      (node (ref "R97") (pin "2") (pinfunction "2_2") (pintype "passive"))
      (node (ref "U14") (pin "6") (pinfunction "CLK2_6") (pintype "output"))
    )
    (net (code "180") (name "Net-(U14-VDD)") (class "Default")
      (node (ref "C114") (pin "1") (pinfunction "1_1") (pintype "passive"))
      (node (ref "FB15") (pin "2") (pinfunction "2_2") (pintype "passive"))
      (node (ref "U14") (pin "1") (pinfunction "VDD_1") (pintype "power_in"))
    )
    (net (code "181") (name "Net-(U14-VDDO)") (class "Default")
      (node (ref "C113") (pin "1") (pinfunction "1_1") (pintype "passive"))
      (node (ref "FB14") (pin "2") (pinfunction "2_2") (pintype "passive"))
      (node (ref "U14") (pin "7") (pinfunction "VDDO_7") (pintype "power_in"))
    )
    (net (code "182") (name "Net-(U14-XA)") (class "Default")
      (node (ref "U14") (pin "2") (pinfunction "XA_2") (pintype "bidirectional"))
      (node (ref "XTAL2") (pin "1") (pinfunction "1_1") (pintype "passive"))
    )
    (net (code "183") (name "Net-(U14-XB)") (class "Default")
      (node (ref "U14") (pin "3") (pinfunction "XB_3") (pintype "bidirectional"))
      (node (ref "XTAL2") (pin "3") (pinfunction "3_3") (pintype "passive"))
    )
    (net (code "184") (name "Net-(U15-CLK+)") (class "Default")
      (node (ref "R98") (pin "2") (pinfunction "2_2") (pintype "passive"))
      (node (ref "U15") (pin "4") (pinfunction "CLK+_4") (pintype "output"))
    )
    (net (code "185") (name "Net-(U15-OE)") (class "Default")
      (node (ref "C111") (pin "1") (pinfunction "1_1") (pintype "passive"))
      (node (ref "FB13") (pin "2") (pinfunction "2_2") (pintype "passive"))
      (node (ref "U15") (pin "2") (pinfunction "OE_2") (pintype "input"))
      (node (ref "U15") (pin "6") (pinfunction "VDD_6") (pintype "power_in"))
    )
    (net (code "186") (name "Net-(U16-OSC_B)") (class "Default")
      (node (ref "C128") (pin "2") (pinfunction "2_2") (pintype "passive"))
      (node (ref "U16") (pin "6") (pinfunction "OSC_B_6") (pintype "bidirectional"))
    )
    (net (code "187") (name "Net-(U16-VIN)") (class "Default")
      (node (ref "C131") (pin "2") (pinfunction "2_2") (pintype "passive"))
      (node (ref "C133") (pin "2") (pinfunction "2_2") (pintype "passive"))
      (node (ref "R116") (pin "1") (pinfunction "1_1") (pintype "passive"))
      (node (ref "U16") (pin "8") (pinfunction "VIN_8") (pintype "bidirectional"))
    )
    (net (code "188") (name "OSC_IN") (class "Default")
      (node (ref "C21") (pin "1") (pinfunction "1_1") (pintype "passive"))
      (node (ref "U1") (pin "12") (pinfunction "PH0_12") (pintype "bidirectional"))
      (node (ref "XTAL1") (pin "3") (pinfunction "3_3") (pintype "passive"))
    )
    (net (code "189") (name "OSC_OUT") (class "Default")
      (node (ref "R15") (pin "1") (pinfunction "1_1") (pintype "passive"))
      (node (ref "U1") (pin "13") (pinfunction "PH1_13") (pintype "bidirectional"))
    )
    (net (code "190") (name "OTG_DM") (class "Default")
      (node (ref "R21") (pin "2") (pinfunction "2_2") (pintype "passive"))
      (node (ref "U1") (pin "70") (pinfunction "PA11_70") (pintype "bidirectional"))
      (node (ref "U3") (pin "D3") (pinfunction "D-OUT_D3") (pintype "bidirectional"))
    )
    (net (code "191") (name "OTG_DP") (class "Default")
      (node (ref "R24") (pin "2") (pinfunction "2_2") (pintype "passive"))
      (node (ref "U1") (pin "71") (pinfunction "PA12_71") (pintype "bidirectional"))
      (node (ref "U3") (pin "C3") (pinfunction "D+OUT_C3") (pintype "bidirectional"))
    )
    (net (code "192") (name "OTG_ID") (class "Default")
      (node (ref "R26") (pin "2") (pinfunction "2_2") (pintype "passive"))
      (node (ref "U1") (pin "69") (pinfunction "PA10_69") (pintype "bidirectional"))
    )
    (net (code "193") (name "OTG_OVR_CUR") (class "Default")
      (node (ref "R25") (pin "2") (pinfunction "2_2") (pintype "passive"))
      (node (ref "U1") (pin "86") (pinfunction "PD5_86") (pintype "bidirectional"))
      (node (ref "U2") (pin "3") (pinfunction "~{FAULT}_3") (pintype "bidirectional"))
    )
    (net (code "194") (name "OTG_PWR_ON") (class "Default")
      (node (ref "R16") (pin "1") (pinfunction "1_1") (pintype "passive"))
      (node (ref "U1") (pin "15") (pinfunction "PC0_15") (pintype "bidirectional"))
    )
    (net (code "195") (name "PA_OUTPUT") (class "Default")
      (node (ref "C96") (pin "2") (pinfunction "2_2") (pintype "passive"))
      (node (ref "J12") (pin "2") (pinfunction "2_2") (pintype "bidirectional"))
    )
    (net (code "196") (name "PE0") (class "Default")
      (node (ref "J2") (pin "2") (pinfunction "2_2") (pintype "bidirectional"))
      (node (ref "U1") (pin "97") (pinfunction "PE0_97") (pintype "bidirectional"))
    )
    (net (code "197") (name "PE1") (class "Default")
      (node (ref "J2") (pin "3") (pinfunction "3_3") (pintype "bidirectional"))
      (node (ref "U1") (pin "98") (pinfunction "PE1_98") (pintype "bidirectional"))
    )
    (net (code "198") (name "PE2") (class "Default")
      (node (ref "J2") (pin "4") (pinfunction "4_4") (pintype "bidirectional"))
      (node (ref "U1") (pin "1") (pinfunction "PE2_1") (pintype "bidirectional"))
    )
    (net (code "199") (name "PE3") (class "Default")
      (node (ref "J2") (pin "5") (pinfunction "5_5") (pintype "bidirectional"))
      (node (ref "U1") (pin "2") (pinfunction "PE3_2") (pintype "bidirectional"))
    )
    (net (code "200") (name "RX+12V") (class "Default")
      (node (ref "Q2") (pin "3") (pinfunction "D_3") (pintype "bidirectional"))
      (node (ref "R50") (pin "2") (pinfunction "2_2") (pintype "passive"))
      (node (ref "R58") (pin "2") (pinfunction "2_2") (pintype "passive"))
      (node (ref "R78") (pin "1") (pinfunction "1_1") (pintype "passive"))
    )
    (net (code "201") (name "RX-2ND-LO") (class "Default")
      (node (ref "C128") (pin "1") (pinfunction "1_1") (pintype "passive"))
      (node (ref "R100") (pin "1") (pinfunction "1_1") (pintype "passive"))
      (node (ref "R102") (pin "1") (pinfunction "1_1") (pintype "passive"))
      (node (ref "SP8") (pin "1") (pinfunction "1_1") (pintype "bidirectional"))
    )
    (net (code "202") (name "SCK") (class "Default")
      (node (ref "P7") (pin "1") (pinfunction "1_1") (pintype "bidirectional"))
      (node (ref "U1") (pin "78") (pinfunction "PC10_78") (pintype "bidirectional"))
    )
    (net (code "203") (name "SCL3") (class "Default")
      (node (ref "C139") (pin "1") (pinfunction "1_1") (pintype "passive"))
      (node (ref "R124") (pin "2") (pinfunction "2_2") (pintype "passive"))
      (node (ref "U14") (pin "4") (pinfunction "SCL_4") (pintype "bidirectional"))
      (node (ref "U15") (pin "8") (pinfunction "SCL_8") (pintype "bidirectional"))
    )
    (net (code "204") (name "SDA3") (class "Default")
      (node (ref "C140") (pin "1") (pinfunction "1_1") (pintype "passive"))
      (node (ref "R125") (pin "2") (pinfunction "2_2") (pintype "passive"))
      (node (ref "U14") (pin "5") (pinfunction "SDA_5") (pintype "bidirectional"))
      (node (ref "U15") (pin "7") (pinfunction "SDA_7") (pintype "bidirectional"))
    )
    (net (code "205") (name "SWCLK") (class "Default")
      (node (ref "R5") (pin "1") (pinfunction "1_1") (pintype "passive"))
      (node (ref "U1") (pin "76") (pinfunction "PA14_76") (pintype "bidirectional"))
    )
    (net (code "206") (name "SWDIO") (class "Default")
      (node (ref "R6") (pin "1") (pinfunction "1_1") (pintype "passive"))
      (node (ref "U1") (pin "72") (pinfunction "PA13_72") (pintype "bidirectional"))
    )
    (net (code "207") (name "TIAOUT") (class "Default")
      (node (ref "J9") (pin "1") (pinfunction "1_1") (pintype "bidirectional"))
      (node (ref "L17") (pin "P$1") (pinfunction "1_P$1") (pintype "passive"))
    )
    (net (code "208") (name "TX+12V") (class "Default")
      (node (ref "L12") (pin "1") (pinfunction "1_1") (pintype "passive"))
      (node (ref "Q4") (pin "3") (pinfunction "D_3") (pintype "bidirectional"))
      (node (ref "R57") (pin "2") (pinfunction "2_2") (pintype "passive"))
      (node (ref "R61") (pin "1") (pinfunction "1_1") (pintype "passive"))
      (node (ref "R79") (pin "1") (pinfunction "1_1") (pintype "passive"))
      (node (ref "R90") (pin "2") (pinfunction "2_2") (pintype "passive"))
    )
    (net (code "209") (name "TX-2ND-LO") (class "Default")
      (node (ref "C121") (pin "2") (pinfunction "2_2") (pintype "passive"))
      (node (ref "R101") (pin "1") (pinfunction "1_1") (pintype "passive"))
      (node (ref "R99") (pin "1") (pinfunction "1_1") (pintype "passive"))
      (node (ref "SP7") (pin "1") (pinfunction "1_1") (pintype "bidirectional"))
    )
    (net (code "210") (name "TX_DAC") (class "Default")
      (node (ref "C118") (pin "2") (pinfunction "2_2") (pintype "passive"))
      (node (ref "C141") (pin "1") (pinfunction "1_1") (pintype "passive"))
      (node (ref "R126") (pin "2") (pinfunction "2_2") (pintype "passive"))
      (node (ref "SP3") (pin "1") (pinfunction "1_1") (pintype "bidirectional"))
    )
    (net (code "211") (name "USART3_RX") (class "Default")
      (node (ref "CN3") (pin "3") (pinfunction "3_3") (pintype "bidirectional"))
      (node (ref "R9") (pin "2") (pinfunction "2_2") (pintype "passive"))
      (node (ref "U1") (pin "48") (pinfunction "PB11_48") (pintype "bidirectional"))
    )
    (net (code "212") (name "USART3_TX") (class "Default")
      (node (ref "CN3") (pin "1") (pinfunction "1_1") (pintype "bidirectional"))
      (node (ref "R10") (pin "2") (pinfunction "2_2") (pintype "passive"))
      (node (ref "U1") (pin "47") (pinfunction "PB10_47") (pintype "bidirectional"))
    )
    (net (code "213") (name "VBAT") (class "Default")
      (node (ref "C16") (pin "1") (pinfunction "1_1") (pintype "passive"))
      (node (ref "R14") (pin "2") (pinfunction "2_2") (pintype "passive"))
      (node (ref "U1") (pin "6") (pinfunction "VBAT_6") (pintype "bidirectional"))
    )
    (net (code "214") (name "VBUS") (class "Default")
      (node (ref "C22") (pin "1") (pinfunction "1_1") (pintype "passive"))
      (node (ref "CN4") (pin "1") (pinfunction "VBUS_1") (pintype "bidirectional"))
      (node (ref "U1") (pin "68") (pinfunction "PA9_68") (pintype "bidirectional"))
      (node (ref "U2") (pin "1") (pinfunction "OUT_1") (pintype "bidirectional"))
      (node (ref "U3") (pin "B3") (pinfunction "VBUS_B3") (pintype "bidirectional"))
    )
    (net (code "215") (name "VDDA") (class "Default")
      (node (ref "C12") (pin "1") (pinfunction "1_1") (pintype "passive"))
      (node (ref "C7") (pin "1") (pinfunction "1_1") (pintype "passive"))
      (node (ref "FB1") (pin "2") (pinfunction "2_2") (pintype "passive"))
      (node (ref "R12") (pin "1") (pinfunction "1_1") (pintype "passive"))
      (node (ref "U1") (pin "22") (pinfunction "VDDA_22") (pintype "bidirectional"))
    )
    (net (code "216") (name "VGG") (class "Default")
      (node (ref "C116") (pin "2") (pinfunction "2_2") (pintype "passive"))
      (node (ref "R122") (pin "2") (pinfunction "2_2") (pintype "passive"))
      (node (ref "R127") (pin "2") (pinfunction "2_2") (pintype "passive"))
      (node (ref "SP5") (pin "1") (pinfunction "1_1") (pintype "bidirectional"))
      (node (ref "U13") (pin "4") (pinfunction "OUT_4") (pintype "output"))
    )
    (net (code "217") (name "VGG_DAC") (class "Default")
      (node (ref "R80") (pin "1") (pinfunction "1_1") (pintype "passive"))
      (node (ref "U1") (pin "54") (pinfunction "PB15_54") (pintype "bidirectional"))
    )
    (net (code "218") (name "VREF+") (class "Default")
      (node (ref "C11") (pin "1") (pinfunction "1_1") (pintype "passive"))
      (node (ref "C6") (pin "1") (pinfunction "1_1") (pintype "passive"))
      (node (ref "R12") (pin "2") (pinfunction "2_2") (pintype "passive"))
      (node (ref "U1") (pin "21") (pinfunction "VREF+_21") (pintype "bidirectional"))
    )
    (net (code "219") (name "XAIN3") (class "Default")
      (node (ref "R123") (pin "1") (pinfunction "1_1") (pintype "passive"))
      (node (ref "U1") (pin "26") (pinfunction "PA3_26") (pintype "bidirectional"))
    )
    (net (code "220") (name "XSCL3") (class "Default")
      (node (ref "R124") (pin "1") (pinfunction "1_1") (pintype "passive"))
      (node (ref "R29") (pin "2") (pinfunction "2_2") (pintype "passive"))
      (node (ref "U1") (pin "67") (pinfunction "PA8_67") (pintype "bidirectional"))
      (node (ref "U4") (pin "6") (pinfunction "SCL_6") (pintype "bidirectional"))
    )
    (net (code "221") (name "XSDA3") (class "Default")
      (node (ref "R125") (pin "1") (pinfunction "1_1") (pintype "passive"))
      (node (ref "R28") (pin "2") (pinfunction "2_2") (pintype "passive"))
      (node (ref "U1") (pin "66") (pinfunction "PC9_66") (pintype "bidirectional"))
      (node (ref "U4") (pin "5") (pinfunction "SDA_5") (pintype "bidirectional"))
    )
    (net (code "222") (name "XTX_DAC") (class "Default")
      (node (ref "R126") (pin "1") (pinfunction "1_1") (pintype "passive"))
      (node (ref "U1") (pin "29") (pinfunction "PA4_29") (pintype "bidirectional"))
    )
    (net (code "223") (name "unconnected-(CN2-E-PadF)") (class "Default")
      (node (ref "CN2") (pin "F") (pinfunction "E_F") (pintype "bidirectional"))
    )
    (net (code "224") (name "unconnected-(CN2-PadB)") (class "Default")
      (node (ref "CN2") (pin "B") (pinfunction "B_B") (pintype "bidirectional"))
    )
    (net (code "225") (name "unconnected-(CN2-PadD)") (class "Default")
      (node (ref "CN2") (pin "D") (pinfunction "D_D") (pintype "bidirectional"))
    )
    (net (code "226") (name "unconnected-(CN5-Pad3)") (class "Default")
      (node (ref "CN5") (pin "3") (pinfunction "3_3") (pintype "bidirectional"))
    )
    (net (code "227") (name "unconnected-(CN6-E-PadF)") (class "Default")
      (node (ref "CN6") (pin "F") (pinfunction "E_F") (pintype "bidirectional"))
    )
    (net (code "228") (name "unconnected-(CN6-PadB)") (class "Default")
      (node (ref "CN6") (pin "B") (pinfunction "B_B") (pintype "bidirectional"))
    )
    (net (code "229") (name "unconnected-(CN7-E-PadF)") (class "Default")
      (node (ref "CN7") (pin "F") (pinfunction "E_F") (pintype "bidirectional"))
    )
    (net (code "230") (name "unconnected-(J6-Pad3)") (class "Default")
      (node (ref "J6") (pin "3") (pinfunction "3_3") (pintype "bidirectional"))
    )
    (net (code "231") (name "unconnected-(SW2-Pad3)") (class "Default")
      (node (ref "SW2") (pin "3") (pinfunction "3_3") (pintype "passive"))
    )
    (net (code "232") (name "unconnected-(SW2-Pad6)") (class "Default")
      (node (ref "SW2") (pin "6") (pinfunction "6_6") (pintype "passive"))
    )
    (net (code "233") (name "unconnected-(SW2-Pad7)") (class "Default")
      (node (ref "SW2") (pin "7") (pinfunction "7_7") (pintype "bidirectional"))
    )
    (net (code "234") (name "unconnected-(SW2-Pad8)") (class "Default")
      (node (ref "SW2") (pin "8") (pinfunction "8_8") (pintype "bidirectional"))
    )
    (net (code "235") (name "unconnected-(SW5-Pad7)") (class "Default")
      (node (ref "SW5") (pin "7") (pinfunction "7_7") (pintype "bidirectional"))
    )
    (net (code "236") (name "unconnected-(SW5-Pad8)") (class "Default")
      (node (ref "SW5") (pin "8") (pinfunction "8_8") (pintype "bidirectional"))
    )
    (net (code "237") (name "unconnected-(U1A-PA0-Pad23)") (class "Default")
      (node (ref "U1") (pin "23") (pinfunction "PA0_23") (pintype "bidirectional"))
    )
    (net (code "238") (name "unconnected-(U1A-PA6-Pad31)") (class "Default")
      (node (ref "U1") (pin "31") (pinfunction "PA6_31") (pintype "bidirectional"))
    )
    (net (code "239") (name "unconnected-(U1A-PA7-Pad32)") (class "Default")
      (node (ref "U1") (pin "32") (pinfunction "PA7_32") (pintype "bidirectional"))
    )
    (net (code "240") (name "unconnected-(U1A-PB0-Pad35)") (class "Default")
      (node (ref "U1") (pin "35") (pinfunction "PB0_35") (pintype "bidirectional"))
    )
    (net (code "241") (name "unconnected-(U1A-PB1-Pad36)") (class "Default")
      (node (ref "U1") (pin "36") (pinfunction "PB1_36") (pintype "bidirectional"))
    )
    (net (code "242") (name "unconnected-(U1A-PB3-Pad89)") (class "Default")
      (node (ref "U1") (pin "89") (pinfunction "PB3_89") (pintype "bidirectional"))
    )
    (net (code "243") (name "unconnected-(U1A-PB4-Pad90)") (class "Default")
      (node (ref "U1") (pin "90") (pinfunction "PB4_90") (pintype "bidirectional"))
    )
    (net (code "244") (name "unconnected-(U1A-PB5-Pad91)") (class "Default")
      (node (ref "U1") (pin "91") (pinfunction "PB5_91") (pintype "bidirectional"))
    )
    (net (code "245") (name "unconnected-(U1A-PB6-Pad92)") (class "Default")
      (node (ref "U1") (pin "92") (pinfunction "PB6_92") (pintype "bidirectional"))
    )
    (net (code "246") (name "unconnected-(U1A-PB7-Pad93)") (class "Default")
      (node (ref "U1") (pin "93") (pinfunction "PB7_93") (pintype "bidirectional"))
    )
    (net (code "247") (name "unconnected-(U1A-PB8-Pad95)") (class "Default")
      (node (ref "U1") (pin "95") (pinfunction "PB8_95") (pintype "bidirectional"))
    )
    (net (code "248") (name "unconnected-(U1A-PB9-Pad96)") (class "Default")
      (node (ref "U1") (pin "96") (pinfunction "PB9_96") (pintype "bidirectional"))
    )
    (net (code "249") (name "unconnected-(U1A-PB12-Pad51)") (class "Default")
      (node (ref "U1") (pin "51") (pinfunction "PB12_51") (pintype "bidirectional"))
    )
    (net (code "250") (name "unconnected-(U1A-PB13-Pad52)") (class "Default")
      (node (ref "U1") (pin "52") (pinfunction "PB13_52") (pintype "bidirectional"))
    )
    (net (code "251") (name "unconnected-(U1A-PB14-Pad53)") (class "Default")
      (node (ref "U1") (pin "53") (pinfunction "PB14_53") (pintype "bidirectional"))
    )
    (net (code "252") (name "unconnected-(U1A-PC1-Pad16)") (class "Default")
      (node (ref "U1") (pin "16") (pinfunction "PC1_16") (pintype "bidirectional"))
    )
    (net (code "253") (name "unconnected-(U1A-PC2-Pad17)") (class "Default")
      (node (ref "U1") (pin "17") (pinfunction "PC2_17") (pintype "bidirectional"))
    )
    (net (code "254") (name "unconnected-(U1A-PC3-Pad18)") (class "Default")
      (node (ref "U1") (pin "18") (pinfunction "PC3_18") (pintype "bidirectional"))
    )
    (net (code "255") (name "unconnected-(U1A-PC4-Pad33)") (class "Default")
      (node (ref "U1") (pin "33") (pinfunction "PC4_33") (pintype "bidirectional"))
    )
    (net (code "256") (name "unconnected-(U1A-PC5-Pad34)") (class "Default")
      (node (ref "U1") (pin "34") (pinfunction "PC5_34") (pintype "bidirectional"))
    )
    (net (code "257") (name "unconnected-(U1A-PC6-Pad63)") (class "Default")
      (node (ref "U1") (pin "63") (pinfunction "PC6_63") (pintype "bidirectional"))
    )
    (net (code "258") (name "unconnected-(U1A-PC7-Pad64)") (class "Default")
      (node (ref "U1") (pin "64") (pinfunction "PC7_64") (pintype "bidirectional"))
    )
    (net (code "259") (name "unconnected-(U1A-PC8-Pad65)") (class "Default")
      (node (ref "U1") (pin "65") (pinfunction "PC8_65") (pintype "bidirectional"))
    )
    (net (code "260") (name "unconnected-(U1A-PC13-Pad7)") (class "Default")
      (node (ref "U1") (pin "7") (pinfunction "PC13_7") (pintype "bidirectional"))
    )
    (net (code "261") (name "unconnected-(U1A-PC14-Pad8)") (class "Default")
      (node (ref "U1") (pin "8") (pinfunction "PC14_8") (pintype "bidirectional"))
    )
    (net (code "262") (name "unconnected-(U1A-PC15-Pad9)") (class "Default")
      (node (ref "U1") (pin "9") (pinfunction "PC15_9") (pintype "bidirectional"))
    )
    (net (code "263") (name "unconnected-(U1A-PD2-Pad83)") (class "Default")
      (node (ref "U1") (pin "83") (pinfunction "PD2_83") (pintype "bidirectional"))
    )
    (net (code "264") (name "unconnected-(U1A-PD3-Pad84)") (class "Default")
      (node (ref "U1") (pin "84") (pinfunction "PD3_84") (pintype "bidirectional"))
    )
    (net (code "265") (name "unconnected-(U1A-PD4-Pad85)") (class "Default")
      (node (ref "U1") (pin "85") (pinfunction "PD4_85") (pintype "bidirectional"))
    )
    (net (code "266") (name "unconnected-(U1A-PD6-Pad87)") (class "Default")
      (node (ref "U1") (pin "87") (pinfunction "PD6_87") (pintype "bidirectional"))
    )
    (net (code "267") (name "unconnected-(U1A-PD10-Pad57)") (class "Default")
      (node (ref "U1") (pin "57") (pinfunction "PD10_57") (pintype "bidirectional"))
    )
    (net (code "268") (name "unconnected-(U1A-PD11-Pad58)") (class "Default")
      (node (ref "U1") (pin "58") (pinfunction "PD11_58") (pintype "bidirectional"))
    )
    (net (code "269") (name "unconnected-(U1A-PE6-Pad5)") (class "Default")
      (node (ref "U1") (pin "5") (pinfunction "PE6_5") (pintype "bidirectional"))
    )
    (net (code "270") (name "unconnected-(U1A-PE7-Pad38)") (class "Default")
      (node (ref "U1") (pin "38") (pinfunction "PE7_38") (pintype "bidirectional"))
    )
    (net (code "271") (name "unconnected-(U1A-PE8-Pad39)") (class "Default")
      (node (ref "U1") (pin "39") (pinfunction "PE8_39") (pintype "bidirectional"))
    )
    (net (code "272") (name "unconnected-(U1A-PE9-Pad40)") (class "Default")
      (node (ref "U1") (pin "40") (pinfunction "PE9_40") (pintype "bidirectional"))
    )
    (net (code "273") (name "unconnected-(U1A-PE10-Pad41)") (class "Default")
      (node (ref "U1") (pin "41") (pinfunction "PE10_41") (pintype "bidirectional"))
    )
    (net (code "274") (name "unconnected-(U1A-PE11-Pad42)") (class "Default")
      (node (ref "U1") (pin "42") (pinfunction "PE11_42") (pintype "bidirectional"))
    )
    (net (code "275") (name "unconnected-(U1A-PE12-Pad43)") (class "Default")
      (node (ref "U1") (pin "43") (pinfunction "PE12_43") (pintype "bidirectional"))
    )
    (net (code "276") (name "unconnected-(U1A-PE13-Pad44)") (class "Default")
      (node (ref "U1") (pin "44") (pinfunction "PE13_44") (pintype "bidirectional"))
    )
    (net (code "277") (name "unconnected-(U1A-PE14-Pad45)") (class "Default")
      (node (ref "U1") (pin "45") (pinfunction "PE14_45") (pintype "bidirectional"))
    )
    (net (code "278") (name "unconnected-(U1A-PE15-Pad46)") (class "Default")
      (node (ref "U1") (pin "46") (pinfunction "PE15_46") (pintype "bidirectional"))
    )
    (net (code "279") (name "unconnected-(U3-DZ-PadA2)") (class "Default")
      (node (ref "U3") (pin "A2") (pinfunction "DZ_A2") (pintype "bidirectional"))
    )
    (net (code "280") (name "unconnected-(U3-PD1-PadB1)") (class "Default")
      (node (ref "U3") (pin "B1") (pinfunction "PD1_B1") (pintype "bidirectional"))
    )
    (net (code "281") (name "unconnected-(U3-PD2-PadC2)") (class "Default")
      (node (ref "U3") (pin "C2") (pinfunction "PD2_C2") (pintype "bidirectional"))
    )
    (net (code "282") (name "unconnected-(U3-PUP-PadB2)") (class "Default")
      (node (ref "U3") (pin "B2") (pinfunction "PUP_B2") (pintype "bidirectional"))
    )
    (net (code "283") (name "unconnected-(U10-BYPASS-Pad7)") (class "Default")
      (node (ref "U10") (pin "7") (pinfunction "BYPASS_7") (pintype "passive"))
    )
    (net (code "284") (name "unconnected-(U10-GAIN-Pad1)") (class "Default")
      (node (ref "U10") (pin "1") (pinfunction "GAIN_1") (pintype "passive"))
    )
    (net (code "285") (name "unconnected-(U10-GAIN-Pad8)") (class "Default")
      (node (ref "U10") (pin "8") (pinfunction "GAIN_8") (pintype "passive"))
    )
    (net (code "286") (name "unconnected-(U15-CLK--Pad5)") (class "Default")
      (node (ref "U15") (pin "5") (pinfunction "CLK-_5") (pintype "output"))
    )
    (net (code "287") (name "unconnected-(U15-NC-Pad1)") (class "Default")
      (node (ref "U15") (pin "1") (pinfunction "NC_1") (pintype "no_connect"))
    )
    (net (code "288") (name "unconnected-(U16-OSC_E-Pad7)") (class "Default")
      (node (ref "U16") (pin "7") (pinfunction "OSC_E_7") (pintype "bidirectional"))
    )
    (net (code "289") (name "unconnected-(U16-OUT_B-Pad5)") (class "Default")
      (node (ref "U16") (pin "5") (pinfunction "OUT_B_5") (pintype "bidirectional"))
    )
    (net (code "290") (name "~{BACK}") (class "Default")
      (node (ref "R27") (pin "1") (pinfunction "1_1") (pintype "passive"))
      (node (ref "SW4") (pin "1") (pinfunction "1_1") (pintype "bidirectional"))
      (node (ref "U1") (pin "82") (pinfunction "PD1_82") (pintype "bidirectional"))
    )
    (net (code "291") (name "~{BOOT0}") (class "Default")
      (node (ref "R19") (pin "1") (pinfunction "1_1") (pintype "passive"))
      (node (ref "U1") (pin "88") (pinfunction "PD7_88") (pintype "bidirectional"))
      (node (ref "U1") (pin "94") (pinfunction "BOOT0_94") (pintype "bidirectional"))
    )
    (net (code "292") (name "~{EXT-PTT}") (class "Default")
      (node (ref "R23") (pin "2") (pinfunction "2_2") (pintype "passive"))
      (node (ref "U1") (pin "55") (pinfunction "PD8_55") (pintype "bidirectional"))
    )
    (net (code "293") (name "~{SELECT}") (class "Default")
      (node (ref "R22") (pin "1") (pinfunction "1_1") (pintype "passive"))
      (node (ref "SW3") (pin "1") (pinfunction "1_1") (pintype "bidirectional"))
      (node (ref "U1") (pin "81") (pinfunction "PD0_81") (pintype "bidirectional"))
    )
    (net (code "294") (name "~{TEST}") (class "Default")
      (node (ref "J1") (pin "1") (pinfunction "1_1") (pintype "bidirectional"))
      (node (ref "R7") (pin "2") (pinfunction "2_2") (pintype "passive"))
      (node (ref "U1") (pin "56") (pinfunction "PD9_56") (pintype "bidirectional"))
    )
  )
)
